# jr-support_v4.net
KiCad netlist of a schematic drawn in EAGLE
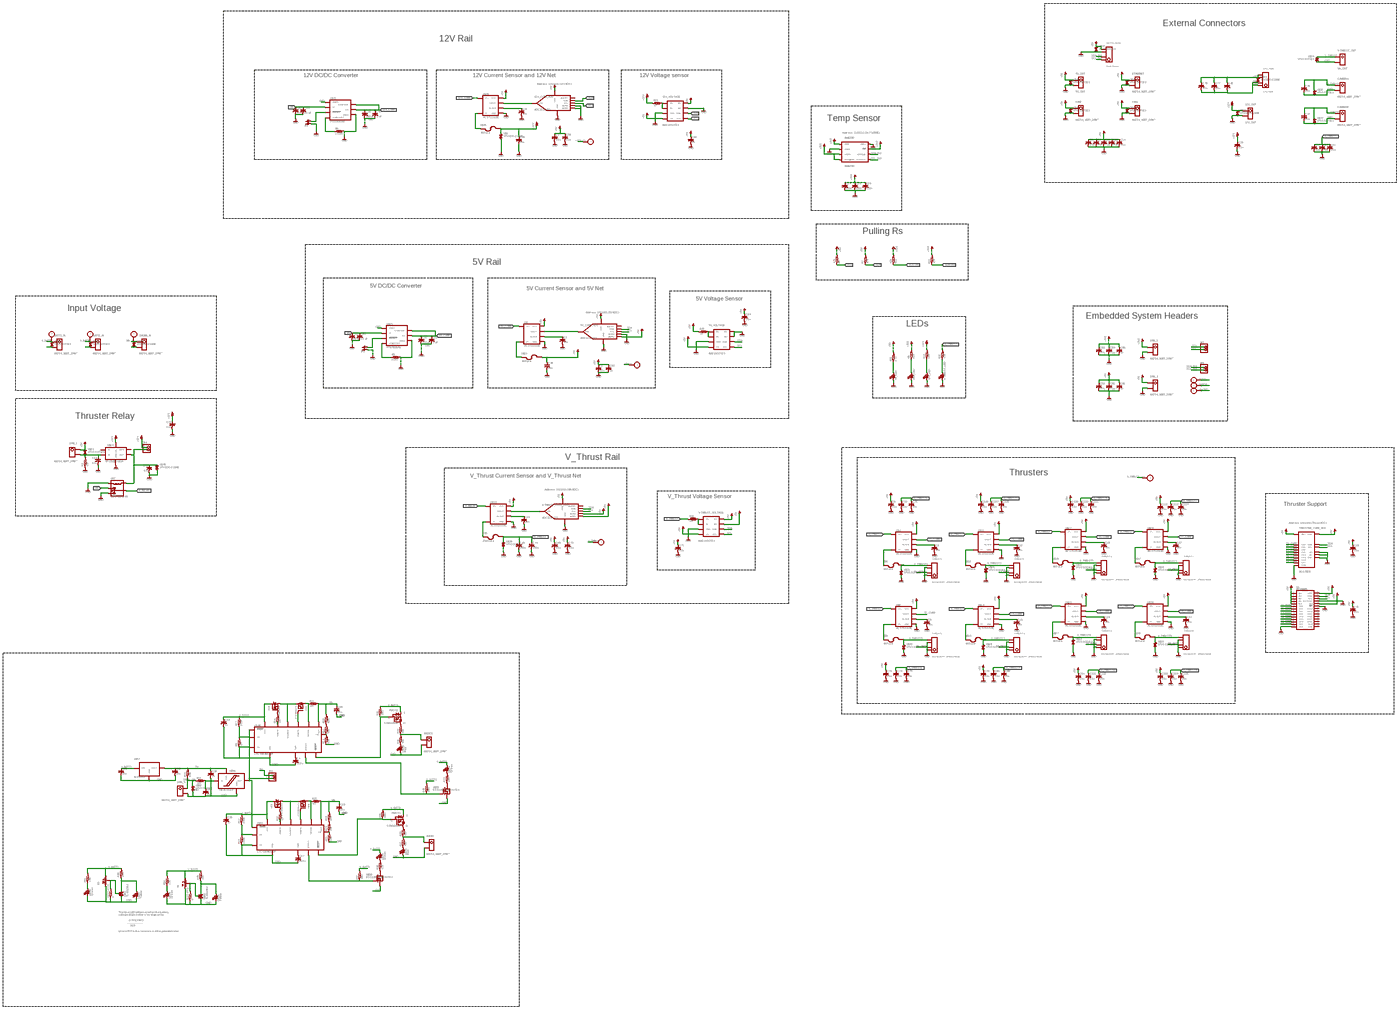
[diagram p0: schematic, sheet 1, overview]
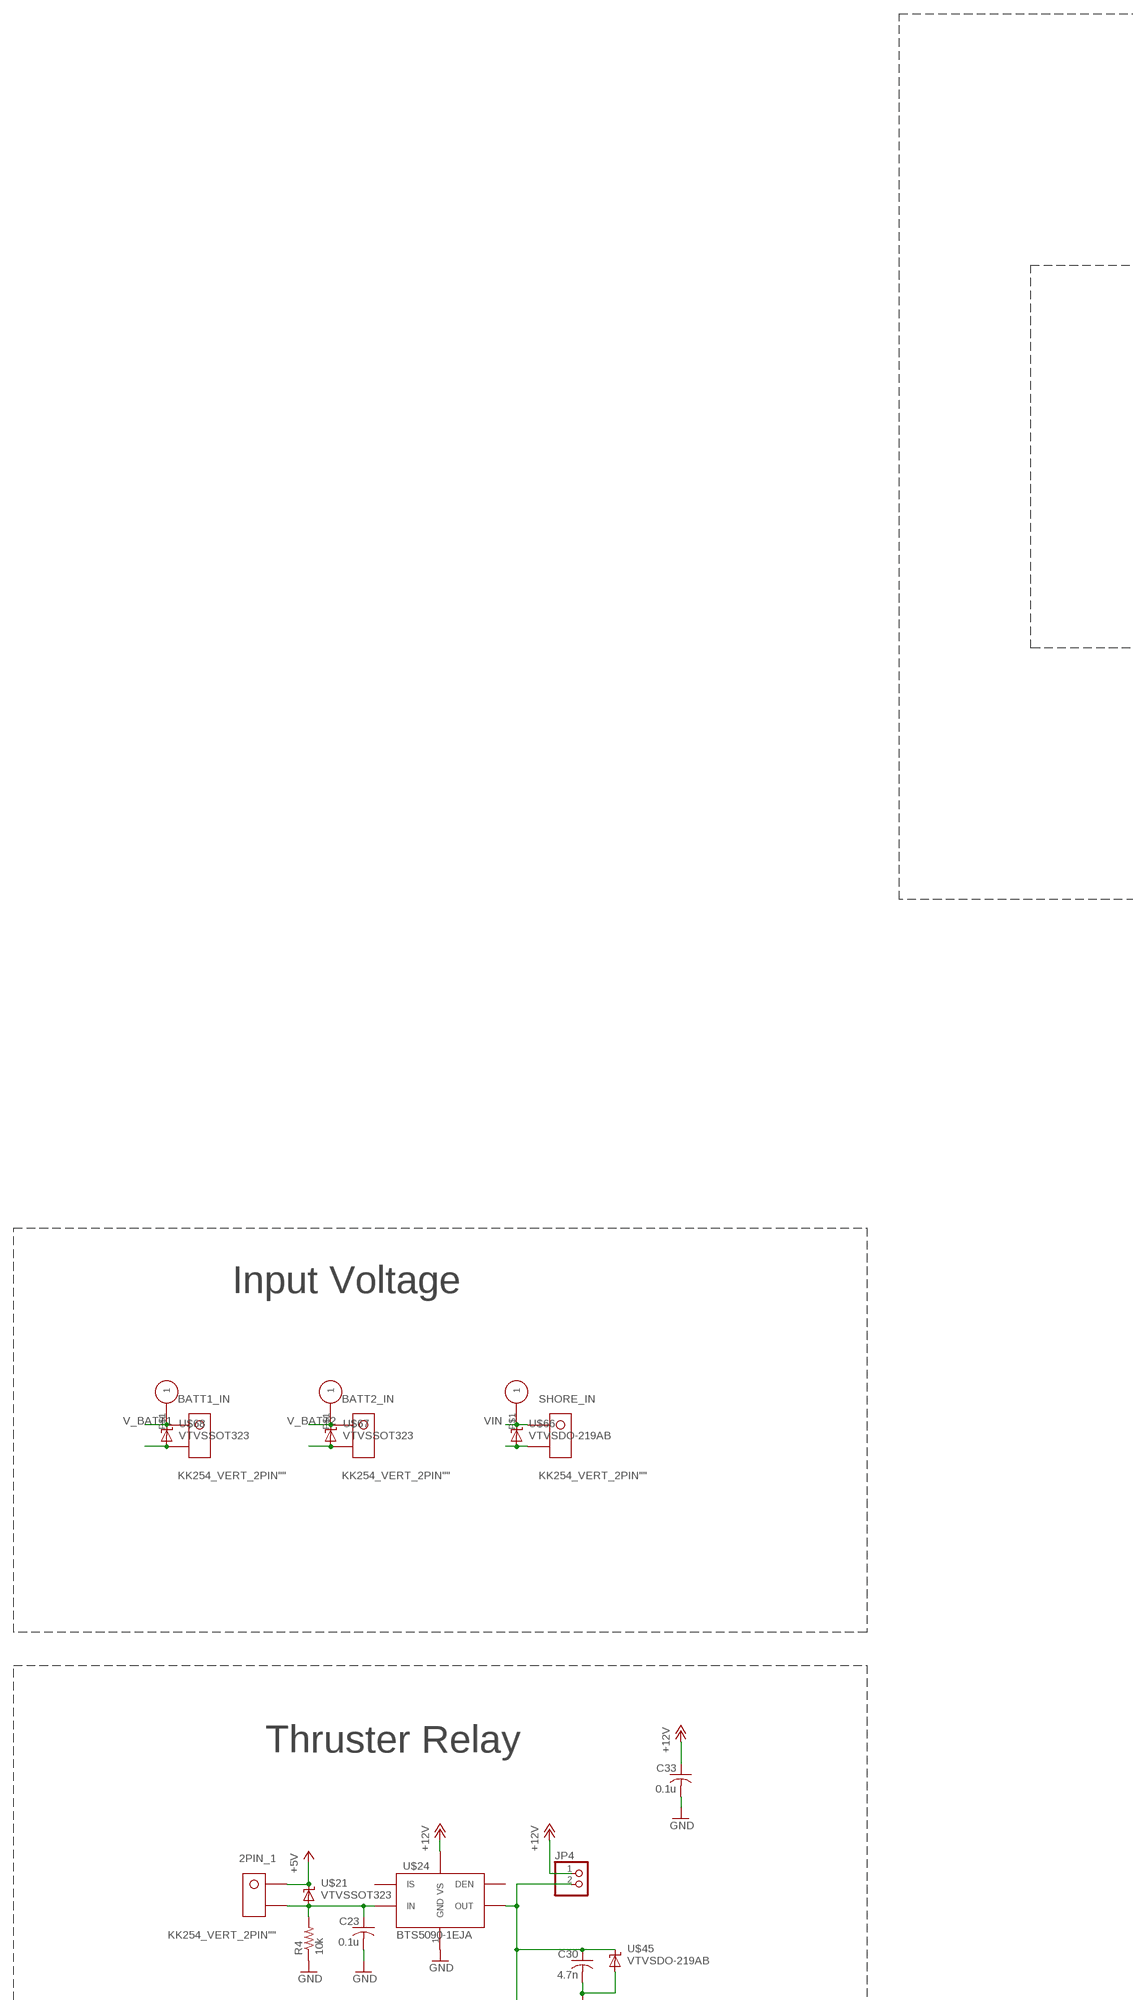
[diagram p1: schematic, sheet 1, part 1 of 8]
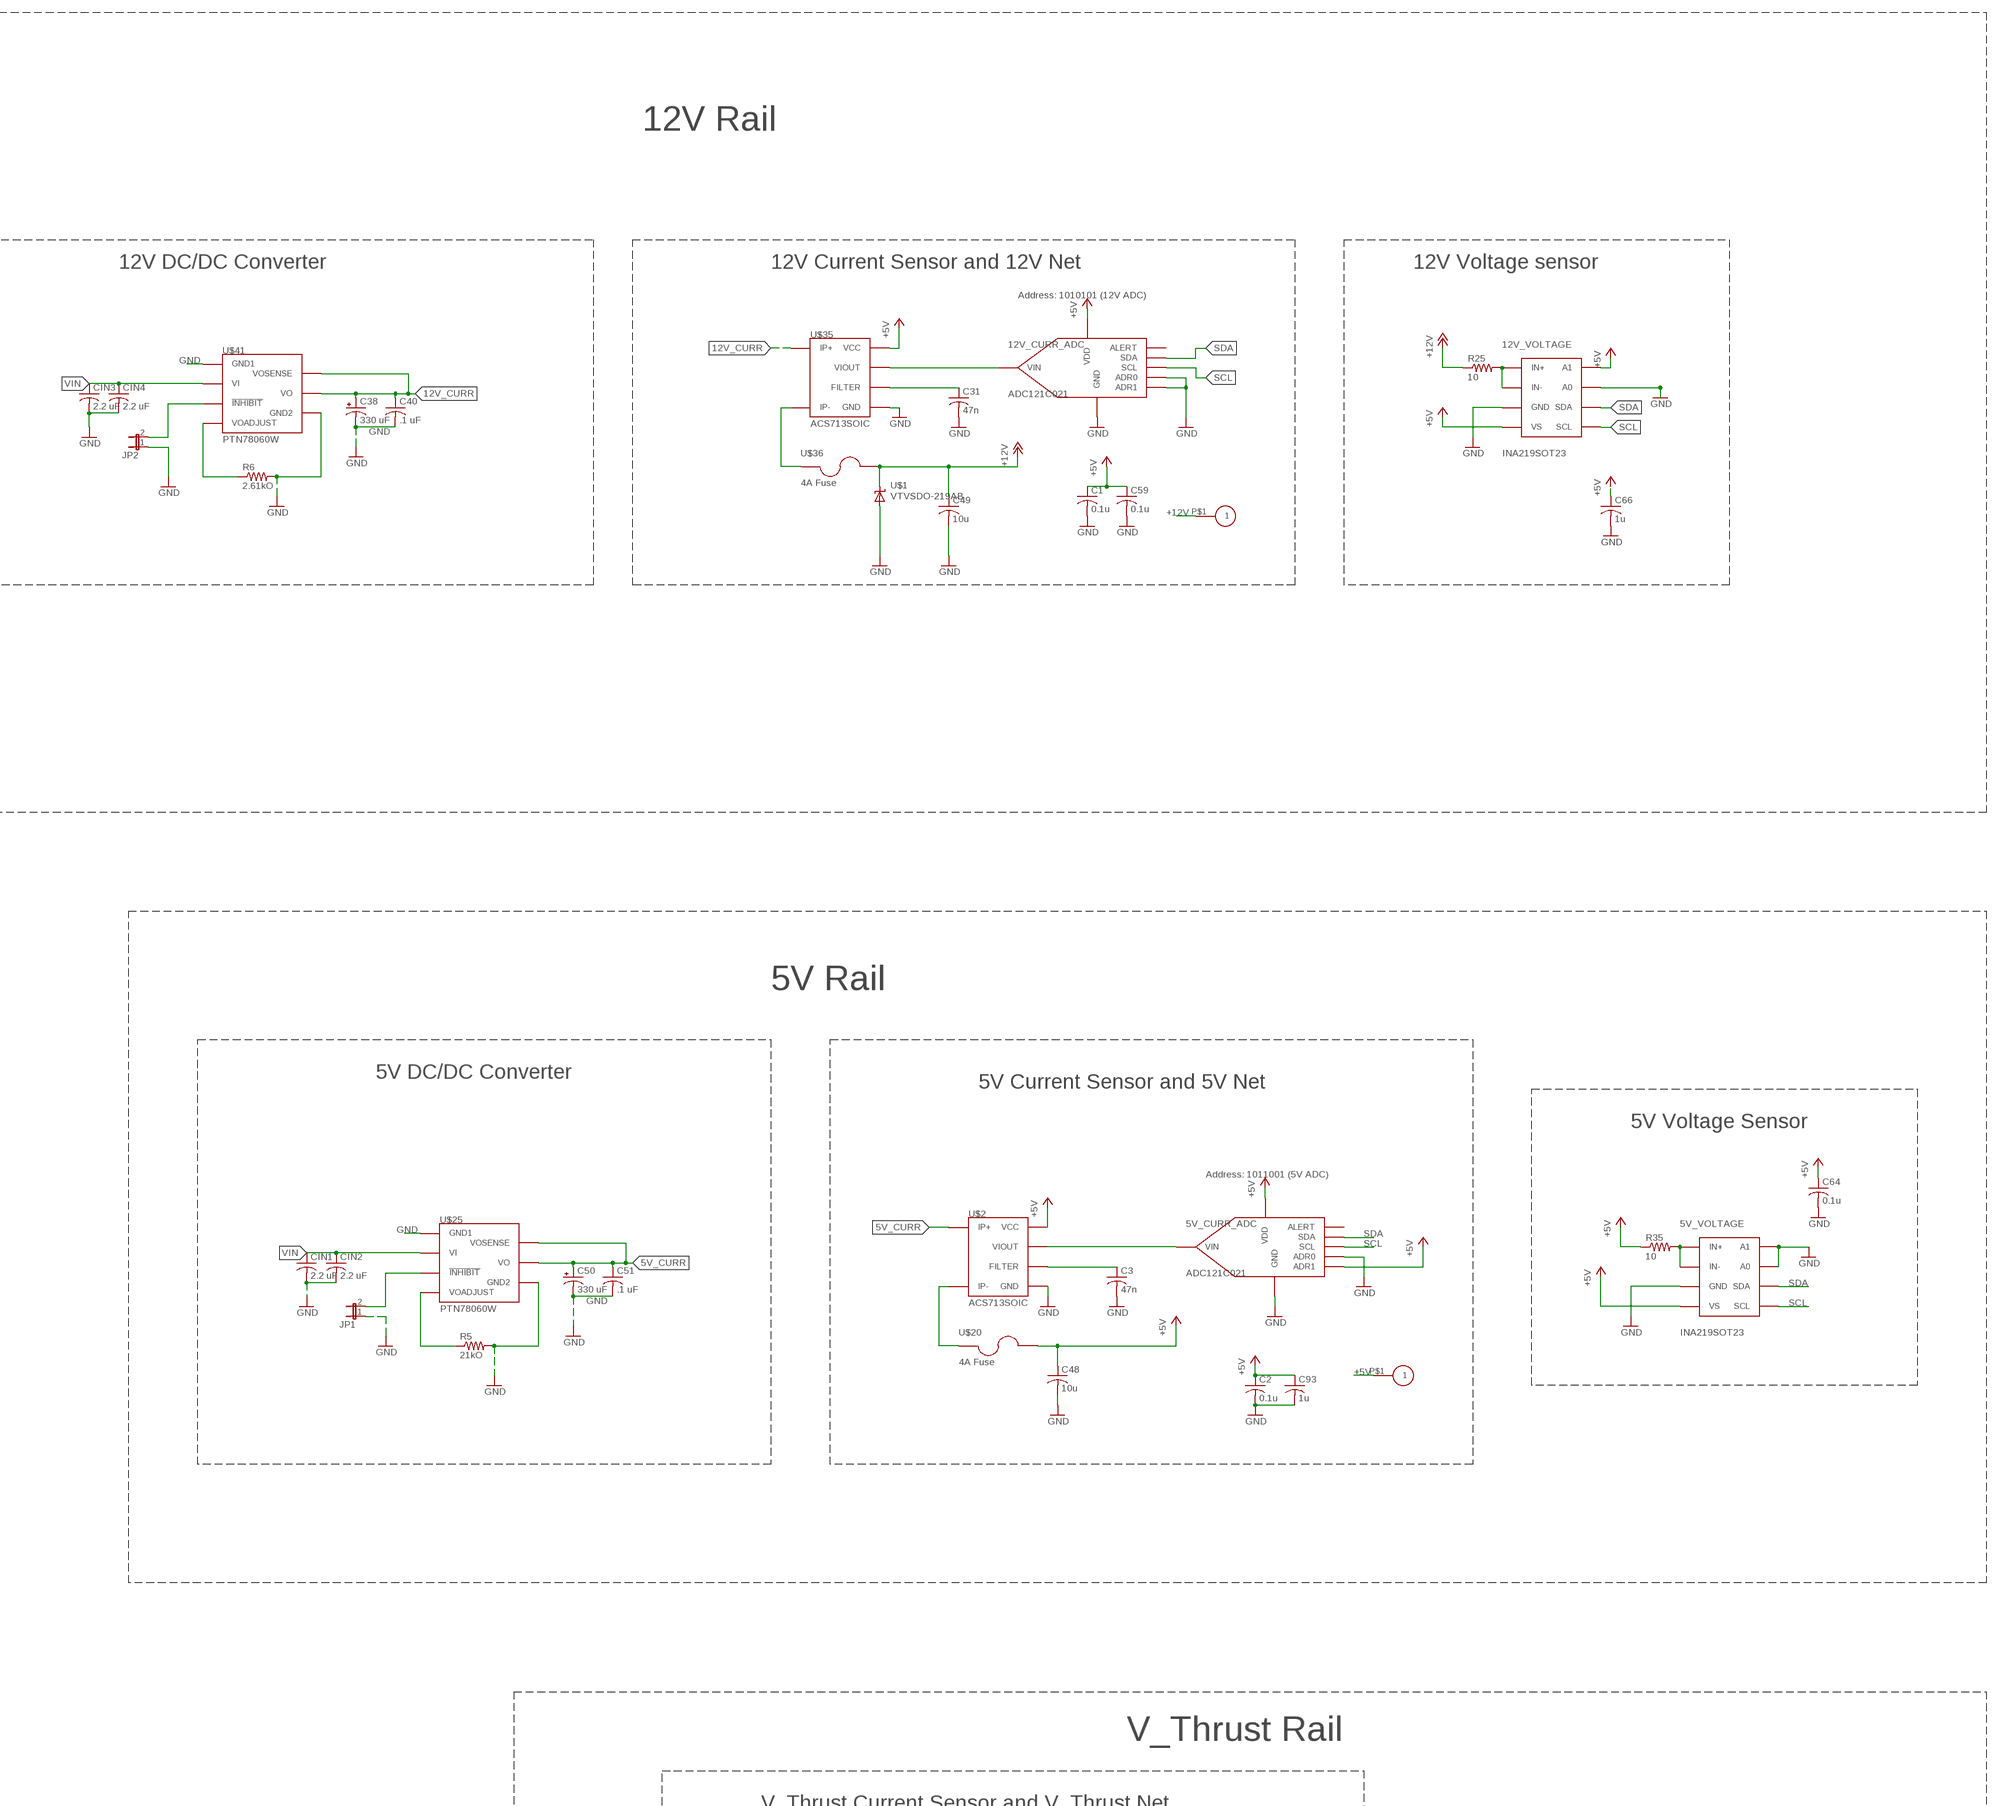
[diagram p2: schematic, sheet 1, part 2 of 8]
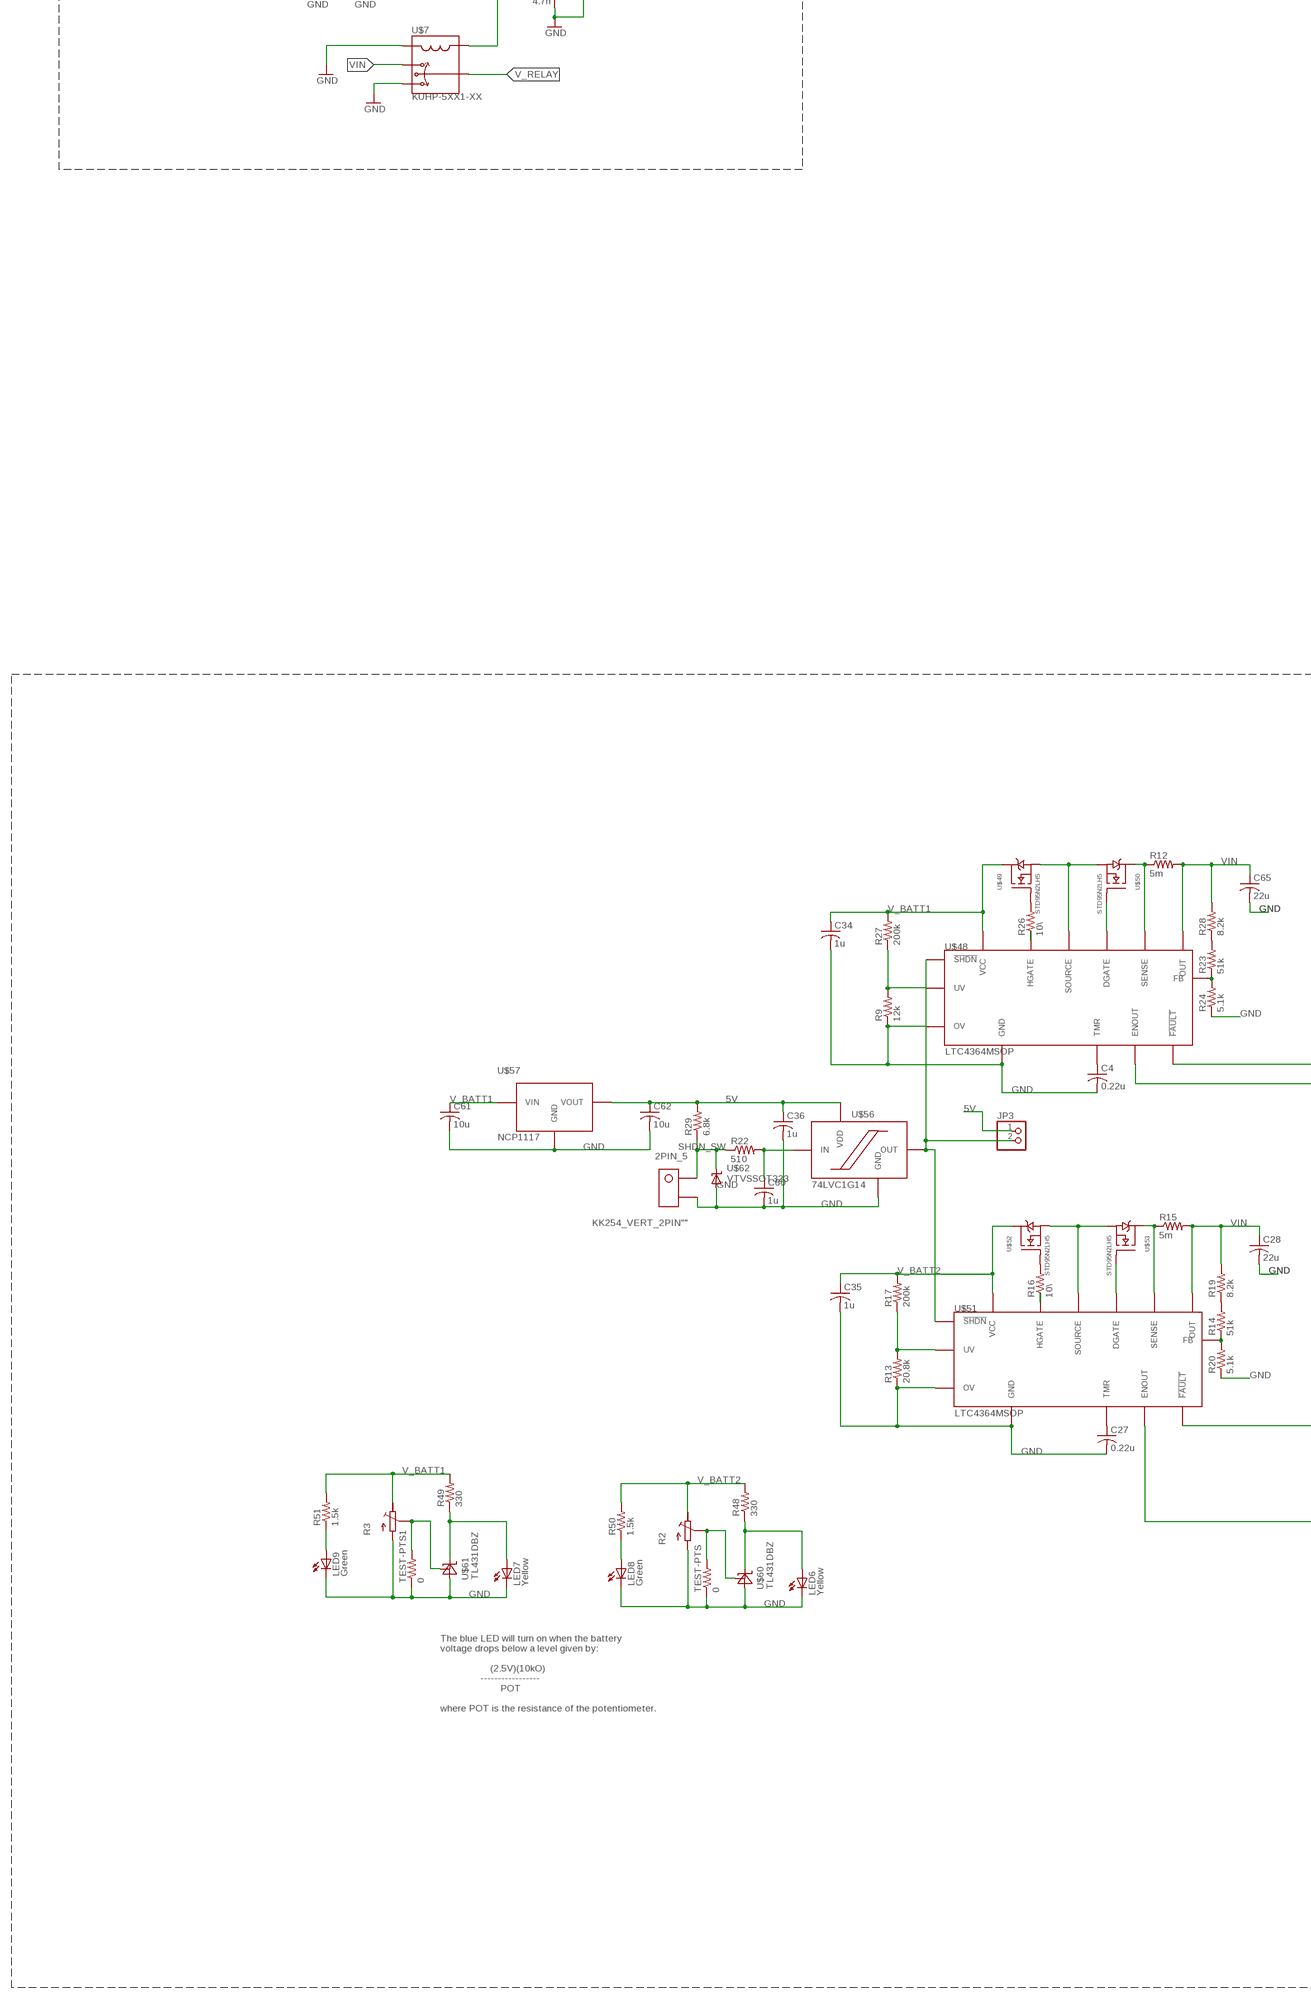
[diagram p3: schematic, sheet 1, part 3 of 8]
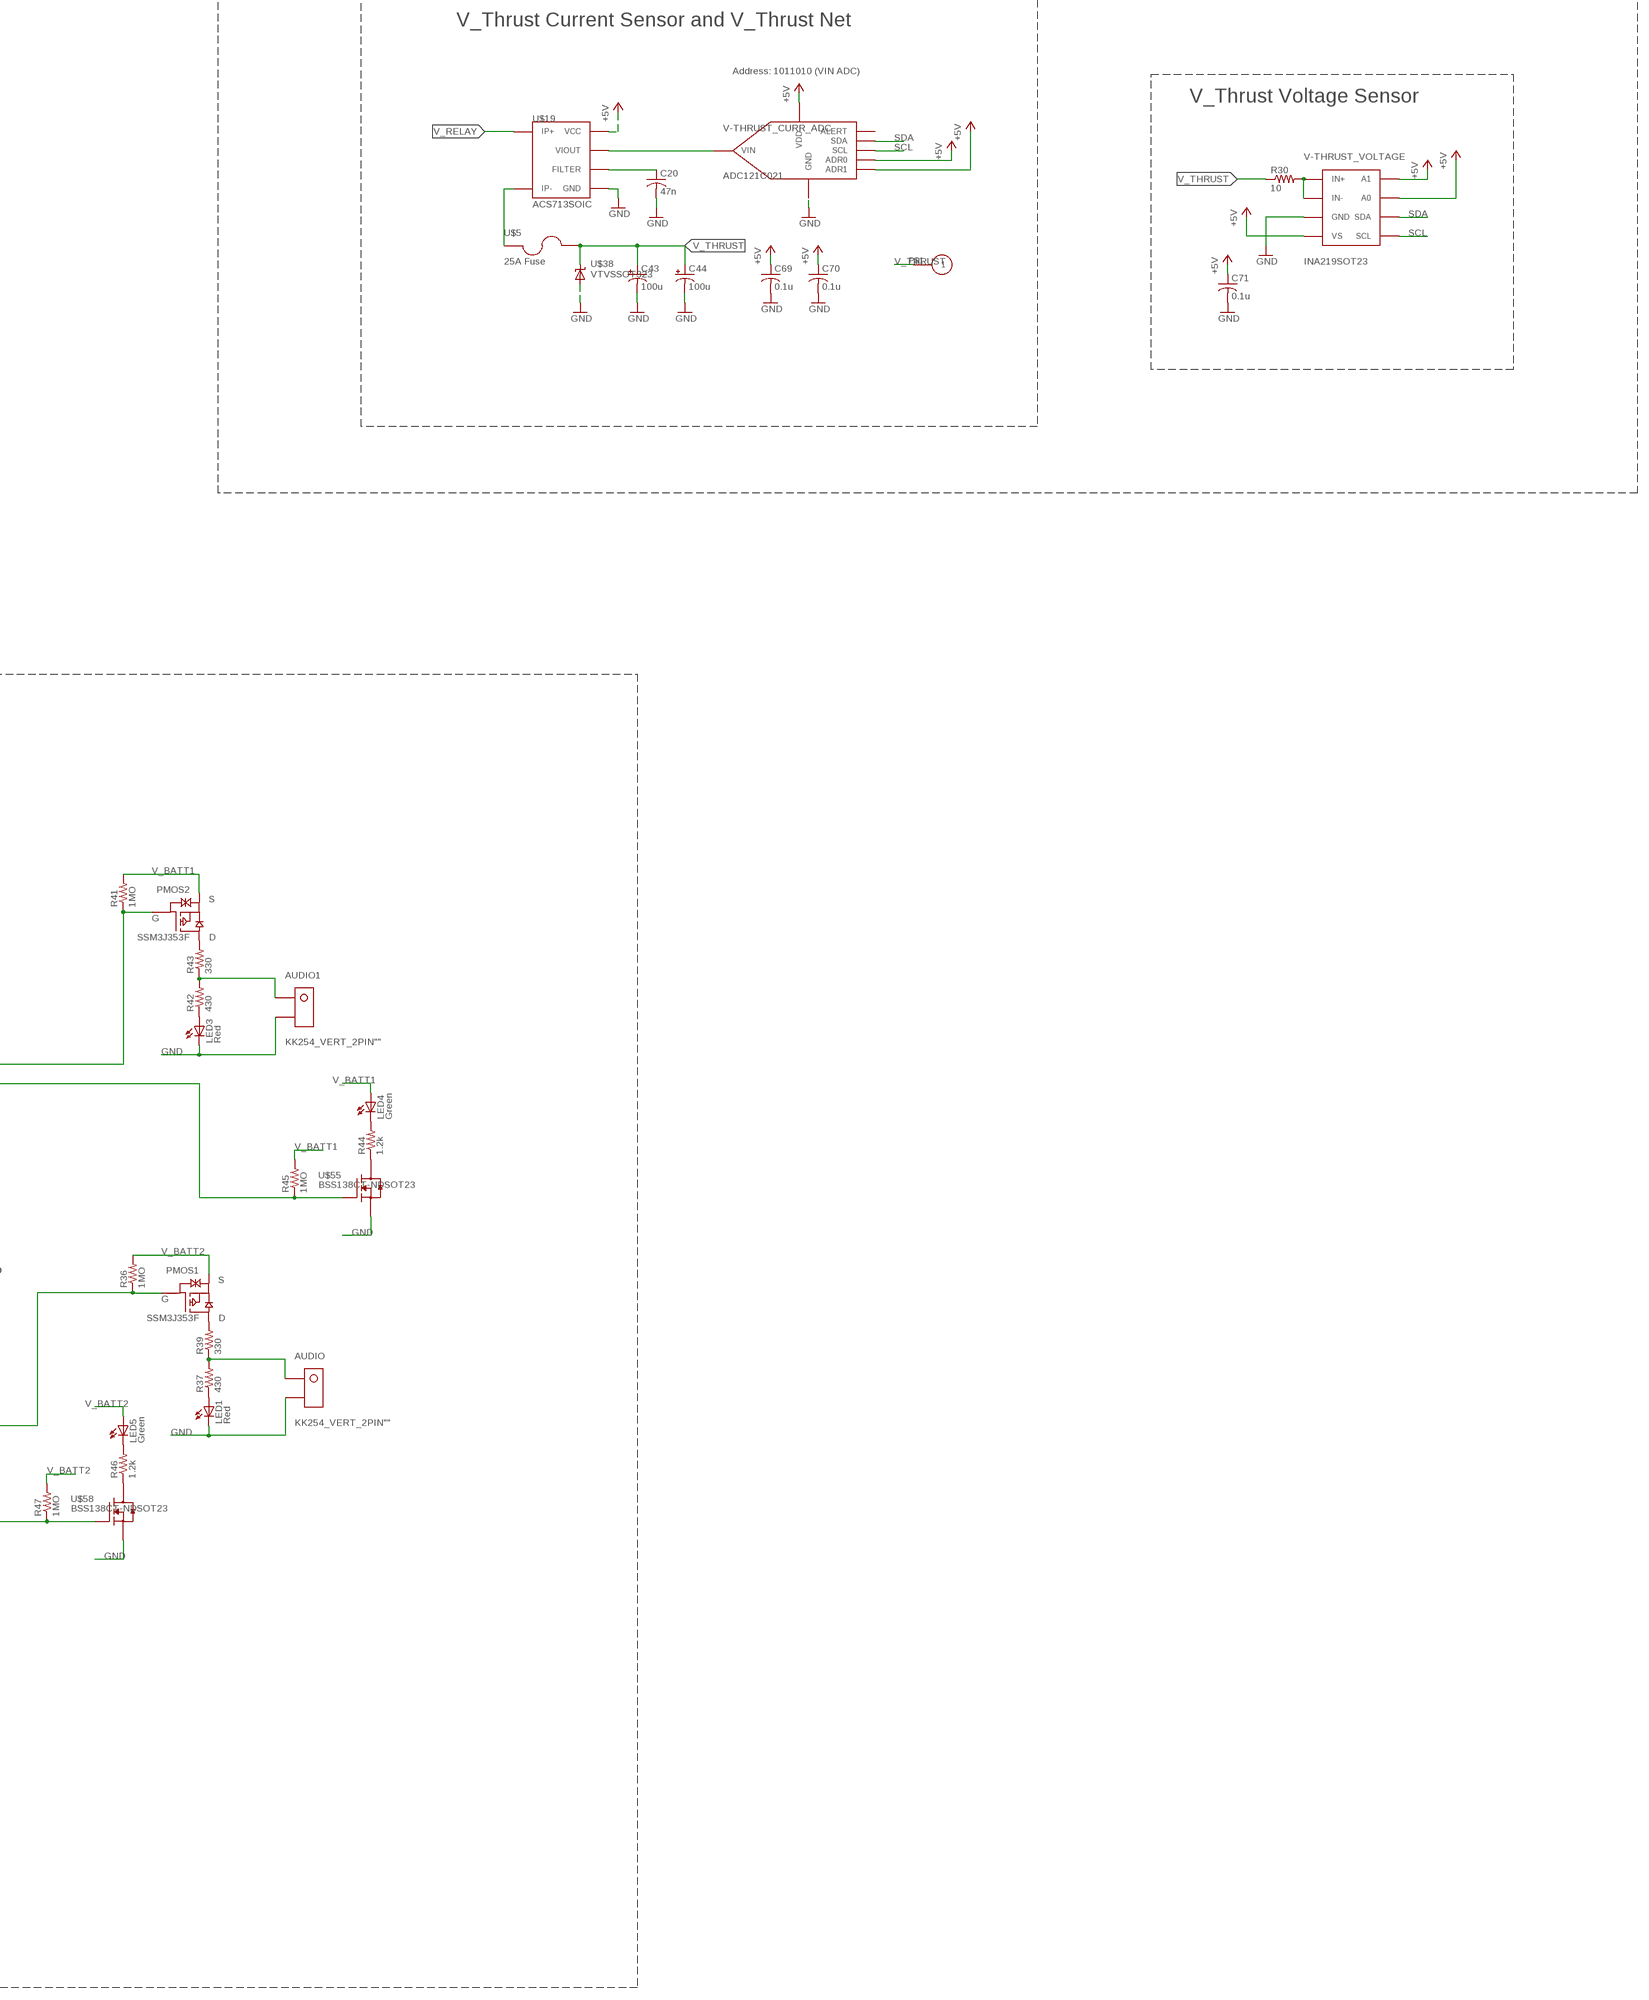
[diagram p4: schematic, sheet 1, part 4 of 8]
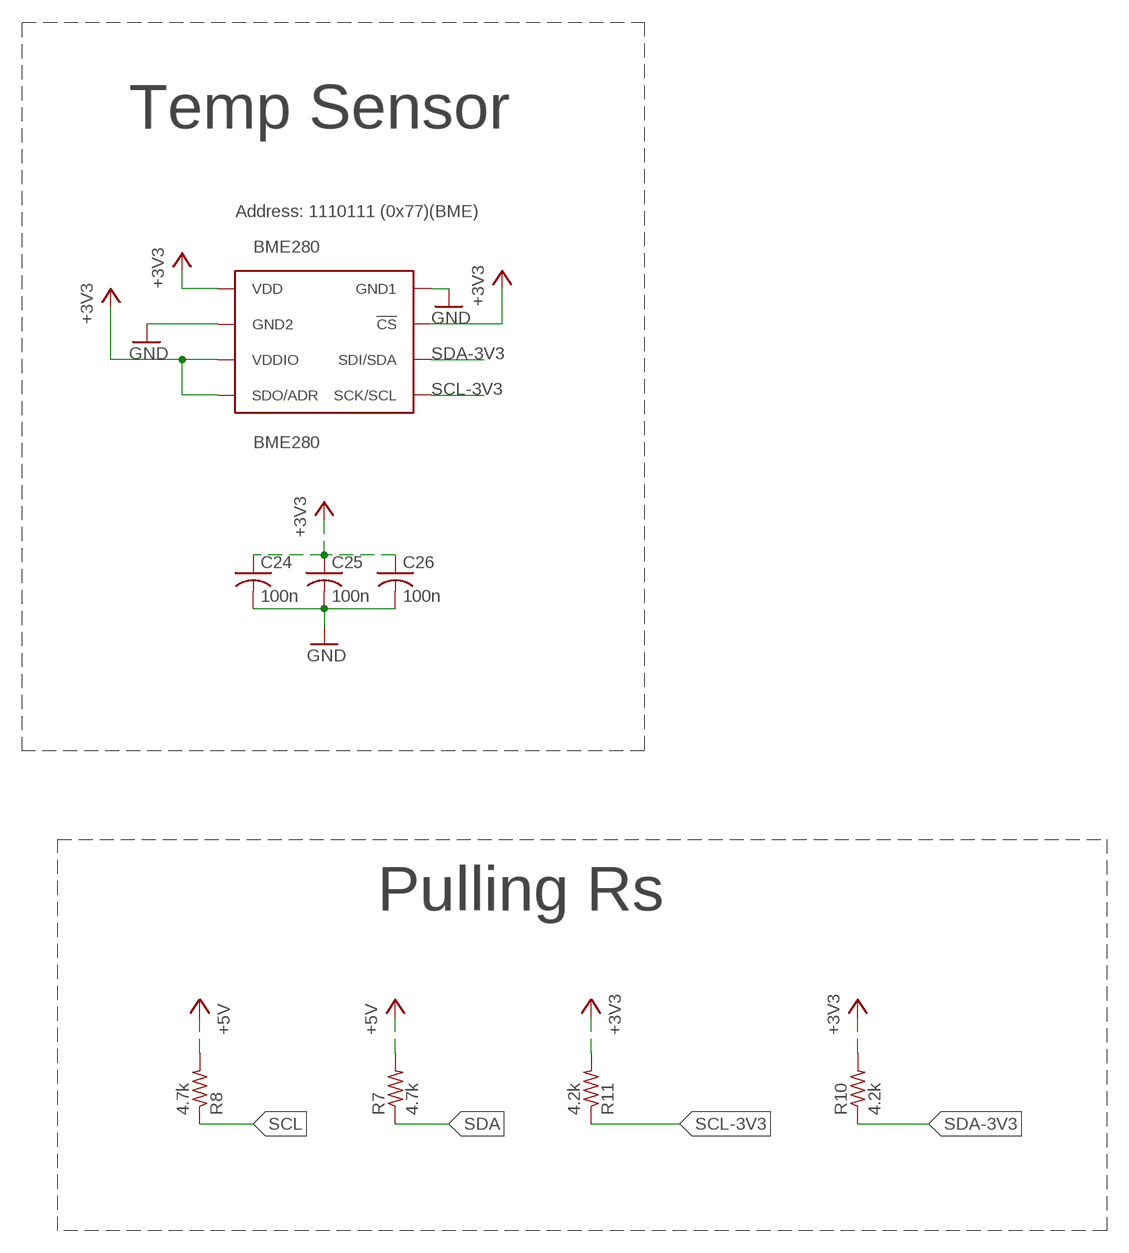
[diagram p5: schematic, sheet 1, part 5 of 8]
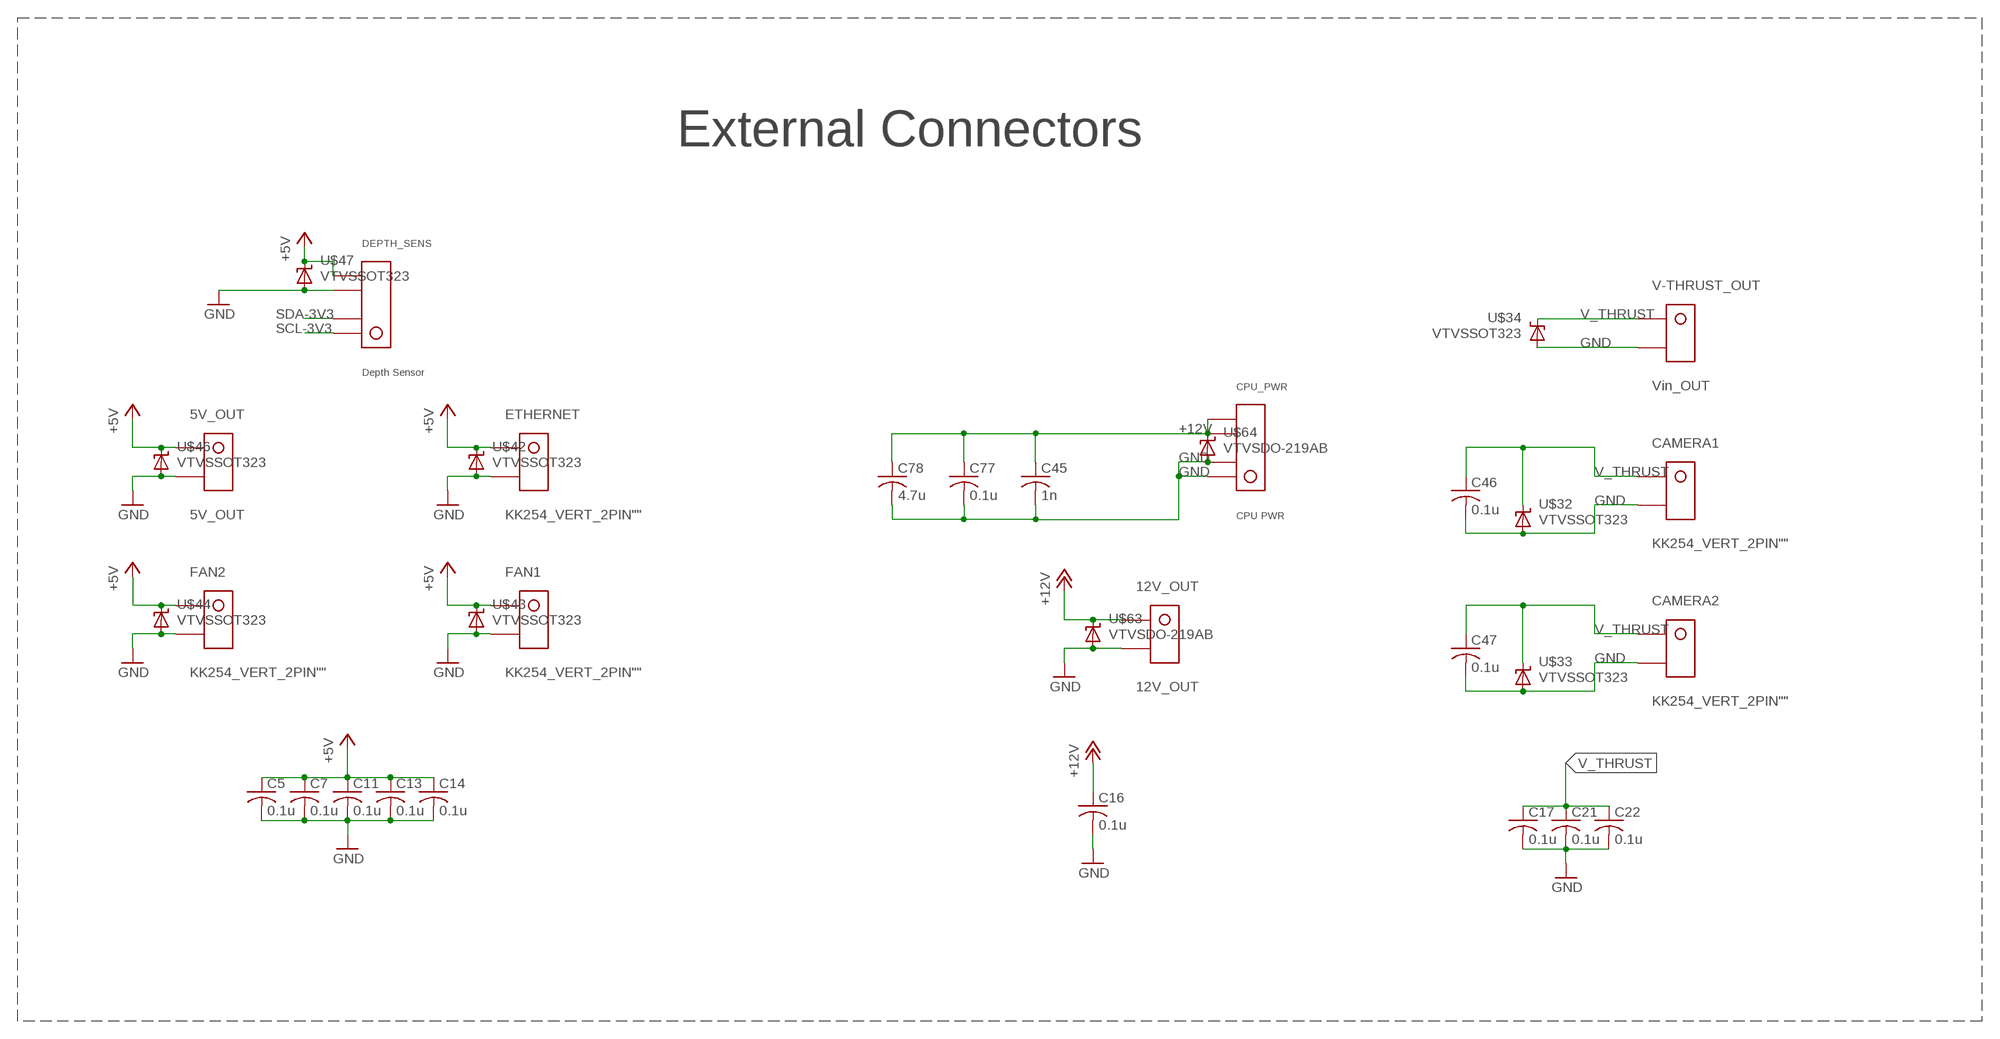
[diagram p6: schematic, sheet 1, part 6 of 8]
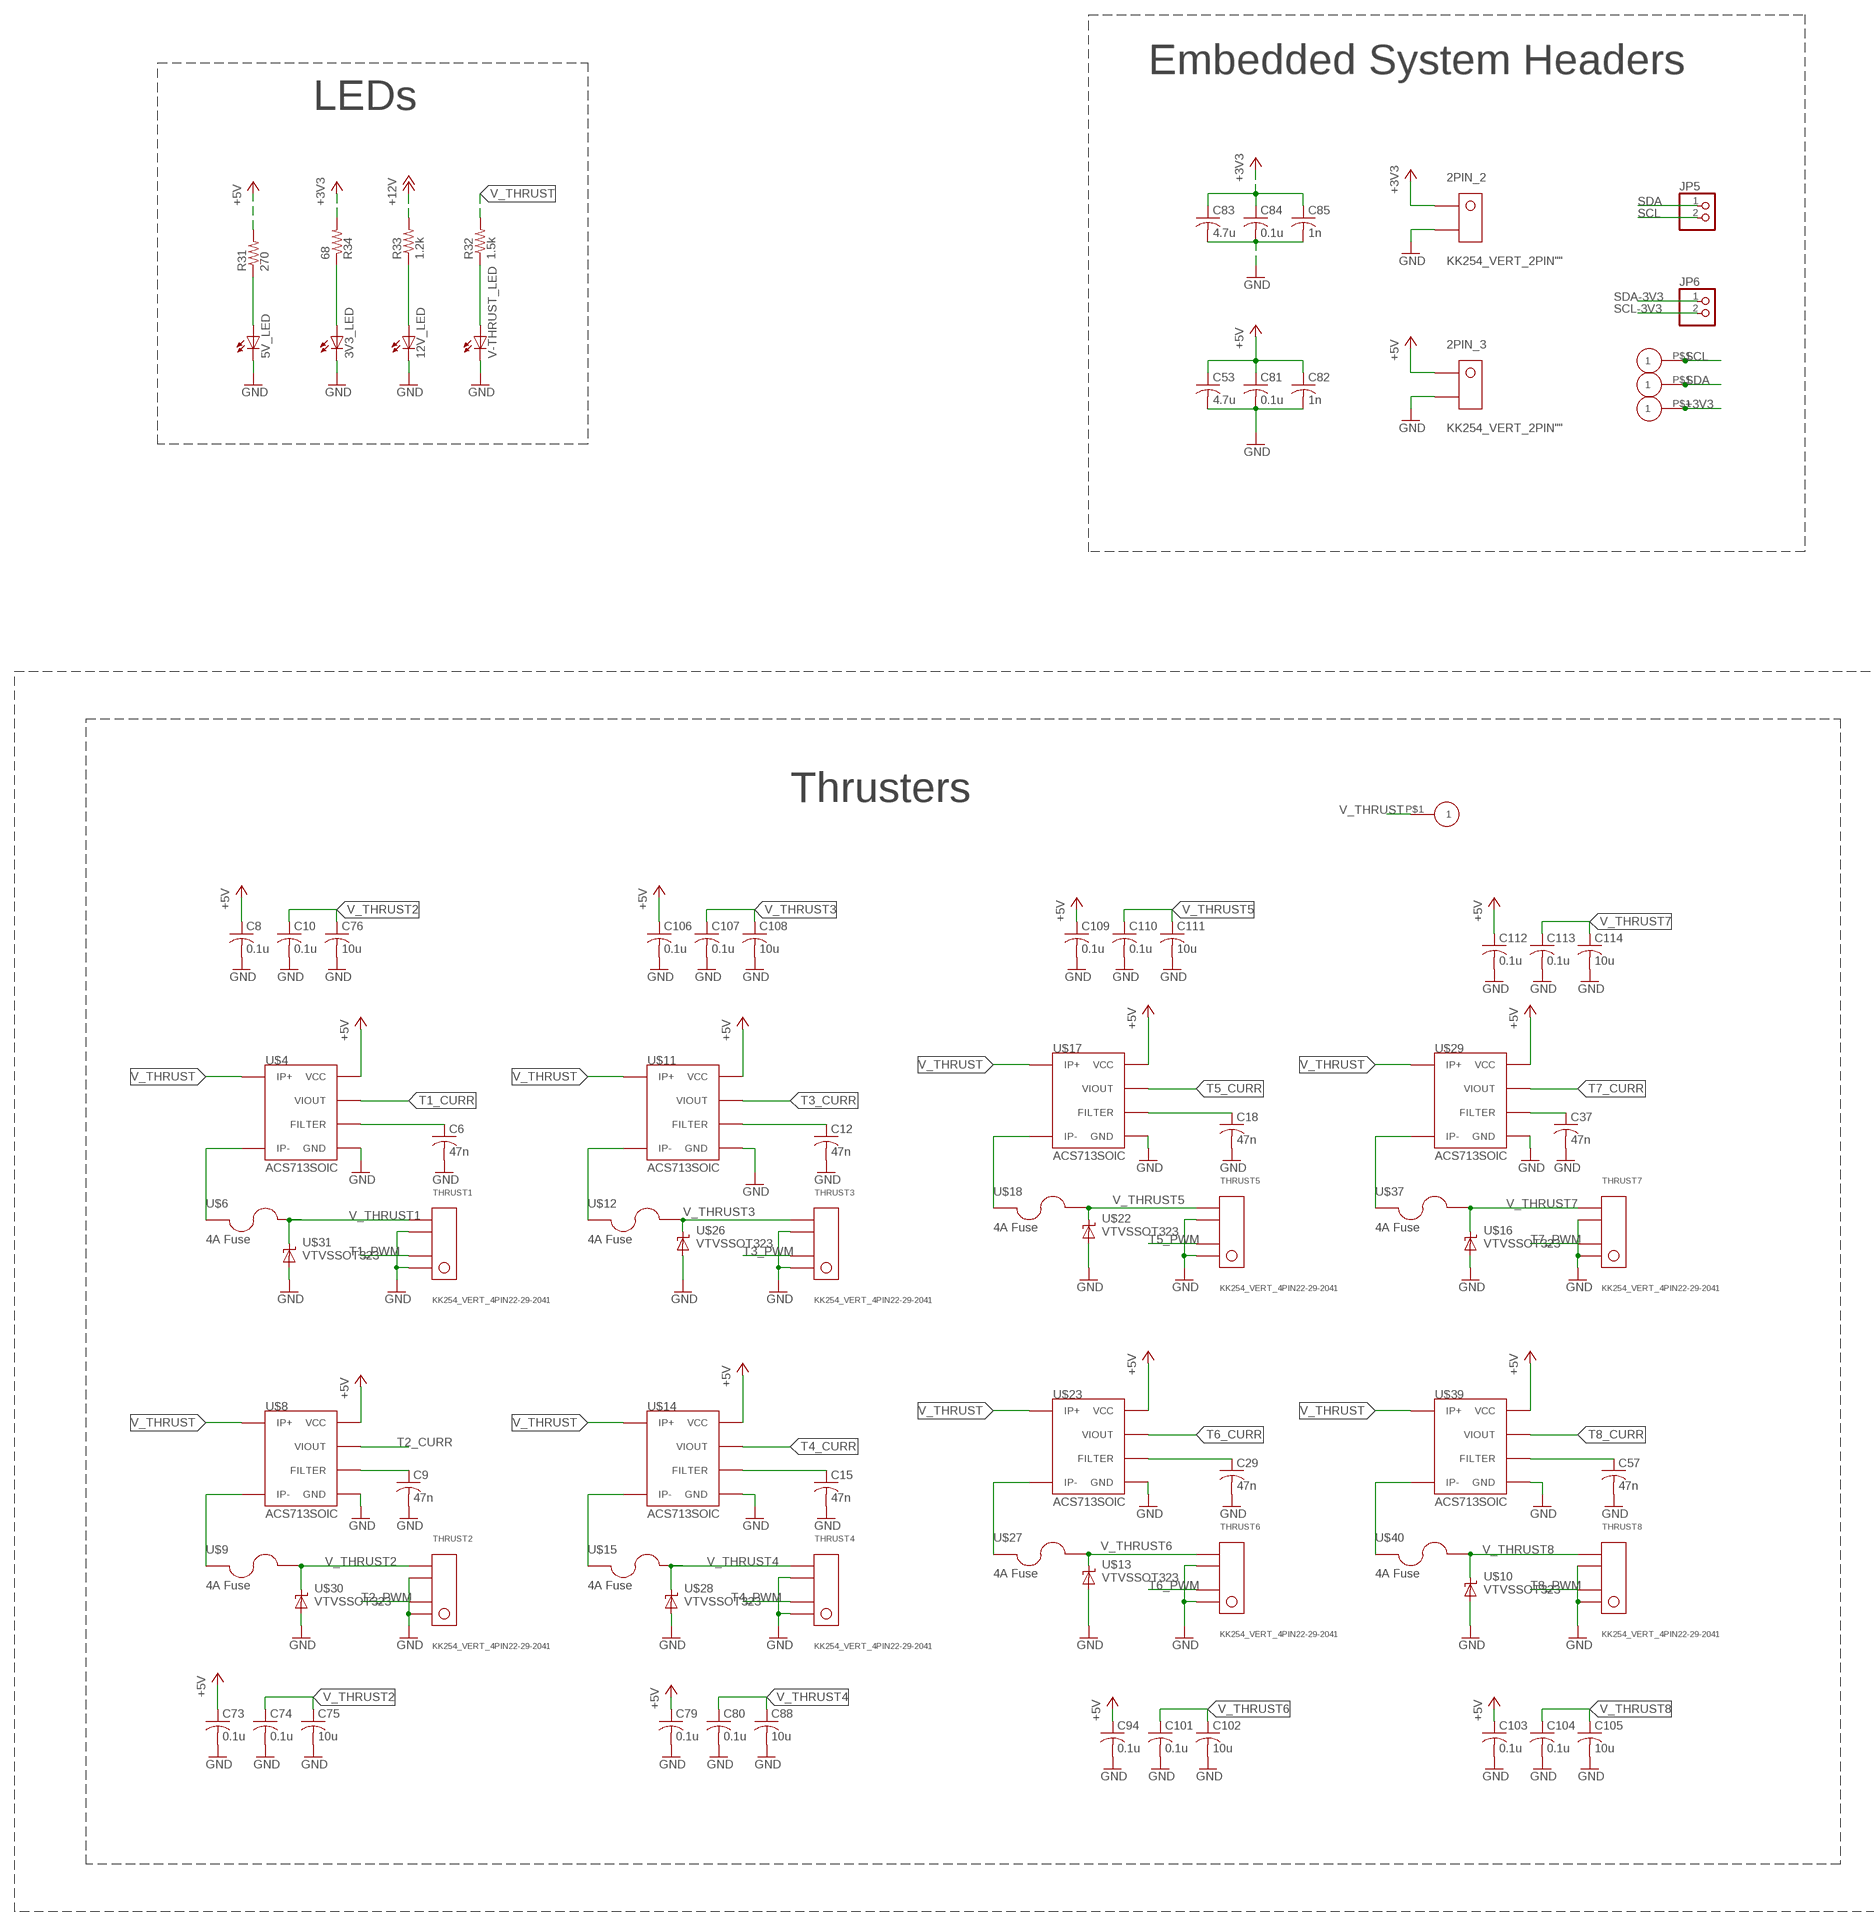
[diagram p7: schematic, sheet 1, part 7 of 8]
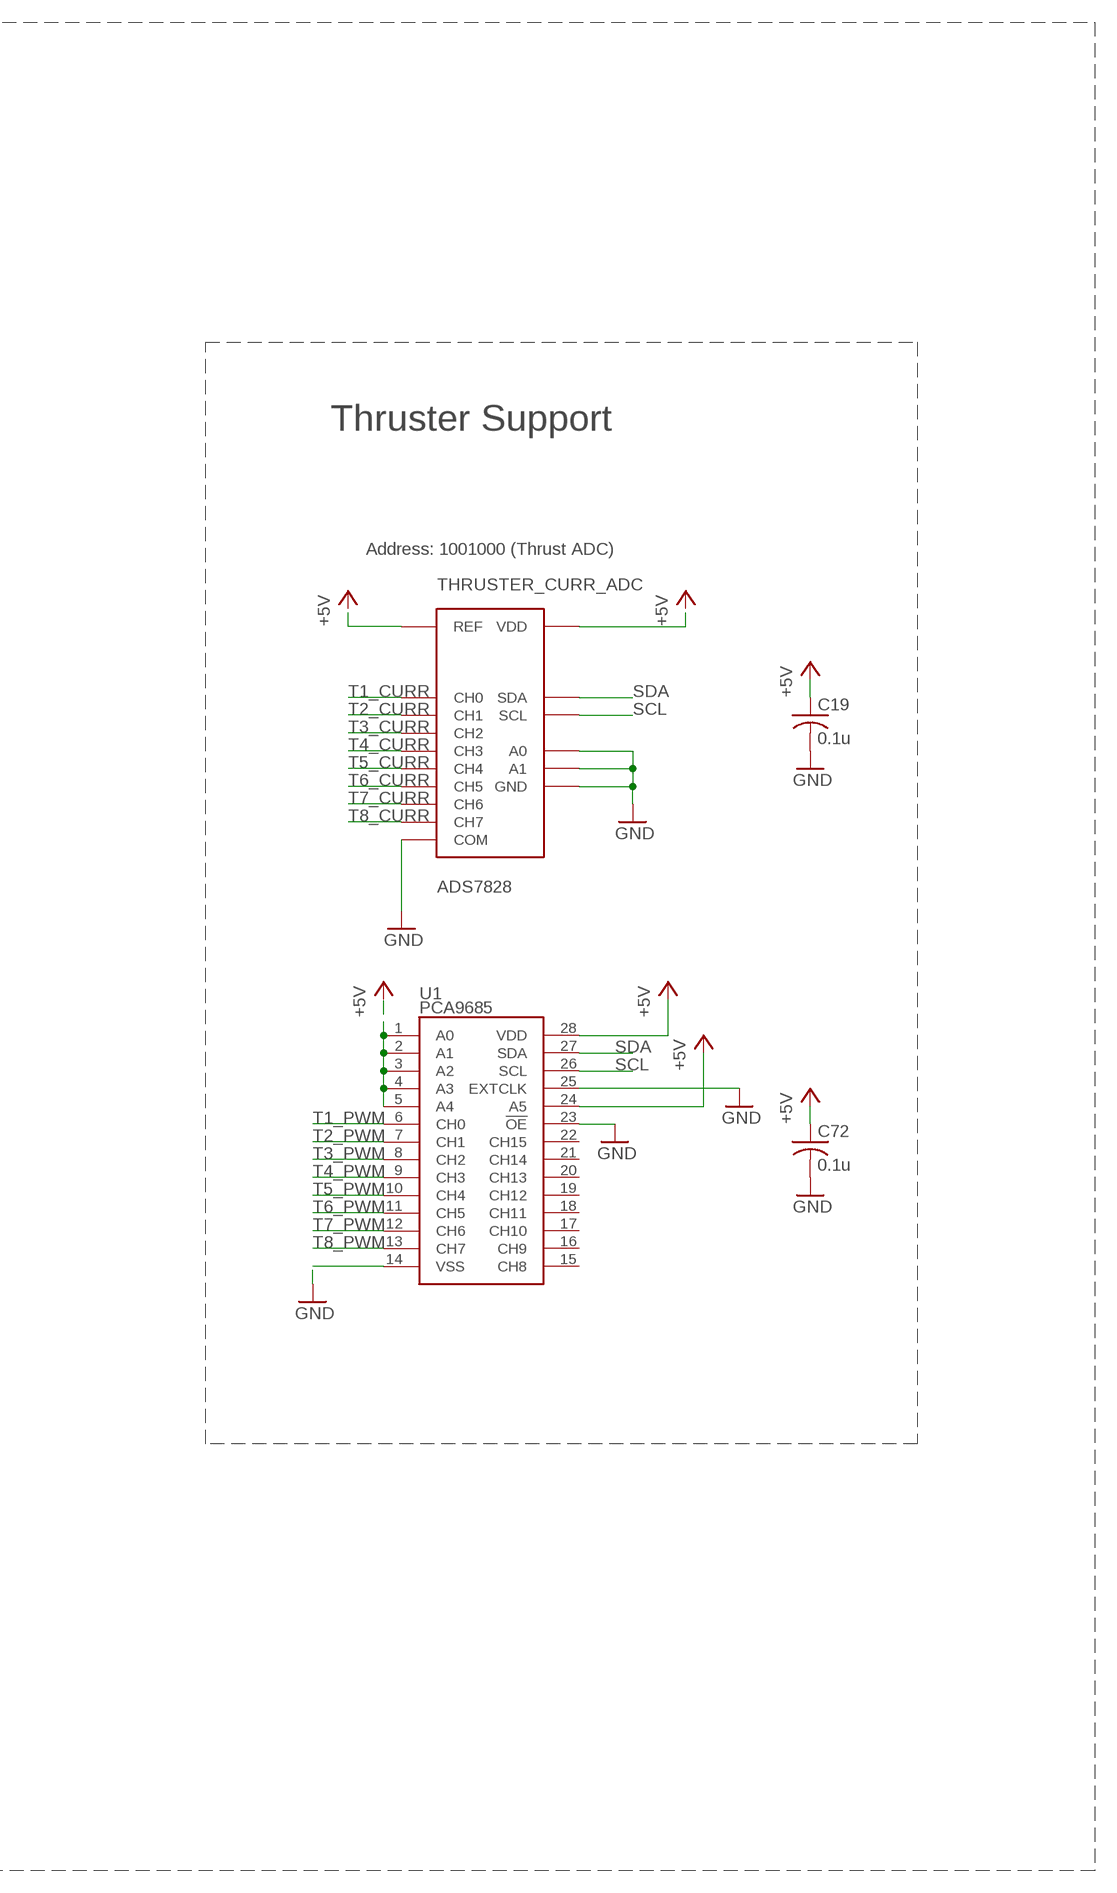
[diagram p8: schematic, sheet 1, part 8 of 8]

(export (version "E")
  (design (tool "Eeschema 10.0.6"))
  (components
    (comp (ref "2PIN_1")
      (value "KK254_VERT_2PIN\"\"")
      (footprint "eagle-import:KK254_VERT_2PIN")
      (libsource (lib "eagle-import") (part "KK254_VERT_2PIN{dblquote}{dblquote}"))
    )
    (comp (ref "2PIN_2")
      (value "KK254_VERT_2PIN\"\"")
      (footprint "eagle-import:KK254_VERT_2PIN")
      (libsource (lib "eagle-import") (part "KK254_VERT_2PIN{dblquote}{dblquote}"))
    )
    (comp (ref "2PIN_3")
      (value "KK254_VERT_2PIN\"\"")
      (footprint "eagle-import:KK254_VERT_2PIN")
      (libsource (lib "eagle-import") (part "KK254_VERT_2PIN{dblquote}{dblquote}"))
    )
    (comp (ref "2PIN_5")
      (value "KK254_VERT_2PIN\"\"")
      (footprint "eagle-import:KK254_VERT_2PIN")
      (libsource (lib "eagle-import") (part "KK254_VERT_2PIN{dblquote}{dblquote}"))
    )
    (comp (ref "3V3_LED")
      (value "0805_LED")
      (footprint "eagle-import:0805")
      (libsource (lib "eagle-import") (part "0805_LED"))
    )
    (comp (ref "5V_CURR_ADC")
      (value "ADC121C021")
      (footprint "eagle-import:VSSOP-8")
      (libsource (lib "eagle-import") (part "ADC121C021"))
    )
    (comp (ref "5V_LED")
      (value "0805_LED")
      (footprint "eagle-import:0805")
      (libsource (lib "eagle-import") (part "0805_LED"))
    )
    (comp (ref "5V_OUT")
      (value "5V_OUT")
      (footprint "eagle-import:KK254_VERT_2PIN")
      (libsource (lib "eagle-import") (part "KK254_VERT_2PIN{dblquote}{dblquote}"))
    )
    (comp (ref "5V_VOLTAGE")
      (value "INA219SOT23")
      (footprint "eagle-import:SOT-23-8")
      (libsource (lib "eagle-import") (part "INA219SOT23"))
    )
    (comp (ref "12V_CURR_ADC")
      (value "ADC121C021")
      (footprint "eagle-import:VSSOP-8")
      (libsource (lib "eagle-import") (part "ADC121C021"))
    )
    (comp (ref "12V_LED")
      (value "0805_LED")
      (footprint "eagle-import:0805")
      (libsource (lib "eagle-import") (part "0805_LED"))
    )
    (comp (ref "12V_OUT")
      (value "12V_OUT")
      (footprint "eagle-import:KK254_VERT_2PIN")
      (libsource (lib "eagle-import") (part "KK254_VERT_2PIN{dblquote}{dblquote}"))
    )
    (comp (ref "12V_VOLTAGE")
      (value "INA219SOT23")
      (footprint "eagle-import:SOT-23-8")
      (libsource (lib "eagle-import") (part "INA219SOT23"))
    )
    (comp (ref "AUDIO")
      (value "KK254_VERT_2PIN\"\"")
      (footprint "eagle-import:KK254_VERT_2PIN")
      (libsource (lib "eagle-import") (part "KK254_VERT_2PIN{dblquote}{dblquote}"))
    )
    (comp (ref "AUDIO1")
      (value "KK254_VERT_2PIN\"\"")
      (footprint "eagle-import:KK254_VERT_2PIN")
      (libsource (lib "eagle-import") (part "KK254_VERT_2PIN{dblquote}{dblquote}"))
    )
    (comp (ref "BATT1_IN")
      (value "KK254_VERT_2PIN\"\"")
      (footprint "eagle-import:KK254_VERT_2PIN")
      (libsource (lib "eagle-import") (part "KK254_VERT_2PIN{dblquote}{dblquote}"))
    )
    (comp (ref "BATT2_IN")
      (value "KK254_VERT_2PIN\"\"")
      (footprint "eagle-import:KK254_VERT_2PIN")
      (libsource (lib "eagle-import") (part "KK254_VERT_2PIN{dblquote}{dblquote}"))
    )
    (comp (ref "BME280")
      (value "BME280")
      (footprint "eagle-import:BME280_LGA")
      (libsource (lib "eagle-import") (part "BME280"))
    )
    (comp (ref "C1")
      (value "0.1u")
      (footprint "eagle-import:C0805")
      (libsource (lib "eagle-import") (part "C-USC0805"))
    )
    (comp (ref "C2")
      (value "0.1u")
      (footprint "eagle-import:C0805")
      (libsource (lib "eagle-import") (part "C-USC0805"))
    )
    (comp (ref "C3")
      (value "47n")
      (footprint "eagle-import:C0805")
      (libsource (lib "eagle-import") (part "C-USC0805"))
    )
    (comp (ref "C4")
      (value "0.22u")
      (footprint "eagle-import:C0805")
      (libsource (lib "eagle-import") (part "C-USC0805"))
    )
    (comp (ref "C5")
      (value "0.1u")
      (footprint "eagle-import:C0805")
      (libsource (lib "eagle-import") (part "C-USC0805"))
    )
    (comp (ref "C6")
      (value "47n")
      (footprint "eagle-import:C0805")
      (libsource (lib "eagle-import") (part "C-USC0805"))
    )
    (comp (ref "C7")
      (value "0.1u")
      (footprint "eagle-import:C0805")
      (libsource (lib "eagle-import") (part "C-USC0805"))
    )
    (comp (ref "C8")
      (value "0.1u")
      (footprint "eagle-import:C0805")
      (libsource (lib "eagle-import") (part "C-USC0805"))
    )
    (comp (ref "C9")
      (value "47n")
      (footprint "eagle-import:C0805")
      (libsource (lib "eagle-import") (part "C-USC0805"))
    )
    (comp (ref "C10")
      (value "0.1u")
      (footprint "eagle-import:C0805")
      (libsource (lib "eagle-import") (part "C-USC0805"))
    )
    (comp (ref "C11")
      (value "0.1u")
      (footprint "eagle-import:C0805")
      (libsource (lib "eagle-import") (part "C-USC0805"))
    )
    (comp (ref "C12")
      (value "47n")
      (footprint "eagle-import:C0805")
      (libsource (lib "eagle-import") (part "C-USC0805"))
    )
    (comp (ref "C13")
      (value "0.1u")
      (footprint "eagle-import:C0805")
      (libsource (lib "eagle-import") (part "C-USC0805"))
    )
    (comp (ref "C14")
      (value "0.1u")
      (footprint "eagle-import:C0805")
      (libsource (lib "eagle-import") (part "C-USC0805"))
    )
    (comp (ref "C15")
      (value "47n")
      (footprint "eagle-import:C0805")
      (libsource (lib "eagle-import") (part "C-USC0805"))
    )
    (comp (ref "C16")
      (value "0.1u")
      (footprint "eagle-import:C0805")
      (libsource (lib "eagle-import") (part "C-USC0805"))
    )
    (comp (ref "C17")
      (value "0.1u")
      (footprint "eagle-import:C0805")
      (libsource (lib "eagle-import") (part "C-USC0805"))
    )
    (comp (ref "C18")
      (value "47n")
      (footprint "eagle-import:C0805")
      (libsource (lib "eagle-import") (part "C-USC0805"))
    )
    (comp (ref "C19")
      (value "0.1u")
      (footprint "eagle-import:C0805")
      (libsource (lib "eagle-import") (part "C-USC0805"))
    )
    (comp (ref "C20")
      (value "47n")
      (footprint "eagle-import:C0805")
      (libsource (lib "eagle-import") (part "C-USC0805"))
    )
    (comp (ref "C21")
      (value "0.1u")
      (footprint "eagle-import:C0805")
      (libsource (lib "eagle-import") (part "C-USC0805"))
    )
    (comp (ref "C22")
      (value "0.1u")
      (footprint "eagle-import:C0805")
      (libsource (lib "eagle-import") (part "C-USC0805"))
    )
    (comp (ref "C23")
      (value "0.1u")
      (footprint "eagle-import:C0805")
      (libsource (lib "eagle-import") (part "C-USC0805"))
    )
    (comp (ref "C24")
      (value "100n")
      (footprint "eagle-import:C0805")
      (libsource (lib "eagle-import") (part "C-USC0805"))
    )
    (comp (ref "C25")
      (value "100n")
      (footprint "eagle-import:C0805")
      (libsource (lib "eagle-import") (part "C-USC0805"))
    )
    (comp (ref "C26")
      (value "100n")
      (footprint "eagle-import:C0805")
      (libsource (lib "eagle-import") (part "C-USC0805"))
    )
    (comp (ref "C27")
      (value "0.22u")
      (footprint "eagle-import:C0805")
      (libsource (lib "eagle-import") (part "C-USC0805"))
    )
    (comp (ref "C28")
      (value "22u")
      (footprint "eagle-import:C0805")
      (libsource (lib "eagle-import") (part "C-USC0805"))
    )
    (comp (ref "C29")
      (value "47n")
      (footprint "eagle-import:C0805")
      (libsource (lib "eagle-import") (part "C-USC0805"))
    )
    (comp (ref "C30")
      (value "4.7n")
      (footprint "eagle-import:C0805")
      (libsource (lib "eagle-import") (part "C-USC0805"))
    )
    (comp (ref "C31")
      (value "47n")
      (footprint "eagle-import:C0805")
      (libsource (lib "eagle-import") (part "C-USC0805"))
    )
    (comp (ref "C33")
      (value "0.1u")
      (footprint "eagle-import:C0805")
      (libsource (lib "eagle-import") (part "C-USC0805"))
    )
    (comp (ref "C34")
      (value "1u")
      (footprint "eagle-import:C0805")
      (libsource (lib "eagle-import") (part "C-USC0805"))
    )
    (comp (ref "C35")
      (value "1u")
      (footprint "eagle-import:C0805")
      (libsource (lib "eagle-import") (part "C-USC0805"))
    )
    (comp (ref "C36")
      (value "1u")
      (footprint "eagle-import:C0805")
      (libsource (lib "eagle-import") (part "C-USC0805"))
    )
    (comp (ref "C37")
      (value "47n")
      (footprint "eagle-import:C0805")
      (libsource (lib "eagle-import") (part "C-USC0805"))
    )
    (comp (ref "C38")
      (value "330 uF")
      (footprint "eagle-import:CKR_D10")
      (libsource (lib "eagle-import") (part "CPOL-USCKR_D10"))
    )
    (comp (ref "C40")
      (value ".1 uF")
      (footprint "eagle-import:C0805")
      (libsource (lib "eagle-import") (part "C-USC0805"))
    )
    (comp (ref "C43")
      (value "100u")
      (footprint "eagle-import:140CLH-0810")
      (libsource (lib "eagle-import") (part "CPOL-US140CLH-0810"))
    )
    (comp (ref "C44")
      (value "100u")
      (footprint "eagle-import:140CLH-0810")
      (libsource (lib "eagle-import") (part "CPOL-US140CLH-0810"))
    )
    (comp (ref "C45")
      (value "1n")
      (footprint "eagle-import:C0805")
      (libsource (lib "eagle-import") (part "C-USC0805"))
    )
    (comp (ref "C46")
      (value "0.1u")
      (footprint "eagle-import:C0805")
      (libsource (lib "eagle-import") (part "C-USC0805"))
    )
    (comp (ref "C47")
      (value "0.1u")
      (footprint "eagle-import:C0805")
      (libsource (lib "eagle-import") (part "C-USC0805"))
    )
    (comp (ref "C48")
      (value "10u")
      (footprint "eagle-import:C0805")
      (libsource (lib "eagle-import") (part "C-USC0805"))
    )
    (comp (ref "C49")
      (value "10u")
      (footprint "eagle-import:C0805")
      (libsource (lib "eagle-import") (part "C-USC0805"))
    )
    (comp (ref "C50")
      (value "330 uF")
      (footprint "eagle-import:CKR_D10")
      (libsource (lib "eagle-import") (part "CPOL-USCKR_D10"))
    )
    (comp (ref "C51")
      (value ".1 uF")
      (footprint "eagle-import:C0805")
      (libsource (lib "eagle-import") (part "C-USC0805"))
    )
    (comp (ref "C53")
      (value "4.7u")
      (footprint "eagle-import:C0805")
      (libsource (lib "eagle-import") (part "C-USC0805"))
    )
    (comp (ref "C57")
      (value "47n")
      (footprint "eagle-import:C0805")
      (libsource (lib "eagle-import") (part "C-USC0805"))
    )
    (comp (ref "C59")
      (value "0.1u")
      (footprint "eagle-import:C0805")
      (libsource (lib "eagle-import") (part "C-USC0805"))
    )
    (comp (ref "C60")
      (value "1u")
      (footprint "eagle-import:C0805")
      (libsource (lib "eagle-import") (part "C-USC0805"))
    )
    (comp (ref "C61")
      (value "10u")
      (footprint "eagle-import:C0805")
      (libsource (lib "eagle-import") (part "C-USC0805"))
    )
    (comp (ref "C62")
      (value "10u")
      (footprint "eagle-import:C0805")
      (libsource (lib "eagle-import") (part "C-USC0805"))
    )
    (comp (ref "C64")
      (value "0.1u")
      (footprint "eagle-import:C0805")
      (libsource (lib "eagle-import") (part "C-USC0805"))
    )
    (comp (ref "C65")
      (value "22u")
      (footprint "eagle-import:C0805")
      (libsource (lib "eagle-import") (part "C-USC0805"))
    )
    (comp (ref "C66")
      (value "1u")
      (footprint "eagle-import:C0805")
      (libsource (lib "eagle-import") (part "C-USC0805"))
    )
    (comp (ref "C69")
      (value "0.1u")
      (footprint "eagle-import:C0805")
      (libsource (lib "eagle-import") (part "C-USC0805"))
    )
    (comp (ref "C70")
      (value "0.1u")
      (footprint "eagle-import:C0805")
      (libsource (lib "eagle-import") (part "C-USC0805"))
    )
    (comp (ref "C71")
      (value "0.1u")
      (footprint "eagle-import:C0805")
      (libsource (lib "eagle-import") (part "C-USC0805"))
    )
    (comp (ref "C72")
      (value "0.1u")
      (footprint "eagle-import:C0805")
      (libsource (lib "eagle-import") (part "C-USC0805"))
    )
    (comp (ref "C73")
      (value "0.1u")
      (footprint "eagle-import:C0805")
      (libsource (lib "eagle-import") (part "C-USC0805"))
    )
    (comp (ref "C74")
      (value "0.1u")
      (footprint "eagle-import:C0805")
      (libsource (lib "eagle-import") (part "C-USC0805"))
    )
    (comp (ref "C75")
      (value "10u")
      (footprint "eagle-import:C0805")
      (libsource (lib "eagle-import") (part "C-USC0805"))
    )
    (comp (ref "C76")
      (value "10u")
      (footprint "eagle-import:C0805")
      (libsource (lib "eagle-import") (part "C-USC0805"))
    )
    (comp (ref "C77")
      (value "0.1u")
      (footprint "eagle-import:C0805")
      (libsource (lib "eagle-import") (part "C-USC0805"))
    )
    (comp (ref "C78")
      (value "4.7u")
      (footprint "eagle-import:C0805")
      (libsource (lib "eagle-import") (part "C-USC0805"))
    )
    (comp (ref "C79")
      (value "0.1u")
      (footprint "eagle-import:C0805")
      (libsource (lib "eagle-import") (part "C-USC0805"))
    )
    (comp (ref "C80")
      (value "0.1u")
      (footprint "eagle-import:C0805")
      (libsource (lib "eagle-import") (part "C-USC0805"))
    )
    (comp (ref "C81")
      (value "0.1u")
      (footprint "eagle-import:C0805")
      (libsource (lib "eagle-import") (part "C-USC0805"))
    )
    (comp (ref "C82")
      (value "1n")
      (footprint "eagle-import:C0805")
      (libsource (lib "eagle-import") (part "C-USC0805"))
    )
    (comp (ref "C83")
      (value "4.7u")
      (footprint "eagle-import:C0805")
      (libsource (lib "eagle-import") (part "C-USC0805"))
    )
    (comp (ref "C84")
      (value "0.1u")
      (footprint "eagle-import:C0805")
      (libsource (lib "eagle-import") (part "C-USC0805"))
    )
    (comp (ref "C85")
      (value "1n")
      (footprint "eagle-import:C0805")
      (libsource (lib "eagle-import") (part "C-USC0805"))
    )
    (comp (ref "C88")
      (value "10u")
      (footprint "eagle-import:C0805")
      (libsource (lib "eagle-import") (part "C-USC0805"))
    )
    (comp (ref "C93")
      (value "1u")
      (footprint "eagle-import:C0805")
      (libsource (lib "eagle-import") (part "C-USC0805"))
    )
    (comp (ref "C94")
      (value "0.1u")
      (footprint "eagle-import:C0805")
      (libsource (lib "eagle-import") (part "C-USC0805"))
    )
    (comp (ref "C101")
      (value "0.1u")
      (footprint "eagle-import:C0805")
      (libsource (lib "eagle-import") (part "C-USC0805"))
    )
    (comp (ref "C102")
      (value "10u")
      (footprint "eagle-import:C0805")
      (libsource (lib "eagle-import") (part "C-USC0805"))
    )
    (comp (ref "C103")
      (value "0.1u")
      (footprint "eagle-import:C0805")
      (libsource (lib "eagle-import") (part "C-USC0805"))
    )
    (comp (ref "C104")
      (value "0.1u")
      (footprint "eagle-import:C0805")
      (libsource (lib "eagle-import") (part "C-USC0805"))
    )
    (comp (ref "C105")
      (value "10u")
      (footprint "eagle-import:C0805")
      (libsource (lib "eagle-import") (part "C-USC0805"))
    )
    (comp (ref "C106")
      (value "0.1u")
      (footprint "eagle-import:C0805")
      (libsource (lib "eagle-import") (part "C-USC0805"))
    )
    (comp (ref "C107")
      (value "0.1u")
      (footprint "eagle-import:C0805")
      (libsource (lib "eagle-import") (part "C-USC0805"))
    )
    (comp (ref "C108")
      (value "10u")
      (footprint "eagle-import:C0805")
      (libsource (lib "eagle-import") (part "C-USC0805"))
    )
    (comp (ref "C109")
      (value "0.1u")
      (footprint "eagle-import:C0805")
      (libsource (lib "eagle-import") (part "C-USC0805"))
    )
    (comp (ref "C110")
      (value "0.1u")
      (footprint "eagle-import:C0805")
      (libsource (lib "eagle-import") (part "C-USC0805"))
    )
    (comp (ref "C111")
      (value "10u")
      (footprint "eagle-import:C0805")
      (libsource (lib "eagle-import") (part "C-USC0805"))
    )
    (comp (ref "C112")
      (value "0.1u")
      (footprint "eagle-import:C0805")
      (libsource (lib "eagle-import") (part "C-USC0805"))
    )
    (comp (ref "C113")
      (value "0.1u")
      (footprint "eagle-import:C0805")
      (libsource (lib "eagle-import") (part "C-USC0805"))
    )
    (comp (ref "C114")
      (value "10u")
      (footprint "eagle-import:C0805")
      (libsource (lib "eagle-import") (part "C-USC0805"))
    )
    (comp (ref "CAMERA1")
      (value "KK254_VERT_2PIN\"\"")
      (footprint "eagle-import:KK254_VERT_2PIN")
      (libsource (lib "eagle-import") (part "KK254_VERT_2PIN{dblquote}{dblquote}"))
    )
    (comp (ref "CAMERA2")
      (value "KK254_VERT_2PIN\"\"")
      (footprint "eagle-import:KK254_VERT_2PIN")
      (libsource (lib "eagle-import") (part "KK254_VERT_2PIN{dblquote}{dblquote}"))
    )
    (comp (ref "CIN1")
      (value "2.2 uF")
      (footprint "eagle-import:C1210")
      (libsource (lib "eagle-import") (part "C-USC1210"))
    )
    (comp (ref "CIN2")
      (value "2.2 uF")
      (footprint "eagle-import:C1210")
      (libsource (lib "eagle-import") (part "C-USC1210"))
    )
    (comp (ref "CIN3")
      (value "2.2 uF")
      (footprint "eagle-import:C1210")
      (libsource (lib "eagle-import") (part "C-USC1210"))
    )
    (comp (ref "CIN4")
      (value "2.2 uF")
      (footprint "eagle-import:C1210")
      (libsource (lib "eagle-import") (part "C-USC1210"))
    )
    (comp (ref "CPU_PWR")
      (value "CPU PWR")
      (footprint "eagle-import:KK254_VERT_4PIN")
      (libsource (lib "eagle-import") (part "KK254_VERT_4PIN22-29-2041"))
    )
    (comp (ref "DEPTH_SENS")
      (value "Depth Sensor")
      (footprint "eagle-import:KK254_VERT_4PIN")
      (libsource (lib "eagle-import") (part "KK254_VERT_4PIN22-29-2041"))
    )
    (comp (ref "ETHERNET")
      (value "KK254_VERT_2PIN\"\"")
      (footprint "eagle-import:KK254_VERT_2PIN")
      (libsource (lib "eagle-import") (part "KK254_VERT_2PIN{dblquote}{dblquote}"))
    )
    (comp (ref "FAN1")
      (value "KK254_VERT_2PIN\"\"")
      (footprint "eagle-import:KK254_VERT_2PIN")
      (libsource (lib "eagle-import") (part "KK254_VERT_2PIN{dblquote}{dblquote}"))
    )
    (comp (ref "FAN2")
      (value "KK254_VERT_2PIN\"\"")
      (footprint "eagle-import:KK254_VERT_2PIN")
      (libsource (lib "eagle-import") (part "KK254_VERT_2PIN{dblquote}{dblquote}"))
    )
    (comp (ref "JP1")
      (value "JP1E")
      (footprint "eagle-import:JP1")
      (libsource (lib "eagle-import") (part "JP1E"))
    )
    (comp (ref "JP2")
      (value "JP1E")
      (footprint "eagle-import:JP1")
      (libsource (lib "eagle-import") (part "JP1E"))
    )
    (comp (ref "JP3")
      (value "PINHD-1X2")
      (footprint "eagle-import:1X02")
      (libsource (lib "eagle-import") (part "PINHD-1X2"))
    )
    (comp (ref "JP4")
      (value "PINHD-1X2")
      (footprint "eagle-import:1X02")
      (libsource (lib "eagle-import") (part "PINHD-1X2"))
    )
    (comp (ref "JP5")
      (value "PINHD-1X2")
      (footprint "eagle-import:1X02")
      (libsource (lib "eagle-import") (part "PINHD-1X2"))
    )
    (comp (ref "JP6")
      (value "PINHD-1X2")
      (footprint "eagle-import:1X02")
      (libsource (lib "eagle-import") (part "PINHD-1X2"))
    )
    (comp (ref "LED1")
      (value "Red")
      (footprint "eagle-import:0805")
      (libsource (lib "eagle-import") (part "0805_LED"))
    )
    (comp (ref "LED3")
      (value "Red")
      (footprint "eagle-import:0805")
      (libsource (lib "eagle-import") (part "0805_LED"))
    )
    (comp (ref "LED4")
      (value "Green")
      (footprint "eagle-import:CHIPLED_0805")
      (libsource (lib "eagle-import") (part "LEDCHIPLED_0805"))
    )
    (comp (ref "LED5")
      (value "Green")
      (footprint "eagle-import:0805")
      (libsource (lib "eagle-import") (part "0805_LED"))
    )
    (comp (ref "LED6")
      (value "Yellow")
      (footprint "eagle-import:0805")
      (libsource (lib "eagle-import") (part "0805_LED"))
    )
    (comp (ref "LED7")
      (value "Yellow")
      (footprint "eagle-import:0805")
      (libsource (lib "eagle-import") (part "0805_LED"))
    )
    (comp (ref "LED8")
      (value "Green")
      (footprint "eagle-import:0805")
      (libsource (lib "eagle-import") (part "0805_LED"))
    )
    (comp (ref "LED9")
      (value "Green")
      (footprint "eagle-import:0805")
      (libsource (lib "eagle-import") (part "0805_LED"))
    )
    (comp (ref "PMOS1")
      (value "SSM3J353F")
      (footprint "eagle-import:SOT-346-3_S-MINI")
      (libsource (lib "eagle-import") (part "SSM3J353F"))
    )
    (comp (ref "PMOS2")
      (value "SSM3J353F")
      (footprint "eagle-import:SOT-346-3_S-MINI")
      (libsource (lib "eagle-import") (part "SSM3J353F"))
    )
    (comp (ref "R2")
      (value "R-TRIMM3314J")
      (footprint "eagle-import:RTRIM3314J")
      (libsource (lib "eagle-import") (part "R-TRIMM3314J"))
    )
    (comp (ref "R3")
      (value "R-TRIMM3314J")
      (footprint "eagle-import:RTRIM3314J")
      (libsource (lib "eagle-import") (part "R-TRIMM3314J"))
    )
    (comp (ref "R4")
      (value "10k")
      (footprint "eagle-import:R0805")
      (libsource (lib "eagle-import") (part "R-US_R0805"))
    )
    (comp (ref "R5")
      (value "21kO")
      (footprint "eagle-import:RC55")
      (libsource (lib "eagle-import") (part "R-US_RC55/H8"))
    )
    (comp (ref "R6")
      (value "2.61kO")
      (footprint "eagle-import:RC55")
      (libsource (lib "eagle-import") (part "R-US_RC55/H8"))
    )
    (comp (ref "R7")
      (value "4.7k")
      (footprint "eagle-import:R0805")
      (libsource (lib "eagle-import") (part "R-US_R0805"))
    )
    (comp (ref "R8")
      (value "4.7k")
      (footprint "eagle-import:R0805")
      (libsource (lib "eagle-import") (part "R-US_R0805"))
    )
    (comp (ref "R9")
      (value "12k")
      (footprint "eagle-import:R0805")
      (libsource (lib "eagle-import") (part "R-US_R0805"))
    )
    (comp (ref "R10")
      (value "4.2k")
      (footprint "eagle-import:R0805")
      (libsource (lib "eagle-import") (part "R-US_R0805"))
    )
    (comp (ref "R11")
      (value "4.2k")
      (footprint "eagle-import:R0805")
      (libsource (lib "eagle-import") (part "R-US_R0805"))
    )
    (comp (ref "R12")
      (value "5m")
      (footprint "eagle-import:R0805")
      (libsource (lib "eagle-import") (part "R-US_R0805"))
    )
    (comp (ref "R13")
      (value "20.8k")
      (footprint "eagle-import:R0805")
      (libsource (lib "eagle-import") (part "R-US_R0805"))
    )
    (comp (ref "R14")
      (value "51k")
      (footprint "eagle-import:R0805")
      (libsource (lib "eagle-import") (part "R-US_R0805"))
    )
    (comp (ref "R15")
      (value "5m")
      (footprint "eagle-import:R0805")
      (libsource (lib "eagle-import") (part "R-US_R0805"))
    )
    (comp (ref "R16")
      (value "10\\")
      (footprint "eagle-import:R0805")
      (libsource (lib "eagle-import") (part "R-US_R0805"))
    )
    (comp (ref "R17")
      (value "200k")
      (footprint "eagle-import:R0805")
      (libsource (lib "eagle-import") (part "R-US_R0805"))
    )
    (comp (ref "R19")
      (value "8.2k")
      (footprint "eagle-import:R0805")
      (libsource (lib "eagle-import") (part "R-US_R0805"))
    )
    (comp (ref "R20")
      (value "5.1k")
      (footprint "eagle-import:R0805")
      (libsource (lib "eagle-import") (part "R-US_R0805"))
    )
    (comp (ref "R22")
      (value "510")
      (footprint "eagle-import:R0805")
      (libsource (lib "eagle-import") (part "R-US_R0805"))
    )
    (comp (ref "R23")
      (value "51k")
      (footprint "eagle-import:R0805")
      (libsource (lib "eagle-import") (part "R-US_R0805"))
    )
    (comp (ref "R24")
      (value "5.1k")
      (footprint "eagle-import:R0805")
      (libsource (lib "eagle-import") (part "R-US_R0805"))
    )
    (comp (ref "R25")
      (value "10")
      (footprint "eagle-import:R0805")
      (libsource (lib "eagle-import") (part "R-US_R0805"))
    )
    (comp (ref "R26")
      (value "10\\")
      (footprint "eagle-import:R0805")
      (libsource (lib "eagle-import") (part "R-US_R0805"))
    )
    (comp (ref "R27")
      (value "200k")
      (footprint "eagle-import:R0805")
      (libsource (lib "eagle-import") (part "R-US_R0805"))
    )
    (comp (ref "R28")
      (value "8.2k")
      (footprint "eagle-import:R0805")
      (libsource (lib "eagle-import") (part "R-US_R0805"))
    )
    (comp (ref "R29")
      (value "6.8k")
      (footprint "eagle-import:R0805")
      (libsource (lib "eagle-import") (part "R-US_R0805"))
    )
    (comp (ref "R30")
      (value "10")
      (footprint "eagle-import:R0805")
      (libsource (lib "eagle-import") (part "R-US_R0805"))
    )
    (comp (ref "R31")
      (value "270")
      (footprint "eagle-import:R0805")
      (libsource (lib "eagle-import") (part "R-US_R0805"))
    )
    (comp (ref "R32")
      (value "1.5k")
      (footprint "eagle-import:R0805")
      (libsource (lib "eagle-import") (part "R-US_R0805"))
    )
    (comp (ref "R33")
      (value "1.2k")
      (footprint "eagle-import:R0805")
      (libsource (lib "eagle-import") (part "R-US_R0805"))
    )
    (comp (ref "R34")
      (value "68")
      (footprint "eagle-import:R0805")
      (libsource (lib "eagle-import") (part "R-US_R0805"))
    )
    (comp (ref "R35")
      (value "10")
      (footprint "eagle-import:R0805")
      (libsource (lib "eagle-import") (part "R-US_R0805"))
    )
    (comp (ref "R36")
      (value "1MO")
      (footprint "eagle-import:R0805")
      (libsource (lib "eagle-import") (part "R-US_R0805"))
    )
    (comp (ref "R37")
      (value "430")
      (footprint "eagle-import:R0805")
      (libsource (lib "eagle-import") (part "R-US_R0805"))
    )
    (comp (ref "R39")
      (value "330")
      (footprint "eagle-import:R0805")
      (libsource (lib "eagle-import") (part "R-US_R0805"))
    )
    (comp (ref "R41")
      (value "1MO")
      (footprint "eagle-import:R0805")
      (libsource (lib "eagle-import") (part "R-US_R0805"))
    )
    (comp (ref "R42")
      (value "430")
      (footprint "eagle-import:R0805")
      (libsource (lib "eagle-import") (part "R-US_R0805"))
    )
    (comp (ref "R43")
      (value "330")
      (footprint "eagle-import:R0805")
      (libsource (lib "eagle-import") (part "R-US_R0805"))
    )
    (comp (ref "R44")
      (value "1.2k")
      (footprint "eagle-import:R0805")
      (libsource (lib "eagle-import") (part "R-US_R0805"))
    )
    (comp (ref "R45")
      (value "1MO")
      (footprint "eagle-import:R0805")
      (libsource (lib "eagle-import") (part "R-US_R0805"))
    )
    (comp (ref "R46")
      (value "1.2k")
      (footprint "eagle-import:R0805")
      (libsource (lib "eagle-import") (part "R-US_R0805"))
    )
    (comp (ref "R47")
      (value "1MO")
      (footprint "eagle-import:R0805")
      (libsource (lib "eagle-import") (part "R-US_R0805"))
    )
    (comp (ref "R48")
      (value "330")
      (footprint "eagle-import:R0805")
      (libsource (lib "eagle-import") (part "R-US_R0805"))
    )
    (comp (ref "R49")
      (value "330")
      (footprint "eagle-import:R0805")
      (libsource (lib "eagle-import") (part "R-US_R0805"))
    )
    (comp (ref "R50")
      (value "1.5k")
      (footprint "eagle-import:R0805")
      (libsource (lib "eagle-import") (part "R-US_R0805"))
    )
    (comp (ref "R51")
      (value "1.5k")
      (footprint "eagle-import:R0805")
      (libsource (lib "eagle-import") (part "R-US_R0805"))
    )
    (comp (ref "SHORE_IN")
      (value "KK254_VERT_2PIN\"\"")
      (footprint "eagle-import:KK254_VERT_2PIN")
      (libsource (lib "eagle-import") (part "KK254_VERT_2PIN{dblquote}{dblquote}"))
    )
    (comp (ref "TEST-PTS")
      (value "0")
      (footprint "eagle-import:V526-0")
      (libsource (lib "eagle-import") (part "R-US_V526-0"))
    )
    (comp (ref "TEST-PTS1")
      (value "0")
      (footprint "eagle-import:V526-0")
      (libsource (lib "eagle-import") (part "R-US_V526-0"))
    )
    (comp (ref "THRUST1")
      (value "KK254_VERT_4PIN22-29-2041")
      (footprint "eagle-import:KK254_VERT_4PIN")
      (libsource (lib "eagle-import") (part "KK254_VERT_4PIN22-29-2041"))
    )
    (comp (ref "THRUST2")
      (value "KK254_VERT_4PIN22-29-2041")
      (footprint "eagle-import:KK254_VERT_4PIN")
      (libsource (lib "eagle-import") (part "KK254_VERT_4PIN22-29-2041"))
    )
    (comp (ref "THRUST3")
      (value "KK254_VERT_4PIN22-29-2041")
      (footprint "eagle-import:KK254_VERT_4PIN")
      (libsource (lib "eagle-import") (part "KK254_VERT_4PIN22-29-2041"))
    )
    (comp (ref "THRUST4")
      (value "KK254_VERT_4PIN22-29-2041")
      (footprint "eagle-import:KK254_VERT_4PIN")
      (libsource (lib "eagle-import") (part "KK254_VERT_4PIN22-29-2041"))
    )
    (comp (ref "THRUST5")
      (value "KK254_VERT_4PIN22-29-2041")
      (footprint "eagle-import:KK254_VERT_4PIN")
      (libsource (lib "eagle-import") (part "KK254_VERT_4PIN22-29-2041"))
    )
    (comp (ref "THRUST6")
      (value "KK254_VERT_4PIN22-29-2041")
      (footprint "eagle-import:KK254_VERT_4PIN")
      (libsource (lib "eagle-import") (part "KK254_VERT_4PIN22-29-2041"))
    )
    (comp (ref "THRUST7")
      (value "KK254_VERT_4PIN22-29-2041")
      (footprint "eagle-import:KK254_VERT_4PIN")
      (libsource (lib "eagle-import") (part "KK254_VERT_4PIN22-29-2041"))
    )
    (comp (ref "THRUST8")
      (value "KK254_VERT_4PIN22-29-2041")
      (footprint "eagle-import:KK254_VERT_4PIN")
      (libsource (lib "eagle-import") (part "KK254_VERT_4PIN22-29-2041"))
    )
    (comp (ref "THRUSTER_CURR_ADC")
      (value "ADS7828")
      (footprint "eagle-import:TSSOP16")
      (libsource (lib "eagle-import") (part "ADS7828"))
    )
    (comp (ref "U$1")
      (value "VTVSDO-219AB")
      (footprint "eagle-import:DO-219AB")
      (libsource (lib "eagle-import") (part "VTVSDO-219AB"))
    )
    (comp (ref "U$2")
      (value "ACS713SOIC")
      (footprint "eagle-import:ACS713-SOIC")
      (libsource (lib "eagle-import") (part "ACS713SOIC"))
    )
    (comp (ref "U$3")
      (value "TEST_PT534-5004")
      (footprint "eagle-import:534-5004")
      (libsource (lib "eagle-import") (part "TEST_PT534-5004"))
    )
    (comp (ref "U$4")
      (value "ACS713SOIC")
      (footprint "eagle-import:ACS713-SOIC")
      (libsource (lib "eagle-import") (part "ACS713SOIC"))
    )
    (comp (ref "U$5")
      (value "25A Fuse")
      (footprint "eagle-import:1.25__FUSECLIPS")
      (libsource (lib "eagle-import") (part "BOWED-1.25{dblquote}-FUSECLIPS"))
    )
    (comp (ref "U$6")
      (value "4A Fuse")
      (footprint "eagle-import:154-OMNI-BLOK")
      (libsource (lib "eagle-import") (part "154-OMNI_BLOK"))
    )
    (comp (ref "U$7")
      (value "KUHP-5XX1-XX")
      (footprint "eagle-import:KUHP_6.35MM-QUICK-CONNECT")
      (libsource (lib "eagle-import") (part "KUHP-5XX1-XX"))
    )
    (comp (ref "U$8")
      (value "ACS713SOIC")
      (footprint "eagle-import:ACS713-SOIC")
      (libsource (lib "eagle-import") (part "ACS713SOIC"))
    )
    (comp (ref "U$9")
      (value "4A Fuse")
      (footprint "eagle-import:154-OMNI-BLOK")
      (libsource (lib "eagle-import") (part "154-OMNI_BLOK"))
    )
    (comp (ref "U$10")
      (value "VTVSSOT323")
      (footprint "eagle-import:SOT323-R")
      (libsource (lib "eagle-import") (part "VTVSSOT323"))
    )
    (comp (ref "U$11")
      (value "ACS713SOIC")
      (footprint "eagle-import:ACS713-SOIC")
      (libsource (lib "eagle-import") (part "ACS713SOIC"))
    )
    (comp (ref "U$12")
      (value "4A Fuse")
      (footprint "eagle-import:154-OMNI-BLOK")
      (libsource (lib "eagle-import") (part "154-OMNI_BLOK"))
    )
    (comp (ref "U$13")
      (value "VTVSSOT323")
      (footprint "eagle-import:SOT323-R")
      (libsource (lib "eagle-import") (part "VTVSSOT323"))
    )
    (comp (ref "U$14")
      (value "ACS713SOIC")
      (footprint "eagle-import:ACS713-SOIC")
      (libsource (lib "eagle-import") (part "ACS713SOIC"))
    )
    (comp (ref "U$15")
      (value "4A Fuse")
      (footprint "eagle-import:154-OMNI-BLOK")
      (libsource (lib "eagle-import") (part "154-OMNI_BLOK"))
    )
    (comp (ref "U$16")
      (value "VTVSSOT323")
      (footprint "eagle-import:SOT323-R")
      (libsource (lib "eagle-import") (part "VTVSSOT323"))
    )
    (comp (ref "U$17")
      (value "ACS713SOIC")
      (footprint "eagle-import:ACS713-SOIC")
      (libsource (lib "eagle-import") (part "ACS713SOIC"))
    )
    (comp (ref "U$18")
      (value "4A Fuse")
      (footprint "eagle-import:154-OMNI-BLOK")
      (libsource (lib "eagle-import") (part "154-OMNI_BLOK"))
    )
    (comp (ref "U$19")
      (value "ACS713SOIC")
      (footprint "eagle-import:ACS713-SOIC")
      (libsource (lib "eagle-import") (part "ACS713SOIC"))
    )
    (comp (ref "U$20")
      (value "4A Fuse")
      (footprint "eagle-import:154-OMNI-BLOK")
      (libsource (lib "eagle-import") (part "154-OMNI_BLOK"))
    )
    (comp (ref "U$21")
      (value "VTVSSOT323")
      (footprint "eagle-import:SOT323-R")
      (libsource (lib "eagle-import") (part "VTVSSOT323"))
    )
    (comp (ref "U$22")
      (value "VTVSSOT323")
      (footprint "eagle-import:SOT323-R")
      (libsource (lib "eagle-import") (part "VTVSSOT323"))
    )
    (comp (ref "U$23")
      (value "ACS713SOIC")
      (footprint "eagle-import:ACS713-SOIC")
      (libsource (lib "eagle-import") (part "ACS713SOIC"))
    )
    (comp (ref "U$24")
      (value "BTS5090-1EJA")
      (footprint "eagle-import:SOIC8+PAD")
      (libsource (lib "eagle-import") (part "BTS5090-1EJA"))
    )
    (comp (ref "U$25")
      (value "PTN78060W")
      (footprint "eagle-import:PTN78060W")
      (libsource (lib "eagle-import") (part "PTN78060W"))
    )
    (comp (ref "U$26")
      (value "VTVSSOT323")
      (footprint "eagle-import:SOT323-R")
      (libsource (lib "eagle-import") (part "VTVSSOT323"))
    )
    (comp (ref "U$27")
      (value "4A Fuse")
      (footprint "eagle-import:154-OMNI-BLOK")
      (libsource (lib "eagle-import") (part "154-OMNI_BLOK"))
    )
    (comp (ref "U$28")
      (value "VTVSSOT323")
      (footprint "eagle-import:SOT323-R")
      (libsource (lib "eagle-import") (part "VTVSSOT323"))
    )
    (comp (ref "U$29")
      (value "ACS713SOIC")
      (footprint "eagle-import:ACS713-SOIC")
      (libsource (lib "eagle-import") (part "ACS713SOIC"))
    )
    (comp (ref "U$30")
      (value "VTVSSOT323")
      (footprint "eagle-import:SOT323-R")
      (libsource (lib "eagle-import") (part "VTVSSOT323"))
    )
    (comp (ref "U$31")
      (value "VTVSSOT323")
      (footprint "eagle-import:SOT323-R")
      (libsource (lib "eagle-import") (part "VTVSSOT323"))
    )
    (comp (ref "U$32")
      (value "VTVSSOT323")
      (footprint "eagle-import:SOT323-R")
      (libsource (lib "eagle-import") (part "VTVSSOT323"))
    )
    (comp (ref "U$33")
      (value "VTVSSOT323")
      (footprint "eagle-import:SOT323-R")
      (libsource (lib "eagle-import") (part "VTVSSOT323"))
    )
    (comp (ref "U$34")
      (value "VTVSSOT323")
      (footprint "eagle-import:SOT323-R")
      (libsource (lib "eagle-import") (part "VTVSSOT323"))
    )
    (comp (ref "U$35")
      (value "ACS713SOIC")
      (footprint "eagle-import:ACS713-SOIC")
      (libsource (lib "eagle-import") (part "ACS713SOIC"))
    )
    (comp (ref "U$36")
      (value "4A Fuse")
      (footprint "eagle-import:154-OMNI-BLOK")
      (libsource (lib "eagle-import") (part "154-OMNI_BLOK"))
    )
    (comp (ref "U$37")
      (value "4A Fuse")
      (footprint "eagle-import:154-OMNI-BLOK")
      (libsource (lib "eagle-import") (part "154-OMNI_BLOK"))
    )
    (comp (ref "U$38")
      (value "VTVSSOT323")
      (footprint "eagle-import:SOT323-R")
      (libsource (lib "eagle-import") (part "VTVSSOT323"))
    )
    (comp (ref "U$39")
      (value "ACS713SOIC")
      (footprint "eagle-import:ACS713-SOIC")
      (libsource (lib "eagle-import") (part "ACS713SOIC"))
    )
    (comp (ref "U$40")
      (value "4A Fuse")
      (footprint "eagle-import:154-OMNI-BLOK")
      (libsource (lib "eagle-import") (part "154-OMNI_BLOK"))
    )
    (comp (ref "U$41")
      (value "PTN78060W")
      (footprint "eagle-import:PTN78060W")
      (libsource (lib "eagle-import") (part "PTN78060W"))
    )
    (comp (ref "U$42")
      (value "VTVSSOT323")
      (footprint "eagle-import:SOT323-R")
      (libsource (lib "eagle-import") (part "VTVSSOT323"))
    )
    (comp (ref "U$43")
      (value "VTVSSOT323")
      (footprint "eagle-import:SOT323-R")
      (libsource (lib "eagle-import") (part "VTVSSOT323"))
    )
    (comp (ref "U$44")
      (value "VTVSSOT323")
      (footprint "eagle-import:SOT323-R")
      (libsource (lib "eagle-import") (part "VTVSSOT323"))
    )
    (comp (ref "U$45")
      (value "VTVSDO-219AB")
      (footprint "eagle-import:DO-219AB")
      (libsource (lib "eagle-import") (part "VTVSDO-219AB"))
    )
    (comp (ref "U$46")
      (value "VTVSSOT323")
      (footprint "eagle-import:SOT323-R")
      (libsource (lib "eagle-import") (part "VTVSSOT323"))
    )
    (comp (ref "U$47")
      (value "VTVSSOT323")
      (footprint "eagle-import:SOT323-R")
      (libsource (lib "eagle-import") (part "VTVSSOT323"))
    )
    (comp (ref "U$48")
      (value "LTC4364MSOP")
      (footprint "eagle-import:MSOP16")
      (libsource (lib "eagle-import") (part "LTC4364MSOP"))
    )
    (comp (ref "U$49")
      (value "STD95N2LH5")
      (footprint "eagle-import:DPAK")
      (libsource (lib "eagle-import") (part "STD95N2LH5"))
    )
    (comp (ref "U$50")
      (value "STD95N2LH5")
      (footprint "eagle-import:DPAK")
      (libsource (lib "eagle-import") (part "STD95N2LH5"))
    )
    (comp (ref "U$51")
      (value "LTC4364MSOP")
      (footprint "eagle-import:MSOP16")
      (libsource (lib "eagle-import") (part "LTC4364MSOP"))
    )
    (comp (ref "U$52")
      (value "STD95N2LH5")
      (footprint "eagle-import:DPAK")
      (libsource (lib "eagle-import") (part "STD95N2LH5"))
    )
    (comp (ref "U$53")
      (value "STD95N2LH5")
      (footprint "eagle-import:DPAK")
      (libsource (lib "eagle-import") (part "STD95N2LH5"))
    )
    (comp (ref "U$54")
      (value "TEST_PT534-5004")
      (footprint "eagle-import:534-5004")
      (libsource (lib "eagle-import") (part "TEST_PT534-5004"))
    )
    (comp (ref "U$55")
      (value "BSS138CT-NDSOT23")
      (footprint "eagle-import:SOT23")
      (libsource (lib "eagle-import") (part "BSS138CT-NDSOT23"))
    )
    (comp (ref "U$56")
      (value "74LVC1G14")
      (footprint "eagle-import:TSSOP5")
      (libsource (lib "eagle-import") (part "74LVC1G14"))
    )
    (comp (ref "U$57")
      (value "NCP1117")
      (footprint "eagle-import:SOT-223")
      (libsource (lib "eagle-import") (part "NCP1117"))
    )
    (comp (ref "U$58")
      (value "BSS138CT-NDSOT23")
      (footprint "eagle-import:SOT23")
      (libsource (lib "eagle-import") (part "BSS138CT-NDSOT23"))
    )
    (comp (ref "U$60")
      (value "TL431DBZ")
      (footprint "eagle-import:SOT-23-3")
      (libsource (lib "eagle-import") (part "TL431DBZ"))
    )
    (comp (ref "U$61")
      (value "TL431DBZ")
      (footprint "eagle-import:SOT-23-3")
      (libsource (lib "eagle-import") (part "TL431DBZ"))
    )
    (comp (ref "U$62")
      (value "VTVSSOT323")
      (footprint "eagle-import:SOT323-R")
      (libsource (lib "eagle-import") (part "VTVSSOT323"))
    )
    (comp (ref "U$63")
      (value "VTVSDO-219AB")
      (footprint "eagle-import:DO-219AB")
      (libsource (lib "eagle-import") (part "VTVSDO-219AB"))
    )
    (comp (ref "U$64")
      (value "VTVSDO-219AB")
      (footprint "eagle-import:DO-219AB")
      (libsource (lib "eagle-import") (part "VTVSDO-219AB"))
    )
    (comp (ref "U$66")
      (value "VTVSDO-219AB")
      (footprint "eagle-import:DO-219AB")
      (libsource (lib "eagle-import") (part "VTVSDO-219AB"))
    )
    (comp (ref "U$67")
      (value "VTVSSOT323")
      (footprint "eagle-import:SOT323-R")
      (libsource (lib "eagle-import") (part "VTVSSOT323"))
    )
    (comp (ref "U$68")
      (value "VTVSSOT323")
      (footprint "eagle-import:SOT323-R")
      (libsource (lib "eagle-import") (part "VTVSSOT323"))
    )
    (comp (ref "U$69")
      (value "TEST_PT534-5004")
      (footprint "eagle-import:534-5004")
      (libsource (lib "eagle-import") (part "TEST_PT534-5004"))
    )
    (comp (ref "U$70")
      (value "TEST_PT534-5004")
      (footprint "eagle-import:534-5004")
      (libsource (lib "eagle-import") (part "TEST_PT534-5004"))
    )
    (comp (ref "U$71")
      (value "TEST_PT534-5004")
      (footprint "eagle-import:534-5004")
      (libsource (lib "eagle-import") (part "TEST_PT534-5004"))
    )
    (comp (ref "U$72")
      (value "TEST_PT534-5004")
      (footprint "eagle-import:534-5004")
      (libsource (lib "eagle-import") (part "TEST_PT534-5004"))
    )
    (comp (ref "U$73")
      (value "TEST_PT534-5004")
      (footprint "eagle-import:534-5004")
      (libsource (lib "eagle-import") (part "TEST_PT534-5004"))
    )
    (comp (ref "U$74")
      (value "TEST_PT534-5004")
      (footprint "eagle-import:534-5004")
      (libsource (lib "eagle-import") (part "TEST_PT534-5004"))
    )
    (comp (ref "U$75")
      (value "TEST_PT534-5004")
      (footprint "eagle-import:534-5004")
      (libsource (lib "eagle-import") (part "TEST_PT534-5004"))
    )
    (comp (ref "U$76")
      (value "TEST_PT534-5004")
      (footprint "eagle-import:534-5004")
      (libsource (lib "eagle-import") (part "TEST_PT534-5004"))
    )
    (comp (ref "U1")
      (value "PCA9685")
      (footprint "eagle-import:TSSOP-28_4MM")
      (libsource (lib "eagle-import") (part "PCA9685"))
    )
    (comp (ref "V-THRUST_CURR_ADC")
      (value "ADC121C021")
      (footprint "eagle-import:VSSOP-8")
      (libsource (lib "eagle-import") (part "ADC121C021"))
    )
    (comp (ref "V-THRUST_LED")
      (value "0805_LED")
      (footprint "eagle-import:0805")
      (libsource (lib "eagle-import") (part "0805_LED"))
    )
    (comp (ref "V-THRUST_OUT")
      (value "Vin_OUT")
      (footprint "eagle-import:KK254_VERT_2PIN")
      (libsource (lib "eagle-import") (part "KK254_VERT_2PIN{dblquote}{dblquote}"))
    )
    (comp (ref "V-THRUST_VOLTAGE")
      (value "INA219SOT23")
      (footprint "eagle-import:SOT-23-8")
      (libsource (lib "eagle-import") (part "INA219SOT23"))
    )
  )
  (nets
    (net (code "1") (name "+3V3") (class "Default")
      (node (ref "2PIN_2") (pin "P$1") (pinfunction "P$1_P$1") (pintype "bidirectional"))
      (node (ref "BME280") (pin "P$2") (pinfunction "~{CS}_P$2") (pintype "bidirectional"))
      (node (ref "BME280") (pin "P$5") (pinfunction "SDO/ADR_P$5") (pintype "bidirectional"))
      (node (ref "BME280") (pin "P$6") (pinfunction "VDDIO_P$6") (pintype "bidirectional"))
      (node (ref "BME280") (pin "P$8") (pinfunction "VDD_P$8") (pintype "bidirectional"))
      (node (ref "C24") (pin "1") (pinfunction "1_1") (pintype "passive"))
      (node (ref "C25") (pin "1") (pinfunction "1_1") (pintype "passive"))
      (node (ref "C26") (pin "1") (pinfunction "1_1") (pintype "passive"))
      (node (ref "C83") (pin "1") (pinfunction "1_1") (pintype "passive"))
      (node (ref "C84") (pin "1") (pinfunction "1_1") (pintype "passive"))
      (node (ref "C85") (pin "1") (pinfunction "1_1") (pintype "passive"))
      (node (ref "R10") (pin "2") (pinfunction "2_2") (pintype "passive"))
      (node (ref "R11") (pin "2") (pinfunction "2_2") (pintype "passive"))
      (node (ref "R34") (pin "2") (pinfunction "2_2") (pintype "passive"))
      (node (ref "U$3") (pin "P$1") (pinfunction "1_P$1") (pintype "bidirectional"))
    )
    (net (code "2") (name "+5V") (class "Default")
      (node (ref "12V_CURR_ADC") (pin "P$5") (pinfunction "VDD_P$5") (pintype "bidirectional"))
      (node (ref "12V_VOLTAGE") (pin "P$4") (pinfunction "VS_P$4") (pintype "bidirectional"))
      (node (ref "12V_VOLTAGE") (pin "P$8") (pinfunction "A1_P$8") (pintype "bidirectional"))
      (node (ref "2PIN_1") (pin "P$1") (pinfunction "P$1_P$1") (pintype "bidirectional"))
      (node (ref "2PIN_3") (pin "P$1") (pinfunction "P$1_P$1") (pintype "bidirectional"))
      (node (ref "5V_CURR_ADC") (pin "P$5") (pinfunction "VDD_P$5") (pintype "bidirectional"))
      (node (ref "5V_CURR_ADC") (pin "P$6") (pinfunction "ADR1_P$6") (pintype "bidirectional"))
      (node (ref "5V_OUT") (pin "P$1") (pinfunction "P$1_P$1") (pintype "bidirectional"))
      (node (ref "5V_VOLTAGE") (pin "P$4") (pinfunction "VS_P$4") (pintype "bidirectional"))
      (node (ref "C1") (pin "1") (pinfunction "1_1") (pintype "passive"))
      (node (ref "C103") (pin "1") (pinfunction "1_1") (pintype "passive"))
      (node (ref "C106") (pin "1") (pinfunction "1_1") (pintype "passive"))
      (node (ref "C109") (pin "1") (pinfunction "1_1") (pintype "passive"))
      (node (ref "C11") (pin "1") (pinfunction "1_1") (pintype "passive"))
      (node (ref "C112") (pin "1") (pinfunction "1_1") (pintype "passive"))
      (node (ref "C13") (pin "1") (pinfunction "1_1") (pintype "passive"))
      (node (ref "C14") (pin "1") (pinfunction "1_1") (pintype "passive"))
      (node (ref "C19") (pin "1") (pinfunction "1_1") (pintype "passive"))
      (node (ref "C2") (pin "1") (pinfunction "1_1") (pintype "passive"))
      (node (ref "C48") (pin "1") (pinfunction "1_1") (pintype "passive"))
      (node (ref "C5") (pin "1") (pinfunction "1_1") (pintype "passive"))
      (node (ref "C53") (pin "1") (pinfunction "1_1") (pintype "passive"))
      (node (ref "C59") (pin "1") (pinfunction "1_1") (pintype "passive"))
      (node (ref "C64") (pin "1") (pinfunction "1_1") (pintype "passive"))
      (node (ref "C66") (pin "1") (pinfunction "1_1") (pintype "passive"))
      (node (ref "C69") (pin "1") (pinfunction "1_1") (pintype "passive"))
      (node (ref "C7") (pin "1") (pinfunction "1_1") (pintype "passive"))
      (node (ref "C70") (pin "1") (pinfunction "1_1") (pintype "passive"))
      (node (ref "C71") (pin "1") (pinfunction "1_1") (pintype "passive"))
      (node (ref "C72") (pin "1") (pinfunction "1_1") (pintype "passive"))
      (node (ref "C73") (pin "1") (pinfunction "1_1") (pintype "passive"))
      (node (ref "C79") (pin "1") (pinfunction "1_1") (pintype "passive"))
      (node (ref "C8") (pin "1") (pinfunction "1_1") (pintype "passive"))
      (node (ref "C81") (pin "1") (pinfunction "1_1") (pintype "passive"))
      (node (ref "C82") (pin "1") (pinfunction "1_1") (pintype "passive"))
      (node (ref "C93") (pin "1") (pinfunction "1_1") (pintype "passive"))
      (node (ref "C94") (pin "1") (pinfunction "1_1") (pintype "passive"))
      (node (ref "DEPTH_SENS") (pin "P$4") (pinfunction "P$4_P$4") (pintype "bidirectional"))
      (node (ref "ETHERNET") (pin "P$1") (pinfunction "P$1_P$1") (pintype "bidirectional"))
      (node (ref "FAN1") (pin "P$1") (pinfunction "P$1_P$1") (pintype "bidirectional"))
      (node (ref "FAN2") (pin "P$1") (pinfunction "P$1_P$1") (pintype "bidirectional"))
      (node (ref "R31") (pin "2") (pinfunction "2_2") (pintype "passive"))
      (node (ref "R35") (pin "1") (pinfunction "1_1") (pintype "passive"))
      (node (ref "R7") (pin "2") (pinfunction "2_2") (pintype "passive"))
      (node (ref "R8") (pin "2") (pinfunction "2_2") (pintype "passive"))
      (node (ref "THRUSTER_CURR_ADC") (pin "10") (pinfunction "REF_10") (pintype "bidirectional"))
      (node (ref "THRUSTER_CURR_ADC") (pin "16") (pinfunction "VDD_16") (pintype "bidirectional"))
      (node (ref "U$11") (pin "P$8") (pinfunction "VCC_P$8") (pintype "bidirectional"))
      (node (ref "U$14") (pin "P$8") (pinfunction "VCC_P$8") (pintype "bidirectional"))
      (node (ref "U$17") (pin "P$8") (pinfunction "VCC_P$8") (pintype "bidirectional"))
      (node (ref "U$19") (pin "P$8") (pinfunction "VCC_P$8") (pintype "bidirectional"))
      (node (ref "U$2") (pin "P$8") (pinfunction "VCC_P$8") (pintype "bidirectional"))
      (node (ref "U$20") (pin "P$2") (pinfunction "P$2_P$2") (pintype "bidirectional"))
      (node (ref "U$21") (pin "1") (pinfunction "C_1") (pintype "passive"))
      (node (ref "U$21") (pin "2") (pinfunction "C_2") (pintype "passive"))
      (node (ref "U$23") (pin "P$8") (pinfunction "VCC_P$8") (pintype "bidirectional"))
      (node (ref "U$29") (pin "P$8") (pinfunction "VCC_P$8") (pintype "bidirectional"))
      (node (ref "U$35") (pin "P$8") (pinfunction "VCC_P$8") (pintype "bidirectional"))
      (node (ref "U$39") (pin "P$8") (pinfunction "VCC_P$8") (pintype "bidirectional"))
      (node (ref "U$4") (pin "P$8") (pinfunction "VCC_P$8") (pintype "bidirectional"))
      (node (ref "U$42") (pin "1") (pinfunction "C_1") (pintype "passive"))
      (node (ref "U$42") (pin "2") (pinfunction "C_2") (pintype "passive"))
      (node (ref "U$43") (pin "1") (pinfunction "C_1") (pintype "passive"))
      (node (ref "U$43") (pin "2") (pinfunction "C_2") (pintype "passive"))
      (node (ref "U$44") (pin "1") (pinfunction "C_1") (pintype "passive"))
      (node (ref "U$44") (pin "2") (pinfunction "C_2") (pintype "passive"))
      (node (ref "U$46") (pin "1") (pinfunction "C_1") (pintype "passive"))
      (node (ref "U$46") (pin "2") (pinfunction "C_2") (pintype "passive"))
      (node (ref "U$47") (pin "1") (pinfunction "C_1") (pintype "passive"))
      (node (ref "U$47") (pin "2") (pinfunction "C_2") (pintype "passive"))
      (node (ref "U$69") (pin "P$1") (pinfunction "1_P$1") (pintype "bidirectional"))
      (node (ref "U$8") (pin "P$8") (pinfunction "VCC_P$8") (pintype "bidirectional"))
      (node (ref "U1") (pin "1") (pinfunction "A0_1") (pintype "bidirectional"))
      (node (ref "U1") (pin "2") (pinfunction "A1_2") (pintype "bidirectional"))
      (node (ref "U1") (pin "24") (pinfunction "A5_24") (pintype "bidirectional"))
      (node (ref "U1") (pin "28") (pinfunction "VDD_28") (pintype "bidirectional"))
      (node (ref "U1") (pin "3") (pinfunction "A2_3") (pintype "bidirectional"))
      (node (ref "U1") (pin "4") (pinfunction "A3_4") (pintype "bidirectional"))
      (node (ref "U1") (pin "5") (pinfunction "A4_5") (pintype "bidirectional"))
      (node (ref "V-THRUST_CURR_ADC") (pin "P$3") (pinfunction "ADR0_P$3") (pintype "bidirectional"))
      (node (ref "V-THRUST_CURR_ADC") (pin "P$5") (pinfunction "VDD_P$5") (pintype "bidirectional"))
      (node (ref "V-THRUST_CURR_ADC") (pin "P$6") (pinfunction "ADR1_P$6") (pintype "bidirectional"))
      (node (ref "V-THRUST_VOLTAGE") (pin "P$4") (pinfunction "VS_P$4") (pintype "bidirectional"))
      (node (ref "V-THRUST_VOLTAGE") (pin "P$7") (pinfunction "A0_P$7") (pintype "bidirectional"))
      (node (ref "V-THRUST_VOLTAGE") (pin "P$8") (pinfunction "A1_P$8") (pintype "bidirectional"))
    )
    (net (code "3") (name "+12V") (class "Default")
      (node (ref "12V_OUT") (pin "P$1") (pinfunction "P$1_P$1") (pintype "bidirectional"))
      (node (ref "C16") (pin "1") (pinfunction "1_1") (pintype "passive"))
      (node (ref "C33") (pin "1") (pinfunction "1_1") (pintype "passive"))
      (node (ref "C45") (pin "1") (pinfunction "1_1") (pintype "passive"))
      (node (ref "C49") (pin "1") (pinfunction "1_1") (pintype "passive"))
      (node (ref "C77") (pin "1") (pinfunction "1_1") (pintype "passive"))
      (node (ref "C78") (pin "1") (pinfunction "1_1") (pintype "passive"))
      (node (ref "CPU_PWR") (pin "P$3") (pinfunction "P$3_P$3") (pintype "bidirectional"))
      (node (ref "CPU_PWR") (pin "P$4") (pinfunction "P$4_P$4") (pintype "bidirectional"))
      (node (ref "JP4") (pin "1") (pinfunction "1_1") (pintype "passive"))
      (node (ref "R25") (pin "1") (pinfunction "1_1") (pintype "passive"))
      (node (ref "R33") (pin "2") (pinfunction "2_2") (pintype "passive"))
      (node (ref "U$1") (pin "P$2") (pinfunction "C_P$2") (pintype "passive"))
      (node (ref "U$24") (pin "PAD") (pinfunction "VS_PAD") (pintype "bidirectional"))
      (node (ref "U$36") (pin "P$2") (pinfunction "P$2_P$2") (pintype "bidirectional"))
      (node (ref "U$63") (pin "P$2") (pinfunction "C_P$2") (pintype "passive"))
      (node (ref "U$64") (pin "P$2") (pinfunction "C_P$2") (pintype "passive"))
      (node (ref "U$70") (pin "P$1") (pinfunction "1_P$1") (pintype "bidirectional"))
    )
    (net (code "4") (name "/5V") (class "Default")
      (node (ref "C36") (pin "1") (pinfunction "1_1") (pintype "passive"))
      (node (ref "C62") (pin "1") (pinfunction "1_1") (pintype "passive"))
      (node (ref "JP3") (pin "1") (pinfunction "1_1") (pintype "passive"))
      (node (ref "R29") (pin "2") (pinfunction "2_2") (pintype "passive"))
      (node (ref "U$56") (pin "P$5") (pinfunction "VDD_P$5") (pintype "bidirectional"))
      (node (ref "U$57") (pin "P$2") (pinfunction "VOUT_P$2") (pintype "bidirectional"))
      (node (ref "U$57") (pin "P$4") (pinfunction "VOUT_P$4") (pintype "bidirectional"))
    )
    (net (code "5") (name "/SHDN_SW") (class "Default")
      (node (ref "2PIN_5") (pin "P$1") (pinfunction "P$1_P$1") (pintype "bidirectional"))
      (node (ref "R22") (pin "1") (pinfunction "1_1") (pintype "passive"))
      (node (ref "R29") (pin "1") (pinfunction "1_1") (pintype "passive"))
      (node (ref "U$62") (pin "1") (pinfunction "C_1") (pintype "passive"))
      (node (ref "U$62") (pin "2") (pinfunction "C_2") (pintype "passive"))
    )
    (net (code "6") (name "/T1_PWM") (class "Default")
      (node (ref "THRUST1") (pin "P$2") (pinfunction "P$2_P$2") (pintype "bidirectional"))
      (node (ref "U1") (pin "6") (pinfunction "CH0_6") (pintype "bidirectional"))
    )
    (net (code "7") (name "/T2_CURR") (class "Default")
      (node (ref "THRUSTER_CURR_ADC") (pin "2") (pinfunction "CH1_2") (pintype "bidirectional"))
      (node (ref "U$8") (pin "P$7") (pinfunction "VIOUT_P$7") (pintype "bidirectional"))
    )
    (net (code "8") (name "/T2_PWM") (class "Default")
      (node (ref "THRUST2") (pin "P$2") (pinfunction "P$2_P$2") (pintype "bidirectional"))
      (node (ref "U1") (pin "7") (pinfunction "CH1_7") (pintype "bidirectional"))
    )
    (net (code "9") (name "/T3_PWM") (class "Default")
      (node (ref "THRUST3") (pin "P$2") (pinfunction "P$2_P$2") (pintype "bidirectional"))
      (node (ref "U1") (pin "8") (pinfunction "CH2_8") (pintype "bidirectional"))
    )
    (net (code "10") (name "/T4_PWM") (class "Default")
      (node (ref "THRUST4") (pin "P$2") (pinfunction "P$2_P$2") (pintype "bidirectional"))
      (node (ref "U1") (pin "9") (pinfunction "CH3_9") (pintype "bidirectional"))
    )
    (net (code "11") (name "/T5_PWM") (class "Default")
      (node (ref "THRUST5") (pin "P$2") (pinfunction "P$2_P$2") (pintype "bidirectional"))
      (node (ref "U1") (pin "10") (pinfunction "CH4_10") (pintype "bidirectional"))
    )
    (net (code "12") (name "/T6_PWM") (class "Default")
      (node (ref "THRUST6") (pin "P$2") (pinfunction "P$2_P$2") (pintype "bidirectional"))
      (node (ref "U1") (pin "11") (pinfunction "CH5_11") (pintype "bidirectional"))
    )
    (net (code "13") (name "/T7_PWM") (class "Default")
      (node (ref "THRUST7") (pin "P$2") (pinfunction "P$2_P$2") (pintype "bidirectional"))
      (node (ref "U1") (pin "12") (pinfunction "CH6_12") (pintype "bidirectional"))
    )
    (net (code "14") (name "/T8_PWM") (class "Default")
      (node (ref "THRUST8") (pin "P$2") (pinfunction "P$2_P$2") (pintype "bidirectional"))
      (node (ref "U1") (pin "13") (pinfunction "CH7_13") (pintype "bidirectional"))
    )
    (net (code "15") (name "/V_BATT1") (class "Default")
      (node (ref "BATT1_IN") (pin "P$1") (pinfunction "P$1_P$1") (pintype "bidirectional"))
      (node (ref "C34") (pin "1") (pinfunction "1_1") (pintype "passive"))
      (node (ref "C61") (pin "1") (pinfunction "1_1") (pintype "passive"))
      (node (ref "LED4") (pin "A") (pinfunction "A_A") (pintype "passive"))
      (node (ref "PMOS2") (pin "P$3") (pinfunction "S_P$3") (pintype "bidirectional"))
      (node (ref "R27") (pin "2") (pinfunction "2_2") (pintype "passive"))
      (node (ref "R3") (pin "3") (pinfunction "A_3") (pintype "passive"))
      (node (ref "R41") (pin "2") (pinfunction "2_2") (pintype "passive"))
      (node (ref "R45") (pin "2") (pinfunction "2_2") (pintype "passive"))
      (node (ref "R49") (pin "2") (pinfunction "2_2") (pintype "passive"))
      (node (ref "R51") (pin "2") (pinfunction "2_2") (pintype "passive"))
      (node (ref "U$48") (pin "VCC") (pinfunction "VCC_VCC") (pintype "bidirectional"))
      (node (ref "U$49") (pin "TAB") (pinfunction "D_TAB") (pintype "bidirectional"))
      (node (ref "U$57") (pin "P$3") (pinfunction "VIN_P$3") (pintype "bidirectional"))
      (node (ref "U$68") (pin "1") (pinfunction "C_1") (pintype "passive"))
      (node (ref "U$68") (pin "2") (pinfunction "C_2") (pintype "passive"))
      (node (ref "U$75") (pin "P$1") (pinfunction "1_P$1") (pintype "bidirectional"))
    )
    (net (code "16") (name "/V_BATT2") (class "Default")
      (node (ref "BATT2_IN") (pin "P$1") (pinfunction "P$1_P$1") (pintype "bidirectional"))
      (node (ref "C35") (pin "1") (pinfunction "1_1") (pintype "passive"))
      (node (ref "LED5") (pin "P$1") (pinfunction "A_P$1") (pintype "passive"))
      (node (ref "PMOS1") (pin "P$3") (pinfunction "S_P$3") (pintype "bidirectional"))
      (node (ref "R17") (pin "2") (pinfunction "2_2") (pintype "passive"))
      (node (ref "R2") (pin "3") (pinfunction "A_3") (pintype "passive"))
      (node (ref "R36") (pin "2") (pinfunction "2_2") (pintype "passive"))
      (node (ref "R47") (pin "2") (pinfunction "2_2") (pintype "passive"))
      (node (ref "R48") (pin "2") (pinfunction "2_2") (pintype "passive"))
      (node (ref "R50") (pin "2") (pinfunction "2_2") (pintype "passive"))
      (node (ref "U$51") (pin "VCC") (pinfunction "VCC_VCC") (pintype "bidirectional"))
      (node (ref "U$52") (pin "TAB") (pinfunction "D_TAB") (pintype "bidirectional"))
      (node (ref "U$67") (pin "1") (pinfunction "C_1") (pintype "passive"))
      (node (ref "U$67") (pin "2") (pinfunction "C_2") (pintype "passive"))
      (node (ref "U$74") (pin "P$1") (pinfunction "1_P$1") (pintype "bidirectional"))
    )
    (net (code "17") (name "/V_THRUST1") (class "Default")
      (node (ref "THRUST1") (pin "P$4") (pinfunction "P$4_P$4") (pintype "bidirectional"))
      (node (ref "U$31") (pin "1") (pinfunction "C_1") (pintype "passive"))
      (node (ref "U$31") (pin "2") (pinfunction "C_2") (pintype "passive"))
      (node (ref "U$6") (pin "P$2") (pinfunction "P$2_P$2") (pintype "bidirectional"))
    )
    (net (code "18") (name "5V_CURR") (class "Default")
      (node (ref "C50") (pin "P$1") (pinfunction "+_P$1") (pintype "passive"))
      (node (ref "C51") (pin "1") (pinfunction "1_1") (pintype "passive"))
      (node (ref "U$2") (pin "P$1") (pinfunction "IP+_P$1") (pintype "bidirectional"))
      (node (ref "U$2") (pin "P$2") (pinfunction "IP+_P$2") (pintype "bidirectional"))
      (node (ref "U$25") (pin "P$5") (pinfunction "VO_P$5") (pintype "bidirectional"))
      (node (ref "U$25") (pin "P$7") (pinfunction "VOSENSE_P$7") (pintype "bidirectional"))
    )
    (net (code "19") (name "12V_CURR") (class "Default")
      (node (ref "C38") (pin "P$1") (pinfunction "+_P$1") (pintype "passive"))
      (node (ref "C40") (pin "1") (pinfunction "1_1") (pintype "passive"))
      (node (ref "U$35") (pin "P$1") (pinfunction "IP+_P$1") (pintype "bidirectional"))
      (node (ref "U$35") (pin "P$2") (pinfunction "IP+_P$2") (pintype "bidirectional"))
      (node (ref "U$41") (pin "P$5") (pinfunction "VO_P$5") (pintype "bidirectional"))
      (node (ref "U$41") (pin "P$7") (pinfunction "VOSENSE_P$7") (pintype "bidirectional"))
    )
    (net (code "20") (name "GND") (class "Default")
      (node (ref "12V_CURR_ADC") (pin "P$3") (pinfunction "ADR0_P$3") (pintype "bidirectional"))
      (node (ref "12V_CURR_ADC") (pin "P$6") (pinfunction "ADR1_P$6") (pintype "bidirectional"))
      (node (ref "12V_CURR_ADC") (pin "P$7") (pinfunction "GND_P$7") (pintype "bidirectional"))
      (node (ref "12V_LED") (pin "P$2") (pinfunction "C_P$2") (pintype "passive"))
      (node (ref "12V_OUT") (pin "P$2") (pinfunction "P$2_P$2") (pintype "bidirectional"))
      (node (ref "12V_VOLTAGE") (pin "P$3") (pinfunction "GND_P$3") (pintype "bidirectional"))
      (node (ref "12V_VOLTAGE") (pin "P$7") (pinfunction "A0_P$7") (pintype "bidirectional"))
      (node (ref "2PIN_2") (pin "P$2") (pinfunction "P$2_P$2") (pintype "bidirectional"))
      (node (ref "2PIN_3") (pin "P$2") (pinfunction "P$2_P$2") (pintype "bidirectional"))
      (node (ref "2PIN_5") (pin "P$2") (pinfunction "P$2_P$2") (pintype "bidirectional"))
      (node (ref "3V3_LED") (pin "P$2") (pinfunction "C_P$2") (pintype "passive"))
      (node (ref "5V_CURR_ADC") (pin "P$3") (pinfunction "ADR0_P$3") (pintype "bidirectional"))
      (node (ref "5V_CURR_ADC") (pin "P$7") (pinfunction "GND_P$7") (pintype "bidirectional"))
      (node (ref "5V_LED") (pin "P$2") (pinfunction "C_P$2") (pintype "passive"))
      (node (ref "5V_OUT") (pin "P$2") (pinfunction "P$2_P$2") (pintype "bidirectional"))
      (node (ref "5V_VOLTAGE") (pin "P$3") (pinfunction "GND_P$3") (pintype "bidirectional"))
      (node (ref "5V_VOLTAGE") (pin "P$7") (pinfunction "A0_P$7") (pintype "bidirectional"))
      (node (ref "5V_VOLTAGE") (pin "P$8") (pinfunction "A1_P$8") (pintype "bidirectional"))
      (node (ref "AUDIO") (pin "P$2") (pinfunction "P$2_P$2") (pintype "bidirectional"))
      (node (ref "AUDIO1") (pin "P$2") (pinfunction "P$2_P$2") (pintype "bidirectional"))
      (node (ref "BATT1_IN") (pin "P$2") (pinfunction "P$2_P$2") (pintype "bidirectional"))
      (node (ref "BATT2_IN") (pin "P$2") (pinfunction "P$2_P$2") (pintype "bidirectional"))
      (node (ref "BME280") (pin "P$1") (pinfunction "GND1_P$1") (pintype "bidirectional"))
      (node (ref "BME280") (pin "P$7") (pinfunction "GND2_P$7") (pintype "bidirectional"))
      (node (ref "C1") (pin "2") (pinfunction "2_2") (pintype "passive"))
      (node (ref "C10") (pin "2") (pinfunction "2_2") (pintype "passive"))
      (node (ref "C101") (pin "2") (pinfunction "2_2") (pintype "passive"))
      (node (ref "C102") (pin "2") (pinfunction "2_2") (pintype "passive"))
      (node (ref "C103") (pin "2") (pinfunction "2_2") (pintype "passive"))
      (node (ref "C104") (pin "2") (pinfunction "2_2") (pintype "passive"))
      (node (ref "C105") (pin "2") (pinfunction "2_2") (pintype "passive"))
      (node (ref "C106") (pin "2") (pinfunction "2_2") (pintype "passive"))
      (node (ref "C107") (pin "2") (pinfunction "2_2") (pintype "passive"))
      (node (ref "C108") (pin "2") (pinfunction "2_2") (pintype "passive"))
      (node (ref "C109") (pin "2") (pinfunction "2_2") (pintype "passive"))
      (node (ref "C11") (pin "2") (pinfunction "2_2") (pintype "passive"))
      (node (ref "C110") (pin "2") (pinfunction "2_2") (pintype "passive"))
      (node (ref "C111") (pin "2") (pinfunction "2_2") (pintype "passive"))
      (node (ref "C112") (pin "2") (pinfunction "2_2") (pintype "passive"))
      (node (ref "C113") (pin "2") (pinfunction "2_2") (pintype "passive"))
      (node (ref "C114") (pin "2") (pinfunction "2_2") (pintype "passive"))
      (node (ref "C12") (pin "2") (pinfunction "2_2") (pintype "passive"))
      (node (ref "C13") (pin "2") (pinfunction "2_2") (pintype "passive"))
      (node (ref "C14") (pin "2") (pinfunction "2_2") (pintype "passive"))
      (node (ref "C15") (pin "2") (pinfunction "2_2") (pintype "passive"))
      (node (ref "C16") (pin "2") (pinfunction "2_2") (pintype "passive"))
      (node (ref "C17") (pin "2") (pinfunction "2_2") (pintype "passive"))
      (node (ref "C18") (pin "2") (pinfunction "2_2") (pintype "passive"))
      (node (ref "C19") (pin "2") (pinfunction "2_2") (pintype "passive"))
      (node (ref "C2") (pin "2") (pinfunction "2_2") (pintype "passive"))
      (node (ref "C20") (pin "2") (pinfunction "2_2") (pintype "passive"))
      (node (ref "C21") (pin "2") (pinfunction "2_2") (pintype "passive"))
      (node (ref "C22") (pin "2") (pinfunction "2_2") (pintype "passive"))
      (node (ref "C23") (pin "2") (pinfunction "2_2") (pintype "passive"))
      (node (ref "C24") (pin "2") (pinfunction "2_2") (pintype "passive"))
      (node (ref "C25") (pin "2") (pinfunction "2_2") (pintype "passive"))
      (node (ref "C26") (pin "2") (pinfunction "2_2") (pintype "passive"))
      (node (ref "C27") (pin "2") (pinfunction "2_2") (pintype "passive"))
      (node (ref "C28") (pin "2") (pinfunction "2_2") (pintype "passive"))
      (node (ref "C29") (pin "2") (pinfunction "2_2") (pintype "passive"))
      (node (ref "C3") (pin "2") (pinfunction "2_2") (pintype "passive"))
      (node (ref "C30") (pin "2") (pinfunction "2_2") (pintype "passive"))
      (node (ref "C31") (pin "2") (pinfunction "2_2") (pintype "passive"))
      (node (ref "C33") (pin "2") (pinfunction "2_2") (pintype "passive"))
      (node (ref "C34") (pin "2") (pinfunction "2_2") (pintype "passive"))
      (node (ref "C35") (pin "2") (pinfunction "2_2") (pintype "passive"))
      (node (ref "C36") (pin "2") (pinfunction "2_2") (pintype "passive"))
      (node (ref "C37") (pin "2") (pinfunction "2_2") (pintype "passive"))
      (node (ref "C38") (pin "P$2") (pinfunction "-_P$2") (pintype "passive"))
      (node (ref "C4") (pin "2") (pinfunction "2_2") (pintype "passive"))
      (node (ref "C40") (pin "2") (pinfunction "2_2") (pintype "passive"))
      (node (ref "C43") (pin "-") (pinfunction "-_-") (pintype "passive"))
      (node (ref "C44") (pin "-") (pinfunction "-_-") (pintype "passive"))
      (node (ref "C45") (pin "2") (pinfunction "2_2") (pintype "passive"))
      (node (ref "C46") (pin "2") (pinfunction "2_2") (pintype "passive"))
      (node (ref "C47") (pin "2") (pinfunction "2_2") (pintype "passive"))
      (node (ref "C48") (pin "2") (pinfunction "2_2") (pintype "passive"))
      (node (ref "C49") (pin "2") (pinfunction "2_2") (pintype "passive"))
      (node (ref "C5") (pin "2") (pinfunction "2_2") (pintype "passive"))
      (node (ref "C50") (pin "P$2") (pinfunction "-_P$2") (pintype "passive"))
      (node (ref "C51") (pin "2") (pinfunction "2_2") (pintype "passive"))
      (node (ref "C53") (pin "2") (pinfunction "2_2") (pintype "passive"))
      (node (ref "C57") (pin "2") (pinfunction "2_2") (pintype "passive"))
      (node (ref "C59") (pin "2") (pinfunction "2_2") (pintype "passive"))
      (node (ref "C6") (pin "2") (pinfunction "2_2") (pintype "passive"))
      (node (ref "C60") (pin "2") (pinfunction "2_2") (pintype "passive"))
      (node (ref "C61") (pin "2") (pinfunction "2_2") (pintype "passive"))
      (node (ref "C62") (pin "2") (pinfunction "2_2") (pintype "passive"))
      (node (ref "C64") (pin "2") (pinfunction "2_2") (pintype "passive"))
      (node (ref "C65") (pin "2") (pinfunction "2_2") (pintype "passive"))
      (node (ref "C66") (pin "2") (pinfunction "2_2") (pintype "passive"))
      (node (ref "C69") (pin "2") (pinfunction "2_2") (pintype "passive"))
      (node (ref "C7") (pin "2") (pinfunction "2_2") (pintype "passive"))
      (node (ref "C70") (pin "2") (pinfunction "2_2") (pintype "passive"))
      (node (ref "C71") (pin "2") (pinfunction "2_2") (pintype "passive"))
      (node (ref "C72") (pin "2") (pinfunction "2_2") (pintype "passive"))
      (node (ref "C73") (pin "2") (pinfunction "2_2") (pintype "passive"))
      (node (ref "C74") (pin "2") (pinfunction "2_2") (pintype "passive"))
      (node (ref "C75") (pin "2") (pinfunction "2_2") (pintype "passive"))
      (node (ref "C76") (pin "2") (pinfunction "2_2") (pintype "passive"))
      (node (ref "C77") (pin "2") (pinfunction "2_2") (pintype "passive"))
      (node (ref "C78") (pin "2") (pinfunction "2_2") (pintype "passive"))
      (node (ref "C79") (pin "2") (pinfunction "2_2") (pintype "passive"))
      (node (ref "C8") (pin "2") (pinfunction "2_2") (pintype "passive"))
      (node (ref "C80") (pin "2") (pinfunction "2_2") (pintype "passive"))
      (node (ref "C81") (pin "2") (pinfunction "2_2") (pintype "passive"))
      (node (ref "C82") (pin "2") (pinfunction "2_2") (pintype "passive"))
      (node (ref "C83") (pin "2") (pinfunction "2_2") (pintype "passive"))
      (node (ref "C84") (pin "2") (pinfunction "2_2") (pintype "passive"))
      (node (ref "C85") (pin "2") (pinfunction "2_2") (pintype "passive"))
      (node (ref "C88") (pin "2") (pinfunction "2_2") (pintype "passive"))
      (node (ref "C9") (pin "2") (pinfunction "2_2") (pintype "passive"))
      (node (ref "C93") (pin "2") (pinfunction "2_2") (pintype "passive"))
      (node (ref "C94") (pin "2") (pinfunction "2_2") (pintype "passive"))
      (node (ref "CAMERA1") (pin "P$2") (pinfunction "P$2_P$2") (pintype "bidirectional"))
      (node (ref "CAMERA2") (pin "P$2") (pinfunction "P$2_P$2") (pintype "bidirectional"))
      (node (ref "CIN1") (pin "2") (pinfunction "2_2") (pintype "passive"))
      (node (ref "CIN2") (pin "2") (pinfunction "2_2") (pintype "passive"))
      (node (ref "CIN3") (pin "2") (pinfunction "2_2") (pintype "passive"))
      (node (ref "CIN4") (pin "2") (pinfunction "2_2") (pintype "passive"))
      (node (ref "CPU_PWR") (pin "P$1") (pinfunction "P$1_P$1") (pintype "bidirectional"))
      (node (ref "CPU_PWR") (pin "P$2") (pinfunction "P$2_P$2") (pintype "bidirectional"))
      (node (ref "DEPTH_SENS") (pin "P$3") (pinfunction "P$3_P$3") (pintype "bidirectional"))
      (node (ref "ETHERNET") (pin "P$2") (pinfunction "P$2_P$2") (pintype "bidirectional"))
      (node (ref "FAN1") (pin "P$2") (pinfunction "P$2_P$2") (pintype "bidirectional"))
      (node (ref "FAN2") (pin "P$2") (pinfunction "P$2_P$2") (pintype "bidirectional"))
      (node (ref "JP1") (pin "1") (pinfunction "1_1") (pintype "passive"))
      (node (ref "JP2") (pin "1") (pinfunction "1_1") (pintype "passive"))
      (node (ref "LED1") (pin "P$2") (pinfunction "C_P$2") (pintype "passive"))
      (node (ref "LED3") (pin "P$2") (pinfunction "C_P$2") (pintype "passive"))
      (node (ref "LED6") (pin "P$2") (pinfunction "C_P$2") (pintype "passive"))
      (node (ref "LED7") (pin "P$2") (pinfunction "C_P$2") (pintype "passive"))
      (node (ref "LED8") (pin "P$2") (pinfunction "C_P$2") (pintype "passive"))
      (node (ref "LED9") (pin "P$2") (pinfunction "C_P$2") (pintype "passive"))
      (node (ref "R13") (pin "1") (pinfunction "1_1") (pintype "passive"))
      (node (ref "R2") (pin "1") (pinfunction "E_1") (pintype "passive"))
      (node (ref "R20") (pin "1") (pinfunction "1_1") (pintype "passive"))
      (node (ref "R24") (pin "1") (pinfunction "1_1") (pintype "passive"))
      (node (ref "R3") (pin "1") (pinfunction "E_1") (pintype "passive"))
      (node (ref "R4") (pin "1") (pinfunction "1_1") (pintype "passive"))
      (node (ref "R5") (pin "P$2") (pinfunction "2_P$2") (pintype "passive"))
      (node (ref "R6") (pin "P$2") (pinfunction "2_P$2") (pintype "passive"))
      (node (ref "R9") (pin "1") (pinfunction "1_1") (pintype "passive"))
      (node (ref "SHORE_IN") (pin "P$2") (pinfunction "P$2_P$2") (pintype "bidirectional"))
      (node (ref "TEST-PTS") (pin "1") (pinfunction "1_1") (pintype "passive"))
      (node (ref "TEST-PTS1") (pin "1") (pinfunction "1_1") (pintype "passive"))
      (node (ref "THRUST1") (pin "P$1") (pinfunction "P$1_P$1") (pintype "bidirectional"))
      (node (ref "THRUST1") (pin "P$3") (pinfunction "P$3_P$3") (pintype "bidirectional"))
      (node (ref "THRUST2") (pin "P$1") (pinfunction "P$1_P$1") (pintype "bidirectional"))
      (node (ref "THRUST2") (pin "P$3") (pinfunction "P$3_P$3") (pintype "bidirectional"))
      (node (ref "THRUST3") (pin "P$1") (pinfunction "P$1_P$1") (pintype "bidirectional"))
      (node (ref "THRUST3") (pin "P$3") (pinfunction "P$3_P$3") (pintype "bidirectional"))
      (node (ref "THRUST4") (pin "P$1") (pinfunction "P$1_P$1") (pintype "bidirectional"))
      (node (ref "THRUST4") (pin "P$3") (pinfunction "P$3_P$3") (pintype "bidirectional"))
      (node (ref "THRUST5") (pin "P$1") (pinfunction "P$1_P$1") (pintype "bidirectional"))
      (node (ref "THRUST5") (pin "P$3") (pinfunction "P$3_P$3") (pintype "bidirectional"))
      (node (ref "THRUST6") (pin "P$1") (pinfunction "P$1_P$1") (pintype "bidirectional"))
      (node (ref "THRUST6") (pin "P$3") (pinfunction "P$3_P$3") (pintype "bidirectional"))
      (node (ref "THRUST7") (pin "P$1") (pinfunction "P$1_P$1") (pintype "bidirectional"))
      (node (ref "THRUST7") (pin "P$3") (pinfunction "P$3_P$3") (pintype "bidirectional"))
      (node (ref "THRUST8") (pin "P$1") (pinfunction "P$1_P$1") (pintype "bidirectional"))
      (node (ref "THRUST8") (pin "P$3") (pinfunction "P$3_P$3") (pintype "bidirectional"))
      (node (ref "THRUSTER_CURR_ADC") (pin "11") (pinfunction "COM_11") (pintype "bidirectional"))
      (node (ref "THRUSTER_CURR_ADC") (pin "12") (pinfunction "A0_12") (pintype "bidirectional"))
      (node (ref "THRUSTER_CURR_ADC") (pin "13") (pinfunction "A1_13") (pintype "bidirectional"))
      (node (ref "THRUSTER_CURR_ADC") (pin "9") (pinfunction "GND_9") (pintype "bidirectional"))
      (node (ref "U$1") (pin "P$1") (pinfunction "A_P$1") (pintype "passive"))
      (node (ref "U$10") (pin "3") (pinfunction "A_3") (pintype "passive"))
      (node (ref "U$11") (pin "P$5") (pinfunction "GND_P$5") (pintype "bidirectional"))
      (node (ref "U$13") (pin "3") (pinfunction "A_3") (pintype "passive"))
      (node (ref "U$14") (pin "P$5") (pinfunction "GND_P$5") (pintype "bidirectional"))
      (node (ref "U$16") (pin "3") (pinfunction "A_3") (pintype "passive"))
      (node (ref "U$17") (pin "P$5") (pinfunction "GND_P$5") (pintype "bidirectional"))
      (node (ref "U$19") (pin "P$5") (pinfunction "GND_P$5") (pintype "bidirectional"))
      (node (ref "U$2") (pin "P$5") (pinfunction "GND_P$5") (pintype "bidirectional"))
      (node (ref "U$22") (pin "3") (pinfunction "A_3") (pintype "passive"))
      (node (ref "U$23") (pin "P$5") (pinfunction "GND_P$5") (pintype "bidirectional"))
      (node (ref "U$24") (pin "1") (pinfunction "GND_1") (pintype "bidirectional"))
      (node (ref "U$25") (pin "P$1") (pinfunction "GND1_P$1") (pintype "bidirectional"))
      (node (ref "U$25") (pin "P$2") (pinfunction "GND2_P$2") (pintype "bidirectional"))
      (node (ref "U$26") (pin "3") (pinfunction "A_3") (pintype "passive"))
      (node (ref "U$28") (pin "3") (pinfunction "A_3") (pintype "passive"))
      (node (ref "U$29") (pin "P$5") (pinfunction "GND_P$5") (pintype "bidirectional"))
      (node (ref "U$30") (pin "3") (pinfunction "A_3") (pintype "passive"))
      (node (ref "U$31") (pin "3") (pinfunction "A_3") (pintype "passive"))
      (node (ref "U$32") (pin "3") (pinfunction "A_3") (pintype "passive"))
      (node (ref "U$33") (pin "3") (pinfunction "A_3") (pintype "passive"))
      (node (ref "U$34") (pin "3") (pinfunction "A_3") (pintype "passive"))
      (node (ref "U$35") (pin "P$5") (pinfunction "GND_P$5") (pintype "bidirectional"))
      (node (ref "U$38") (pin "3") (pinfunction "A_3") (pintype "passive"))
      (node (ref "U$39") (pin "P$5") (pinfunction "GND_P$5") (pintype "bidirectional"))
      (node (ref "U$4") (pin "P$5") (pinfunction "GND_P$5") (pintype "bidirectional"))
      (node (ref "U$41") (pin "P$1") (pinfunction "GND1_P$1") (pintype "bidirectional"))
      (node (ref "U$41") (pin "P$2") (pinfunction "GND2_P$2") (pintype "bidirectional"))
      (node (ref "U$42") (pin "3") (pinfunction "A_3") (pintype "passive"))
      (node (ref "U$43") (pin "3") (pinfunction "A_3") (pintype "passive"))
      (node (ref "U$44") (pin "3") (pinfunction "A_3") (pintype "passive"))
      (node (ref "U$45") (pin "P$1") (pinfunction "A_P$1") (pintype "passive"))
      (node (ref "U$46") (pin "3") (pinfunction "A_3") (pintype "passive"))
      (node (ref "U$47") (pin "3") (pinfunction "A_3") (pintype "passive"))
      (node (ref "U$48") (pin "GND") (pinfunction "GND_GND") (pintype "bidirectional"))
      (node (ref "U$48") (pin "OV") (pinfunction "OV_OV") (pintype "bidirectional"))
      (node (ref "U$51") (pin "GND") (pinfunction "GND_GND") (pintype "bidirectional"))
      (node (ref "U$51") (pin "OV") (pinfunction "OV_OV") (pintype "bidirectional"))
      (node (ref "U$55") (pin "2") (pinfunction "S_2") (pintype "passive"))
      (node (ref "U$56") (pin "P$3") (pinfunction "GND_P$3") (pintype "bidirectional"))
      (node (ref "U$57") (pin "P$1") (pinfunction "GND_P$1") (pintype "bidirectional"))
      (node (ref "U$58") (pin "2") (pinfunction "S_2") (pintype "passive"))
      (node (ref "U$60") (pin "P$3") (pinfunction "A_P$3") (pintype "passive"))
      (node (ref "U$61") (pin "P$3") (pinfunction "A_P$3") (pintype "passive"))
      (node (ref "U$62") (pin "3") (pinfunction "A_3") (pintype "passive"))
      (node (ref "U$63") (pin "P$1") (pinfunction "A_P$1") (pintype "passive"))
      (node (ref "U$64") (pin "P$1") (pinfunction "A_P$1") (pintype "passive"))
      (node (ref "U$66") (pin "P$1") (pinfunction "A_P$1") (pintype "passive"))
      (node (ref "U$67") (pin "3") (pinfunction "A_3") (pintype "passive"))
      (node (ref "U$68") (pin "3") (pinfunction "A_3") (pintype "passive"))
      (node (ref "U$7") (pin "5A") (pinfunction "5_5A") (pintype "bidirectional"))
      (node (ref "U$7") (pin "5B") (pinfunction "5_5B") (pintype "bidirectional"))
      (node (ref "U$7") (pin "BA") (pinfunction "B_BA") (pintype "bidirectional"))
      (node (ref "U$7") (pin "BB") (pinfunction "B_BB") (pintype "bidirectional"))
      (node (ref "U$8") (pin "P$5") (pinfunction "GND_P$5") (pintype "bidirectional"))
      (node (ref "U1") (pin "14") (pinfunction "VSS_14") (pintype "bidirectional"))
      (node (ref "U1") (pin "23") (pinfunction "~{OE}_23") (pintype "bidirectional"))
      (node (ref "U1") (pin "25") (pinfunction "EXTCLK_25") (pintype "bidirectional"))
      (node (ref "V-THRUST_CURR_ADC") (pin "P$7") (pinfunction "GND_P$7") (pintype "bidirectional"))
      (node (ref "V-THRUST_LED") (pin "P$2") (pinfunction "C_P$2") (pintype "passive"))
      (node (ref "V-THRUST_OUT") (pin "P$2") (pinfunction "P$2_P$2") (pintype "bidirectional"))
      (node (ref "V-THRUST_VOLTAGE") (pin "P$3") (pinfunction "GND_P$3") (pintype "bidirectional"))
    )
    (net (code "21") (name "Net-(3V3_LED-A)") (class "Default")
      (node (ref "3V3_LED") (pin "P$1") (pinfunction "A_P$1") (pintype "passive"))
      (node (ref "R34") (pin "1") (pinfunction "1_1") (pintype "passive"))
    )
    (net (code "22") (name "Net-(5V_CURR_ADC-VIN)") (class "Default")
      (node (ref "5V_CURR_ADC") (pin "P$4") (pinfunction "VIN_P$4") (pintype "bidirectional"))
      (node (ref "U$2") (pin "P$7") (pinfunction "VIOUT_P$7") (pintype "bidirectional"))
    )
    (net (code "23") (name "Net-(5V_LED-A)") (class "Default")
      (node (ref "5V_LED") (pin "P$1") (pinfunction "A_P$1") (pintype "passive"))
      (node (ref "R31") (pin "1") (pinfunction "1_1") (pintype "passive"))
    )
    (net (code "24") (name "Net-(5V_VOLTAGE-IN+)") (class "Default")
      (node (ref "5V_VOLTAGE") (pin "P$1") (pinfunction "IN+_P$1") (pintype "bidirectional"))
      (node (ref "5V_VOLTAGE") (pin "P$2") (pinfunction "IN-_P$2") (pintype "bidirectional"))
      (node (ref "R35") (pin "2") (pinfunction "2_2") (pintype "passive"))
    )
    (net (code "25") (name "Net-(12V_CURR_ADC-VIN)") (class "Default")
      (node (ref "12V_CURR_ADC") (pin "P$4") (pinfunction "VIN_P$4") (pintype "bidirectional"))
      (node (ref "U$35") (pin "P$7") (pinfunction "VIOUT_P$7") (pintype "bidirectional"))
    )
    (net (code "26") (name "Net-(12V_LED-A)") (class "Default")
      (node (ref "12V_LED") (pin "P$1") (pinfunction "A_P$1") (pintype "passive"))
      (node (ref "R33") (pin "1") (pinfunction "1_1") (pintype "passive"))
    )
    (net (code "27") (name "Net-(12V_VOLTAGE-IN+)") (class "Default")
      (node (ref "12V_VOLTAGE") (pin "P$1") (pinfunction "IN+_P$1") (pintype "bidirectional"))
      (node (ref "12V_VOLTAGE") (pin "P$2") (pinfunction "IN-_P$2") (pintype "bidirectional"))
      (node (ref "R25") (pin "2") (pinfunction "2_2") (pintype "passive"))
    )
    (net (code "28") (name "Net-(AUDIO-PadP$1)") (class "Default")
      (node (ref "AUDIO") (pin "P$1") (pinfunction "P$1_P$1") (pintype "bidirectional"))
      (node (ref "R37") (pin "2") (pinfunction "2_2") (pintype "passive"))
      (node (ref "R39") (pin "1") (pinfunction "1_1") (pintype "passive"))
    )
    (net (code "29") (name "Net-(AUDIO1-PadP$1)") (class "Default")
      (node (ref "AUDIO1") (pin "P$1") (pinfunction "P$1_P$1") (pintype "bidirectional"))
      (node (ref "R42") (pin "2") (pinfunction "2_2") (pintype "passive"))
      (node (ref "R43") (pin "1") (pinfunction "1_1") (pintype "passive"))
    )
    (net (code "30") (name "Net-(C4-Pad1)") (class "Default")
      (node (ref "C4") (pin "1") (pinfunction "1_1") (pintype "passive"))
      (node (ref "U$48") (pin "TMR") (pinfunction "TMR_TMR") (pintype "bidirectional"))
    )
    (net (code "31") (name "Net-(C27-Pad1)") (class "Default")
      (node (ref "C27") (pin "1") (pinfunction "1_1") (pintype "passive"))
      (node (ref "U$51") (pin "TMR") (pinfunction "TMR_TMR") (pintype "bidirectional"))
    )
    (net (code "32") (name "Net-(LED1-A)") (class "Default")
      (node (ref "LED1") (pin "P$1") (pinfunction "A_P$1") (pintype "passive"))
      (node (ref "R37") (pin "1") (pinfunction "1_1") (pintype "passive"))
    )
    (net (code "33") (name "Net-(LED3-A)") (class "Default")
      (node (ref "LED3") (pin "P$1") (pinfunction "A_P$1") (pintype "passive"))
      (node (ref "R42") (pin "1") (pinfunction "1_1") (pintype "passive"))
    )
    (net (code "34") (name "Net-(LED4-PadC)") (class "Default")
      (node (ref "LED4") (pin "C") (pinfunction "C_C") (pintype "passive"))
      (node (ref "R44") (pin "2") (pinfunction "2_2") (pintype "passive"))
    )
    (net (code "35") (name "Net-(LED5-C)") (class "Default")
      (node (ref "LED5") (pin "P$2") (pinfunction "C_P$2") (pintype "passive"))
      (node (ref "R46") (pin "2") (pinfunction "2_2") (pintype "passive"))
    )
    (net (code "36") (name "Net-(LED6-A)") (class "Default")
      (node (ref "LED6") (pin "P$1") (pinfunction "A_P$1") (pintype "passive"))
      (node (ref "R48") (pin "1") (pinfunction "1_1") (pintype "passive"))
      (node (ref "U$60") (pin "P$1") (pinfunction "C_P$1") (pintype "passive"))
    )
    (net (code "37") (name "Net-(LED7-A)") (class "Default")
      (node (ref "LED7") (pin "P$1") (pinfunction "A_P$1") (pintype "passive"))
      (node (ref "R49") (pin "1") (pinfunction "1_1") (pintype "passive"))
      (node (ref "U$61") (pin "P$1") (pinfunction "C_P$1") (pintype "passive"))
    )
    (net (code "38") (name "Net-(LED8-A)") (class "Default")
      (node (ref "LED8") (pin "P$1") (pinfunction "A_P$1") (pintype "passive"))
      (node (ref "R50") (pin "1") (pinfunction "1_1") (pintype "passive"))
    )
    (net (code "39") (name "Net-(LED9-A)") (class "Default")
      (node (ref "LED9") (pin "P$1") (pinfunction "A_P$1") (pintype "passive"))
      (node (ref "R51") (pin "1") (pinfunction "1_1") (pintype "passive"))
    )
    (net (code "40") (name "Net-(PMOS1-D)") (class "Default")
      (node (ref "PMOS1") (pin "P$2") (pinfunction "D_P$2") (pintype "bidirectional"))
      (node (ref "R39") (pin "2") (pinfunction "2_2") (pintype "passive"))
    )
    (net (code "41") (name "Net-(PMOS1-G)") (class "Default")
      (node (ref "PMOS1") (pin "P$1") (pinfunction "G_P$1") (pintype "bidirectional"))
      (node (ref "R36") (pin "1") (pinfunction "1_1") (pintype "passive"))
      (node (ref "U$51") (pin "FLT") (pinfunction "~{FAULT}_FLT") (pintype "bidirectional"))
    )
    (net (code "42") (name "Net-(PMOS2-D)") (class "Default")
      (node (ref "PMOS2") (pin "P$2") (pinfunction "D_P$2") (pintype "bidirectional"))
      (node (ref "R43") (pin "2") (pinfunction "2_2") (pintype "passive"))
    )
    (net (code "43") (name "Net-(PMOS2-G)") (class "Default")
      (node (ref "PMOS2") (pin "P$1") (pinfunction "G_P$1") (pintype "bidirectional"))
      (node (ref "R41") (pin "1") (pinfunction "1_1") (pintype "passive"))
      (node (ref "U$48") (pin "FLT") (pinfunction "~{FAULT}_FLT") (pintype "bidirectional"))
    )
    (net (code "44") (name "Net-(R2-S)") (class "Default")
      (node (ref "R2") (pin "2") (pinfunction "S_2") (pintype "passive"))
      (node (ref "TEST-PTS") (pin "2") (pinfunction "2_2") (pintype "passive"))
      (node (ref "U$60") (pin "P$2") (pinfunction "REF_P$2") (pintype "bidirectional"))
    )
    (net (code "45") (name "Net-(R3-S)") (class "Default")
      (node (ref "R3") (pin "2") (pinfunction "S_2") (pintype "passive"))
      (node (ref "TEST-PTS1") (pin "2") (pinfunction "2_2") (pintype "passive"))
      (node (ref "U$61") (pin "P$2") (pinfunction "REF_P$2") (pintype "bidirectional"))
    )
    (net (code "46") (name "Net-(R5-1)") (class "Default")
      (node (ref "R5") (pin "P$1") (pinfunction "1_P$1") (pintype "passive"))
      (node (ref "U$25") (pin "P$6") (pinfunction "VOADJUST_P$6") (pintype "bidirectional"))
    )
    (net (code "47") (name "Net-(R6-1)") (class "Default")
      (node (ref "R6") (pin "P$1") (pinfunction "1_P$1") (pintype "passive"))
      (node (ref "U$41") (pin "P$6") (pinfunction "VOADJUST_P$6") (pintype "bidirectional"))
    )
    (net (code "48") (name "Net-(R13-Pad2)") (class "Default")
      (node (ref "R13") (pin "2") (pinfunction "2_2") (pintype "passive"))
      (node (ref "R17") (pin "1") (pinfunction "1_1") (pintype "passive"))
      (node (ref "U$51") (pin "UV") (pinfunction "UV_UV") (pintype "bidirectional"))
    )
    (net (code "49") (name "Net-(R14-Pad1)") (class "Default")
      (node (ref "R14") (pin "1") (pinfunction "1_1") (pintype "passive"))
      (node (ref "R20") (pin "2") (pinfunction "2_2") (pintype "passive"))
      (node (ref "U$51") (pin "FB") (pinfunction "FB_FB") (pintype "bidirectional"))
    )
    (net (code "50") (name "Net-(R14-Pad2)") (class "Default")
      (node (ref "R14") (pin "2") (pinfunction "2_2") (pintype "passive"))
      (node (ref "R19") (pin "1") (pinfunction "1_1") (pintype "passive"))
    )
    (net (code "51") (name "Net-(R16-Pad1)") (class "Default")
      (node (ref "R16") (pin "1") (pinfunction "1_1") (pintype "passive"))
      (node (ref "U$51") (pin "HGATE") (pinfunction "HGATE_HGATE") (pintype "bidirectional"))
    )
    (net (code "52") (name "Net-(R23-Pad1)") (class "Default")
      (node (ref "R23") (pin "1") (pinfunction "1_1") (pintype "passive"))
      (node (ref "R24") (pin "2") (pinfunction "2_2") (pintype "passive"))
      (node (ref "U$48") (pin "FB") (pinfunction "FB_FB") (pintype "bidirectional"))
    )
    (net (code "53") (name "Net-(R23-Pad2)") (class "Default")
      (node (ref "R23") (pin "2") (pinfunction "2_2") (pintype "passive"))
      (node (ref "R28") (pin "1") (pinfunction "1_1") (pintype "passive"))
    )
    (net (code "54") (name "Net-(R26-Pad1)") (class "Default")
      (node (ref "R26") (pin "1") (pinfunction "1_1") (pintype "passive"))
      (node (ref "U$48") (pin "HGATE") (pinfunction "HGATE_HGATE") (pintype "bidirectional"))
    )
    (net (code "55") (name "Net-(R27-Pad1)") (class "Default")
      (node (ref "R27") (pin "1") (pinfunction "1_1") (pintype "passive"))
      (node (ref "R9") (pin "2") (pinfunction "2_2") (pintype "passive"))
      (node (ref "U$48") (pin "UV") (pinfunction "UV_UV") (pintype "bidirectional"))
    )
    (net (code "56") (name "Net-(U$2-FILTER)") (class "Default")
      (node (ref "C3") (pin "1") (pinfunction "1_1") (pintype "passive"))
      (node (ref "U$2") (pin "P$6") (pinfunction "FILTER_P$6") (pintype "bidirectional"))
    )
    (net (code "57") (name "Net-(U$2-IP--PadP$3)") (class "Default")
      (node (ref "U$2") (pin "P$3") (pinfunction "IP-_P$3") (pintype "bidirectional"))
      (node (ref "U$2") (pin "P$4") (pinfunction "IP-_P$4") (pintype "bidirectional"))
      (node (ref "U$20") (pin "P$1") (pinfunction "P$1_P$1") (pintype "bidirectional"))
    )
    (net (code "58") (name "Net-(U$4-FILTER)") (class "Default")
      (node (ref "C6") (pin "1") (pinfunction "1_1") (pintype "passive"))
      (node (ref "U$4") (pin "P$6") (pinfunction "FILTER_P$6") (pintype "bidirectional"))
    )
    (net (code "59") (name "Net-(U$4-IP--PadP$3)") (class "Default")
      (node (ref "U$4") (pin "P$3") (pinfunction "IP-_P$3") (pintype "bidirectional"))
      (node (ref "U$4") (pin "P$4") (pinfunction "IP-_P$4") (pintype "bidirectional"))
      (node (ref "U$6") (pin "P$1") (pinfunction "P$1_P$1") (pintype "bidirectional"))
    )
    (net (code "60") (name "Net-(U$8-FILTER)") (class "Default")
      (node (ref "C9") (pin "1") (pinfunction "1_1") (pintype "passive"))
      (node (ref "U$8") (pin "P$6") (pinfunction "FILTER_P$6") (pintype "bidirectional"))
    )
    (net (code "61") (name "Net-(U$8-IP--PadP$3)") (class "Default")
      (node (ref "U$8") (pin "P$3") (pinfunction "IP-_P$3") (pintype "bidirectional"))
      (node (ref "U$8") (pin "P$4") (pinfunction "IP-_P$4") (pintype "bidirectional"))
      (node (ref "U$9") (pin "P$1") (pinfunction "P$1_P$1") (pintype "bidirectional"))
    )
    (net (code "62") (name "Net-(U$11-FILTER)") (class "Default")
      (node (ref "C12") (pin "1") (pinfunction "1_1") (pintype "passive"))
      (node (ref "U$11") (pin "P$6") (pinfunction "FILTER_P$6") (pintype "bidirectional"))
    )
    (net (code "63") (name "Net-(U$11-IP--PadP$3)") (class "Default")
      (node (ref "U$11") (pin "P$3") (pinfunction "IP-_P$3") (pintype "bidirectional"))
      (node (ref "U$11") (pin "P$4") (pinfunction "IP-_P$4") (pintype "bidirectional"))
      (node (ref "U$12") (pin "P$1") (pinfunction "P$1_P$1") (pintype "bidirectional"))
    )
    (net (code "64") (name "Net-(U$14-FILTER)") (class "Default")
      (node (ref "C15") (pin "1") (pinfunction "1_1") (pintype "passive"))
      (node (ref "U$14") (pin "P$6") (pinfunction "FILTER_P$6") (pintype "bidirectional"))
    )
    (net (code "65") (name "Net-(U$14-IP--PadP$3)") (class "Default")
      (node (ref "U$14") (pin "P$3") (pinfunction "IP-_P$3") (pintype "bidirectional"))
      (node (ref "U$14") (pin "P$4") (pinfunction "IP-_P$4") (pintype "bidirectional"))
      (node (ref "U$15") (pin "P$1") (pinfunction "P$1_P$1") (pintype "bidirectional"))
    )
    (net (code "66") (name "Net-(U$17-FILTER)") (class "Default")
      (node (ref "C18") (pin "1") (pinfunction "1_1") (pintype "passive"))
      (node (ref "U$17") (pin "P$6") (pinfunction "FILTER_P$6") (pintype "bidirectional"))
    )
    (net (code "67") (name "Net-(U$17-IP--PadP$3)") (class "Default")
      (node (ref "U$17") (pin "P$3") (pinfunction "IP-_P$3") (pintype "bidirectional"))
      (node (ref "U$17") (pin "P$4") (pinfunction "IP-_P$4") (pintype "bidirectional"))
      (node (ref "U$18") (pin "P$1") (pinfunction "P$1_P$1") (pintype "bidirectional"))
    )
    (net (code "68") (name "Net-(U$19-FILTER)") (class "Default")
      (node (ref "C20") (pin "1") (pinfunction "1_1") (pintype "passive"))
      (node (ref "U$19") (pin "P$6") (pinfunction "FILTER_P$6") (pintype "bidirectional"))
    )
    (net (code "69") (name "Net-(U$19-IP--PadP$3)") (class "Default")
      (node (ref "U$19") (pin "P$3") (pinfunction "IP-_P$3") (pintype "bidirectional"))
      (node (ref "U$19") (pin "P$4") (pinfunction "IP-_P$4") (pintype "bidirectional"))
      (node (ref "U$5") (pin "P$1") (pinfunction "P$1_P$1") (pintype "bidirectional"))
      (node (ref "U$5") (pin "P$2") (pinfunction "P$1_P$2") (pintype "bidirectional"))
    )
    (net (code "70") (name "Net-(U$19-VIOUT)") (class "Default")
      (node (ref "U$19") (pin "P$7") (pinfunction "VIOUT_P$7") (pintype "bidirectional"))
      (node (ref "V-THRUST_CURR_ADC") (pin "P$4") (pinfunction "VIN_P$4") (pintype "bidirectional"))
    )
    (net (code "71") (name "Net-(U$21-A)") (class "Default")
      (node (ref "2PIN_1") (pin "P$2") (pinfunction "P$2_P$2") (pintype "bidirectional"))
      (node (ref "C23") (pin "1") (pinfunction "1_1") (pintype "passive"))
      (node (ref "R4") (pin "2") (pinfunction "2_2") (pintype "passive"))
      (node (ref "U$21") (pin "3") (pinfunction "A_3") (pintype "passive"))
      (node (ref "U$24") (pin "2") (pinfunction "IN_2") (pintype "bidirectional"))
    )
    (net (code "72") (name "Net-(U$23-FILTER)") (class "Default")
      (node (ref "C29") (pin "1") (pinfunction "1_1") (pintype "passive"))
      (node (ref "U$23") (pin "P$6") (pinfunction "FILTER_P$6") (pintype "bidirectional"))
    )
    (net (code "73") (name "Net-(U$23-IP--PadP$3)") (class "Default")
      (node (ref "U$23") (pin "P$3") (pinfunction "IP-_P$3") (pintype "bidirectional"))
      (node (ref "U$23") (pin "P$4") (pinfunction "IP-_P$4") (pintype "bidirectional"))
      (node (ref "U$27") (pin "P$1") (pinfunction "P$1_P$1") (pintype "bidirectional"))
    )
    (net (code "74") (name "Net-(U$25-~{INHIBIT})") (class "Default")
      (node (ref "JP1") (pin "2") (pinfunction "2_2") (pintype "passive"))
      (node (ref "U$25") (pin "P$3") (pinfunction "~{INHIBIT}_P$3") (pintype "bidirectional"))
    )
    (net (code "75") (name "Net-(U$29-FILTER)") (class "Default")
      (node (ref "C37") (pin "1") (pinfunction "1_1") (pintype "passive"))
      (node (ref "U$29") (pin "P$6") (pinfunction "FILTER_P$6") (pintype "bidirectional"))
    )
    (net (code "76") (name "Net-(U$29-IP--PadP$3)") (class "Default")
      (node (ref "U$29") (pin "P$3") (pinfunction "IP-_P$3") (pintype "bidirectional"))
      (node (ref "U$29") (pin "P$4") (pinfunction "IP-_P$4") (pintype "bidirectional"))
      (node (ref "U$37") (pin "P$1") (pinfunction "P$1_P$1") (pintype "bidirectional"))
    )
    (net (code "77") (name "Net-(U$35-FILTER)") (class "Default")
      (node (ref "C31") (pin "1") (pinfunction "1_1") (pintype "passive"))
      (node (ref "U$35") (pin "P$6") (pinfunction "FILTER_P$6") (pintype "bidirectional"))
    )
    (net (code "78") (name "Net-(U$35-IP--PadP$3)") (class "Default")
      (node (ref "U$35") (pin "P$3") (pinfunction "IP-_P$3") (pintype "bidirectional"))
      (node (ref "U$35") (pin "P$4") (pinfunction "IP-_P$4") (pintype "bidirectional"))
      (node (ref "U$36") (pin "P$1") (pinfunction "P$1_P$1") (pintype "bidirectional"))
    )
    (net (code "79") (name "Net-(U$39-FILTER)") (class "Default")
      (node (ref "C57") (pin "1") (pinfunction "1_1") (pintype "passive"))
      (node (ref "U$39") (pin "P$6") (pinfunction "FILTER_P$6") (pintype "bidirectional"))
    )
    (net (code "80") (name "Net-(U$39-IP--PadP$3)") (class "Default")
      (node (ref "U$39") (pin "P$3") (pinfunction "IP-_P$3") (pintype "bidirectional"))
      (node (ref "U$39") (pin "P$4") (pinfunction "IP-_P$4") (pintype "bidirectional"))
      (node (ref "U$40") (pin "P$1") (pinfunction "P$1_P$1") (pintype "bidirectional"))
    )
    (net (code "81") (name "Net-(U$41-~{INHIBIT})") (class "Default")
      (node (ref "JP2") (pin "2") (pinfunction "2_2") (pintype "passive"))
      (node (ref "U$41") (pin "P$3") (pinfunction "~{INHIBIT}_P$3") (pintype "bidirectional"))
    )
    (net (code "82") (name "Net-(U$45-C)") (class "Default")
      (node (ref "C30") (pin "1") (pinfunction "1_1") (pintype "passive"))
      (node (ref "JP4") (pin "2") (pinfunction "2_2") (pintype "passive"))
      (node (ref "U$24") (pin "6") (pinfunction "OUT_6") (pintype "bidirectional"))
      (node (ref "U$24") (pin "7") (pinfunction "OUT_7") (pintype "bidirectional"))
      (node (ref "U$24") (pin "8") (pinfunction "OUT_8") (pintype "bidirectional"))
      (node (ref "U$45") (pin "P$2") (pinfunction "C_P$2") (pintype "passive"))
      (node (ref "U$7") (pin "AA") (pinfunction "A_AA") (pintype "bidirectional"))
      (node (ref "U$7") (pin "AB") (pinfunction "A_AB") (pintype "bidirectional"))
    )
    (net (code "83") (name "Net-(U$48-~{SHDN})") (class "Default")
      (node (ref "JP3") (pin "2") (pinfunction "2_2") (pintype "passive"))
      (node (ref "U$48") (pin "SHDN") (pinfunction "~{SHDN}_SHDN") (pintype "bidirectional"))
      (node (ref "U$51") (pin "SHDN") (pinfunction "~{SHDN}_SHDN") (pintype "bidirectional"))
      (node (ref "U$56") (pin "P$4") (pinfunction "OUT_P$4") (pintype "bidirectional"))
    )
    (net (code "84") (name "Net-(U$49-G)") (class "Default")
      (node (ref "R26") (pin "2") (pinfunction "2_2") (pintype "passive"))
      (node (ref "U$49") (pin "1") (pinfunction "G_1") (pintype "bidirectional"))
    )
    (net (code "85") (name "Net-(U$49-S)") (class "Default")
      (node (ref "U$48") (pin "SOURCE") (pinfunction "SOURCE_SOURCE") (pintype "bidirectional"))
      (node (ref "U$49") (pin "3") (pinfunction "S_3") (pintype "bidirectional"))
      (node (ref "U$50") (pin "3") (pinfunction "S_3") (pintype "bidirectional"))
    )
    (net (code "86") (name "Net-(U$50-D)") (class "Default")
      (node (ref "R12") (pin "1") (pinfunction "1_1") (pintype "passive"))
      (node (ref "U$48") (pin "SENSE") (pinfunction "SENSE_SENSE") (pintype "bidirectional"))
      (node (ref "U$50") (pin "TAB") (pinfunction "D_TAB") (pintype "bidirectional"))
    )
    (net (code "87") (name "Net-(U$50-G)") (class "Default")
      (node (ref "U$48") (pin "DGATE") (pinfunction "DGATE_DGATE") (pintype "bidirectional"))
      (node (ref "U$50") (pin "1") (pinfunction "G_1") (pintype "bidirectional"))
    )
    (net (code "88") (name "Net-(U$52-G)") (class "Default")
      (node (ref "R16") (pin "2") (pinfunction "2_2") (pintype "passive"))
      (node (ref "U$52") (pin "1") (pinfunction "G_1") (pintype "bidirectional"))
    )
    (net (code "89") (name "Net-(U$52-S)") (class "Default")
      (node (ref "U$51") (pin "SOURCE") (pinfunction "SOURCE_SOURCE") (pintype "bidirectional"))
      (node (ref "U$52") (pin "3") (pinfunction "S_3") (pintype "bidirectional"))
      (node (ref "U$53") (pin "3") (pinfunction "S_3") (pintype "bidirectional"))
    )
    (net (code "90") (name "Net-(U$53-D)") (class "Default")
      (node (ref "R15") (pin "1") (pinfunction "1_1") (pintype "passive"))
      (node (ref "U$51") (pin "SENSE") (pinfunction "SENSE_SENSE") (pintype "bidirectional"))
      (node (ref "U$53") (pin "TAB") (pinfunction "D_TAB") (pintype "bidirectional"))
    )
    (net (code "91") (name "Net-(U$53-G)") (class "Default")
      (node (ref "U$51") (pin "DGATE") (pinfunction "DGATE_DGATE") (pintype "bidirectional"))
      (node (ref "U$53") (pin "1") (pinfunction "G_1") (pintype "bidirectional"))
    )
    (net (code "92") (name "Net-(U$55-D)") (class "Default")
      (node (ref "R44") (pin "1") (pinfunction "1_1") (pintype "passive"))
      (node (ref "U$55") (pin "3") (pinfunction "D_3") (pintype "bidirectional"))
    )
    (net (code "93") (name "Net-(U$55-G)") (class "Default")
      (node (ref "R45") (pin "1") (pinfunction "1_1") (pintype "passive"))
      (node (ref "U$48") (pin "ENOUT") (pinfunction "ENOUT_ENOUT") (pintype "bidirectional"))
      (node (ref "U$55") (pin "1") (pinfunction "G_1") (pintype "passive"))
    )
    (net (code "94") (name "Net-(U$56-IN)") (class "Default")
      (node (ref "C60") (pin "1") (pinfunction "1_1") (pintype "passive"))
      (node (ref "R22") (pin "2") (pinfunction "2_2") (pintype "passive"))
      (node (ref "U$56") (pin "P$2") (pinfunction "IN_P$2") (pintype "bidirectional"))
    )
    (net (code "95") (name "Net-(U$58-D)") (class "Default")
      (node (ref "R46") (pin "1") (pinfunction "1_1") (pintype "passive"))
      (node (ref "U$58") (pin "3") (pinfunction "D_3") (pintype "bidirectional"))
    )
    (net (code "96") (name "Net-(U$58-G)") (class "Default")
      (node (ref "R47") (pin "1") (pinfunction "1_1") (pintype "passive"))
      (node (ref "U$51") (pin "ENOUT") (pinfunction "ENOUT_ENOUT") (pintype "bidirectional"))
      (node (ref "U$58") (pin "1") (pinfunction "G_1") (pintype "passive"))
    )
    (net (code "97") (name "Net-(V-THRUST_LED-A)") (class "Default")
      (node (ref "R32") (pin "1") (pinfunction "1_1") (pintype "passive"))
      (node (ref "V-THRUST_LED") (pin "P$1") (pinfunction "A_P$1") (pintype "passive"))
    )
    (net (code "98") (name "Net-(V-THRUST_VOLTAGE-IN+)") (class "Default")
      (node (ref "R30") (pin "2") (pinfunction "2_2") (pintype "passive"))
      (node (ref "V-THRUST_VOLTAGE") (pin "P$1") (pinfunction "IN+_P$1") (pintype "bidirectional"))
      (node (ref "V-THRUST_VOLTAGE") (pin "P$2") (pinfunction "IN-_P$2") (pintype "bidirectional"))
    )
    (net (code "99") (name "SCL") (class "Default")
      (node (ref "12V_CURR_ADC") (pin "P$1") (pinfunction "SCL_P$1") (pintype "bidirectional"))
      (node (ref "12V_VOLTAGE") (pin "P$5") (pinfunction "SCL_P$5") (pintype "bidirectional"))
      (node (ref "5V_CURR_ADC") (pin "P$1") (pinfunction "SCL_P$1") (pintype "bidirectional"))
      (node (ref "5V_VOLTAGE") (pin "P$5") (pinfunction "SCL_P$5") (pintype "bidirectional"))
      (node (ref "JP5") (pin "2") (pinfunction "2_2") (pintype "passive"))
      (node (ref "R8") (pin "1") (pinfunction "1_1") (pintype "passive"))
      (node (ref "THRUSTER_CURR_ADC") (pin "14") (pinfunction "SCL_14") (pintype "bidirectional"))
      (node (ref "U$71") (pin "P$1") (pinfunction "1_P$1") (pintype "bidirectional"))
      (node (ref "U1") (pin "26") (pinfunction "SCL_26") (pintype "bidirectional"))
      (node (ref "V-THRUST_CURR_ADC") (pin "P$1") (pinfunction "SCL_P$1") (pintype "bidirectional"))
      (node (ref "V-THRUST_VOLTAGE") (pin "P$5") (pinfunction "SCL_P$5") (pintype "bidirectional"))
    )
    (net (code "100") (name "SCL-3V3") (class "Default")
      (node (ref "BME280") (pin "P$4") (pinfunction "SCK/SCL_P$4") (pintype "bidirectional"))
      (node (ref "DEPTH_SENS") (pin "P$1") (pinfunction "P$1_P$1") (pintype "bidirectional"))
      (node (ref "JP6") (pin "2") (pinfunction "2_2") (pintype "passive"))
      (node (ref "R11") (pin "1") (pinfunction "1_1") (pintype "passive"))
    )
    (net (code "101") (name "SDA") (class "Default")
      (node (ref "12V_CURR_ADC") (pin "P$8") (pinfunction "SDA_P$8") (pintype "bidirectional"))
      (node (ref "12V_VOLTAGE") (pin "P$6") (pinfunction "SDA_P$6") (pintype "bidirectional"))
      (node (ref "5V_CURR_ADC") (pin "P$8") (pinfunction "SDA_P$8") (pintype "bidirectional"))
      (node (ref "5V_VOLTAGE") (pin "P$6") (pinfunction "SDA_P$6") (pintype "bidirectional"))
      (node (ref "JP5") (pin "1") (pinfunction "1_1") (pintype "passive"))
      (node (ref "R7") (pin "1") (pinfunction "1_1") (pintype "passive"))
      (node (ref "THRUSTER_CURR_ADC") (pin "15") (pinfunction "SDA_15") (pintype "bidirectional"))
      (node (ref "U$72") (pin "P$1") (pinfunction "1_P$1") (pintype "bidirectional"))
      (node (ref "U1") (pin "27") (pinfunction "SDA_27") (pintype "bidirectional"))
      (node (ref "V-THRUST_CURR_ADC") (pin "P$8") (pinfunction "SDA_P$8") (pintype "bidirectional"))
      (node (ref "V-THRUST_VOLTAGE") (pin "P$6") (pinfunction "SDA_P$6") (pintype "bidirectional"))
    )
    (net (code "102") (name "SDA-3V3") (class "Default")
      (node (ref "BME280") (pin "P$3") (pinfunction "SDI/SDA_P$3") (pintype "bidirectional"))
      (node (ref "DEPTH_SENS") (pin "P$2") (pinfunction "P$2_P$2") (pintype "bidirectional"))
      (node (ref "JP6") (pin "1") (pinfunction "1_1") (pintype "passive"))
      (node (ref "R10") (pin "1") (pinfunction "1_1") (pintype "passive"))
    )
    (net (code "103") (name "T1_CURR") (class "Default")
      (node (ref "THRUSTER_CURR_ADC") (pin "1") (pinfunction "CH0_1") (pintype "bidirectional"))
      (node (ref "U$4") (pin "P$7") (pinfunction "VIOUT_P$7") (pintype "bidirectional"))
    )
    (net (code "104") (name "T3_CURR") (class "Default")
      (node (ref "THRUSTER_CURR_ADC") (pin "3") (pinfunction "CH2_3") (pintype "bidirectional"))
      (node (ref "U$11") (pin "P$7") (pinfunction "VIOUT_P$7") (pintype "bidirectional"))
    )
    (net (code "105") (name "T4_CURR") (class "Default")
      (node (ref "THRUSTER_CURR_ADC") (pin "4") (pinfunction "CH3_4") (pintype "bidirectional"))
      (node (ref "U$14") (pin "P$7") (pinfunction "VIOUT_P$7") (pintype "bidirectional"))
    )
    (net (code "106") (name "T5_CURR") (class "Default")
      (node (ref "THRUSTER_CURR_ADC") (pin "5") (pinfunction "CH4_5") (pintype "bidirectional"))
      (node (ref "U$17") (pin "P$7") (pinfunction "VIOUT_P$7") (pintype "bidirectional"))
    )
    (net (code "107") (name "T6_CURR") (class "Default")
      (node (ref "THRUSTER_CURR_ADC") (pin "6") (pinfunction "CH5_6") (pintype "bidirectional"))
      (node (ref "U$23") (pin "P$7") (pinfunction "VIOUT_P$7") (pintype "bidirectional"))
    )
    (net (code "108") (name "T7_CURR") (class "Default")
      (node (ref "THRUSTER_CURR_ADC") (pin "7") (pinfunction "CH6_7") (pintype "bidirectional"))
      (node (ref "U$29") (pin "P$7") (pinfunction "VIOUT_P$7") (pintype "bidirectional"))
    )
    (net (code "109") (name "T8_CURR") (class "Default")
      (node (ref "THRUSTER_CURR_ADC") (pin "8") (pinfunction "CH7_8") (pintype "bidirectional"))
      (node (ref "U$39") (pin "P$7") (pinfunction "VIOUT_P$7") (pintype "bidirectional"))
    )
    (net (code "110") (name "VIN") (class "Default")
      (node (ref "C28") (pin "1") (pinfunction "1_1") (pintype "passive"))
      (node (ref "C65") (pin "1") (pinfunction "1_1") (pintype "passive"))
      (node (ref "CIN1") (pin "1") (pinfunction "1_1") (pintype "passive"))
      (node (ref "CIN2") (pin "1") (pinfunction "1_1") (pintype "passive"))
      (node (ref "CIN3") (pin "1") (pinfunction "1_1") (pintype "passive"))
      (node (ref "CIN4") (pin "1") (pinfunction "1_1") (pintype "passive"))
      (node (ref "R12") (pin "2") (pinfunction "2_2") (pintype "passive"))
      (node (ref "R15") (pin "2") (pinfunction "2_2") (pintype "passive"))
      (node (ref "R19") (pin "2") (pinfunction "2_2") (pintype "passive"))
      (node (ref "R28") (pin "2") (pinfunction "2_2") (pintype "passive"))
      (node (ref "SHORE_IN") (pin "P$1") (pinfunction "P$1_P$1") (pintype "bidirectional"))
      (node (ref "U$25") (pin "P$4") (pinfunction "VI_P$4") (pintype "bidirectional"))
      (node (ref "U$41") (pin "P$4") (pinfunction "VI_P$4") (pintype "bidirectional"))
      (node (ref "U$48") (pin "OUT") (pinfunction "OUT_OUT") (pintype "bidirectional"))
      (node (ref "U$51") (pin "OUT") (pinfunction "OUT_OUT") (pintype "bidirectional"))
      (node (ref "U$66") (pin "P$2") (pinfunction "C_P$2") (pintype "passive"))
      (node (ref "U$7") (pin "2A") (pinfunction "2_2A") (pintype "bidirectional"))
      (node (ref "U$7") (pin "2B") (pinfunction "2_2B") (pintype "bidirectional"))
      (node (ref "U$73") (pin "P$1") (pinfunction "1_P$1") (pintype "bidirectional"))
    )
    (net (code "111") (name "V_RELAY") (class "Default")
      (node (ref "U$19") (pin "P$1") (pinfunction "IP+_P$1") (pintype "bidirectional"))
      (node (ref "U$19") (pin "P$2") (pinfunction "IP+_P$2") (pintype "bidirectional"))
      (node (ref "U$7") (pin "7A") (pinfunction "7_7A") (pintype "bidirectional"))
      (node (ref "U$7") (pin "7B") (pinfunction "7_7B") (pintype "bidirectional"))
    )
    (net (code "112") (name "V_THRUST") (class "Default")
      (node (ref "C17") (pin "1") (pinfunction "1_1") (pintype "passive"))
      (node (ref "C21") (pin "1") (pinfunction "1_1") (pintype "passive"))
      (node (ref "C22") (pin "1") (pinfunction "1_1") (pintype "passive"))
      (node (ref "C43") (pin "+") (pinfunction "+_+") (pintype "passive"))
      (node (ref "C44") (pin "+") (pinfunction "+_+") (pintype "passive"))
      (node (ref "C46") (pin "1") (pinfunction "1_1") (pintype "passive"))
      (node (ref "C47") (pin "1") (pinfunction "1_1") (pintype "passive"))
      (node (ref "CAMERA1") (pin "P$1") (pinfunction "P$1_P$1") (pintype "bidirectional"))
      (node (ref "CAMERA2") (pin "P$1") (pinfunction "P$1_P$1") (pintype "bidirectional"))
      (node (ref "R30") (pin "1") (pinfunction "1_1") (pintype "passive"))
      (node (ref "R32") (pin "2") (pinfunction "2_2") (pintype "passive"))
      (node (ref "U$11") (pin "P$1") (pinfunction "IP+_P$1") (pintype "bidirectional"))
      (node (ref "U$11") (pin "P$2") (pinfunction "IP+_P$2") (pintype "bidirectional"))
      (node (ref "U$14") (pin "P$1") (pinfunction "IP+_P$1") (pintype "bidirectional"))
      (node (ref "U$14") (pin "P$2") (pinfunction "IP+_P$2") (pintype "bidirectional"))
      (node (ref "U$17") (pin "P$1") (pinfunction "IP+_P$1") (pintype "bidirectional"))
      (node (ref "U$17") (pin "P$2") (pinfunction "IP+_P$2") (pintype "bidirectional"))
      (node (ref "U$23") (pin "P$1") (pinfunction "IP+_P$1") (pintype "bidirectional"))
      (node (ref "U$23") (pin "P$2") (pinfunction "IP+_P$2") (pintype "bidirectional"))
      (node (ref "U$29") (pin "P$1") (pinfunction "IP+_P$1") (pintype "bidirectional"))
      (node (ref "U$29") (pin "P$2") (pinfunction "IP+_P$2") (pintype "bidirectional"))
      (node (ref "U$32") (pin "1") (pinfunction "C_1") (pintype "passive"))
      (node (ref "U$32") (pin "2") (pinfunction "C_2") (pintype "passive"))
      (node (ref "U$33") (pin "1") (pinfunction "C_1") (pintype "passive"))
      (node (ref "U$33") (pin "2") (pinfunction "C_2") (pintype "passive"))
      (node (ref "U$34") (pin "1") (pinfunction "C_1") (pintype "passive"))
      (node (ref "U$34") (pin "2") (pinfunction "C_2") (pintype "passive"))
      (node (ref "U$38") (pin "1") (pinfunction "C_1") (pintype "passive"))
      (node (ref "U$38") (pin "2") (pinfunction "C_2") (pintype "passive"))
      (node (ref "U$39") (pin "P$1") (pinfunction "IP+_P$1") (pintype "bidirectional"))
      (node (ref "U$39") (pin "P$2") (pinfunction "IP+_P$2") (pintype "bidirectional"))
      (node (ref "U$4") (pin "P$1") (pinfunction "IP+_P$1") (pintype "bidirectional"))
      (node (ref "U$4") (pin "P$2") (pinfunction "IP+_P$2") (pintype "bidirectional"))
      (node (ref "U$5") (pin "P$3") (pinfunction "P$2_P$3") (pintype "bidirectional"))
      (node (ref "U$5") (pin "P$4") (pinfunction "P$2_P$4") (pintype "bidirectional"))
      (node (ref "U$54") (pin "P$1") (pinfunction "1_P$1") (pintype "bidirectional"))
      (node (ref "U$76") (pin "P$1") (pinfunction "1_P$1") (pintype "bidirectional"))
      (node (ref "U$8") (pin "P$1") (pinfunction "IP+_P$1") (pintype "bidirectional"))
      (node (ref "U$8") (pin "P$2") (pinfunction "IP+_P$2") (pintype "bidirectional"))
      (node (ref "V-THRUST_OUT") (pin "P$1") (pinfunction "P$1_P$1") (pintype "bidirectional"))
    )
    (net (code "113") (name "V_THRUST2") (class "Default")
      (node (ref "C10") (pin "1") (pinfunction "1_1") (pintype "passive"))
      (node (ref "C74") (pin "1") (pinfunction "1_1") (pintype "passive"))
      (node (ref "C75") (pin "1") (pinfunction "1_1") (pintype "passive"))
      (node (ref "C76") (pin "1") (pinfunction "1_1") (pintype "passive"))
      (node (ref "THRUST2") (pin "P$4") (pinfunction "P$4_P$4") (pintype "bidirectional"))
      (node (ref "U$30") (pin "1") (pinfunction "C_1") (pintype "passive"))
      (node (ref "U$30") (pin "2") (pinfunction "C_2") (pintype "passive"))
      (node (ref "U$9") (pin "P$2") (pinfunction "P$2_P$2") (pintype "bidirectional"))
    )
    (net (code "114") (name "V_THRUST3") (class "Default")
      (node (ref "C107") (pin "1") (pinfunction "1_1") (pintype "passive"))
      (node (ref "C108") (pin "1") (pinfunction "1_1") (pintype "passive"))
      (node (ref "THRUST3") (pin "P$4") (pinfunction "P$4_P$4") (pintype "bidirectional"))
      (node (ref "U$12") (pin "P$2") (pinfunction "P$2_P$2") (pintype "bidirectional"))
      (node (ref "U$26") (pin "1") (pinfunction "C_1") (pintype "passive"))
      (node (ref "U$26") (pin "2") (pinfunction "C_2") (pintype "passive"))
    )
    (net (code "115") (name "V_THRUST4") (class "Default")
      (node (ref "C80") (pin "1") (pinfunction "1_1") (pintype "passive"))
      (node (ref "C88") (pin "1") (pinfunction "1_1") (pintype "passive"))
      (node (ref "THRUST4") (pin "P$4") (pinfunction "P$4_P$4") (pintype "bidirectional"))
      (node (ref "U$15") (pin "P$2") (pinfunction "P$2_P$2") (pintype "bidirectional"))
      (node (ref "U$28") (pin "1") (pinfunction "C_1") (pintype "passive"))
      (node (ref "U$28") (pin "2") (pinfunction "C_2") (pintype "passive"))
    )
    (net (code "116") (name "V_THRUST5") (class "Default")
      (node (ref "C110") (pin "1") (pinfunction "1_1") (pintype "passive"))
      (node (ref "C111") (pin "1") (pinfunction "1_1") (pintype "passive"))
      (node (ref "THRUST5") (pin "P$4") (pinfunction "P$4_P$4") (pintype "bidirectional"))
      (node (ref "U$18") (pin "P$2") (pinfunction "P$2_P$2") (pintype "bidirectional"))
      (node (ref "U$22") (pin "1") (pinfunction "C_1") (pintype "passive"))
      (node (ref "U$22") (pin "2") (pinfunction "C_2") (pintype "passive"))
    )
    (net (code "117") (name "V_THRUST6") (class "Default")
      (node (ref "C101") (pin "1") (pinfunction "1_1") (pintype "passive"))
      (node (ref "C102") (pin "1") (pinfunction "1_1") (pintype "passive"))
      (node (ref "THRUST6") (pin "P$4") (pinfunction "P$4_P$4") (pintype "bidirectional"))
      (node (ref "U$13") (pin "1") (pinfunction "C_1") (pintype "passive"))
      (node (ref "U$13") (pin "2") (pinfunction "C_2") (pintype "passive"))
      (node (ref "U$27") (pin "P$2") (pinfunction "P$2_P$2") (pintype "bidirectional"))
    )
    (net (code "118") (name "V_THRUST7") (class "Default")
      (node (ref "C113") (pin "1") (pinfunction "1_1") (pintype "passive"))
      (node (ref "C114") (pin "1") (pinfunction "1_1") (pintype "passive"))
      (node (ref "THRUST7") (pin "P$4") (pinfunction "P$4_P$4") (pintype "bidirectional"))
      (node (ref "U$16") (pin "1") (pinfunction "C_1") (pintype "passive"))
      (node (ref "U$16") (pin "2") (pinfunction "C_2") (pintype "passive"))
      (node (ref "U$37") (pin "P$2") (pinfunction "P$2_P$2") (pintype "bidirectional"))
    )
    (net (code "119") (name "V_THRUST8") (class "Default")
      (node (ref "C104") (pin "1") (pinfunction "1_1") (pintype "passive"))
      (node (ref "C105") (pin "1") (pinfunction "1_1") (pintype "passive"))
      (node (ref "THRUST8") (pin "P$4") (pinfunction "P$4_P$4") (pintype "bidirectional"))
      (node (ref "U$10") (pin "1") (pinfunction "C_1") (pintype "passive"))
      (node (ref "U$10") (pin "2") (pinfunction "C_2") (pintype "passive"))
      (node (ref "U$40") (pin "P$2") (pinfunction "P$2_P$2") (pintype "bidirectional"))
    )
    (net (code "120") (name "unconnected-(5V_CURR_ADC-ALERT-PadP$2)") (class "Default")
      (node (ref "5V_CURR_ADC") (pin "P$2") (pinfunction "ALERT_P$2") (pintype "bidirectional"))
    )
    (net (code "121") (name "unconnected-(12V_CURR_ADC-ALERT-PadP$2)") (class "Default")
      (node (ref "12V_CURR_ADC") (pin "P$2") (pinfunction "ALERT_P$2") (pintype "bidirectional"))
    )
    (net (code "122") (name "unconnected-(U$24-DEN-Pad3)") (class "Default")
      (node (ref "U$24") (pin "3") (pinfunction "DEN_3") (pintype "bidirectional"))
    )
    (net (code "123") (name "unconnected-(U$24-IS-Pad4)") (class "Default")
      (node (ref "U$24") (pin "4") (pinfunction "IS_4") (pintype "bidirectional"))
    )
    (net (code "124") (name "unconnected-(U1-CH8-Pad15)") (class "Default")
      (node (ref "U1") (pin "15") (pinfunction "CH8_15") (pintype "bidirectional"))
    )
    (net (code "125") (name "unconnected-(U1-CH9-Pad16)") (class "Default")
      (node (ref "U1") (pin "16") (pinfunction "CH9_16") (pintype "bidirectional"))
    )
    (net (code "126") (name "unconnected-(U1-CH10-Pad17)") (class "Default")
      (node (ref "U1") (pin "17") (pinfunction "CH10_17") (pintype "bidirectional"))
    )
    (net (code "127") (name "unconnected-(U1-CH11-Pad18)") (class "Default")
      (node (ref "U1") (pin "18") (pinfunction "CH11_18") (pintype "bidirectional"))
    )
    (net (code "128") (name "unconnected-(U1-CH12-Pad19)") (class "Default")
      (node (ref "U1") (pin "19") (pinfunction "CH12_19") (pintype "bidirectional"))
    )
    (net (code "129") (name "unconnected-(U1-CH13-Pad20)") (class "Default")
      (node (ref "U1") (pin "20") (pinfunction "CH13_20") (pintype "bidirectional"))
    )
    (net (code "130") (name "unconnected-(U1-CH14-Pad21)") (class "Default")
      (node (ref "U1") (pin "21") (pinfunction "CH14_21") (pintype "bidirectional"))
    )
    (net (code "131") (name "unconnected-(U1-CH15-Pad22)") (class "Default")
      (node (ref "U1") (pin "22") (pinfunction "CH15_22") (pintype "bidirectional"))
    )
    (net (code "132") (name "unconnected-(V-THRUST_CURR_ADC-ALERT-PadP$2)") (class "Default")
      (node (ref "V-THRUST_CURR_ADC") (pin "P$2") (pinfunction "ALERT_P$2") (pintype "bidirectional"))
    )
  )
)
